# module_RevD_panelized.net
KiCad netlist of a schematic drawn in EAGLE
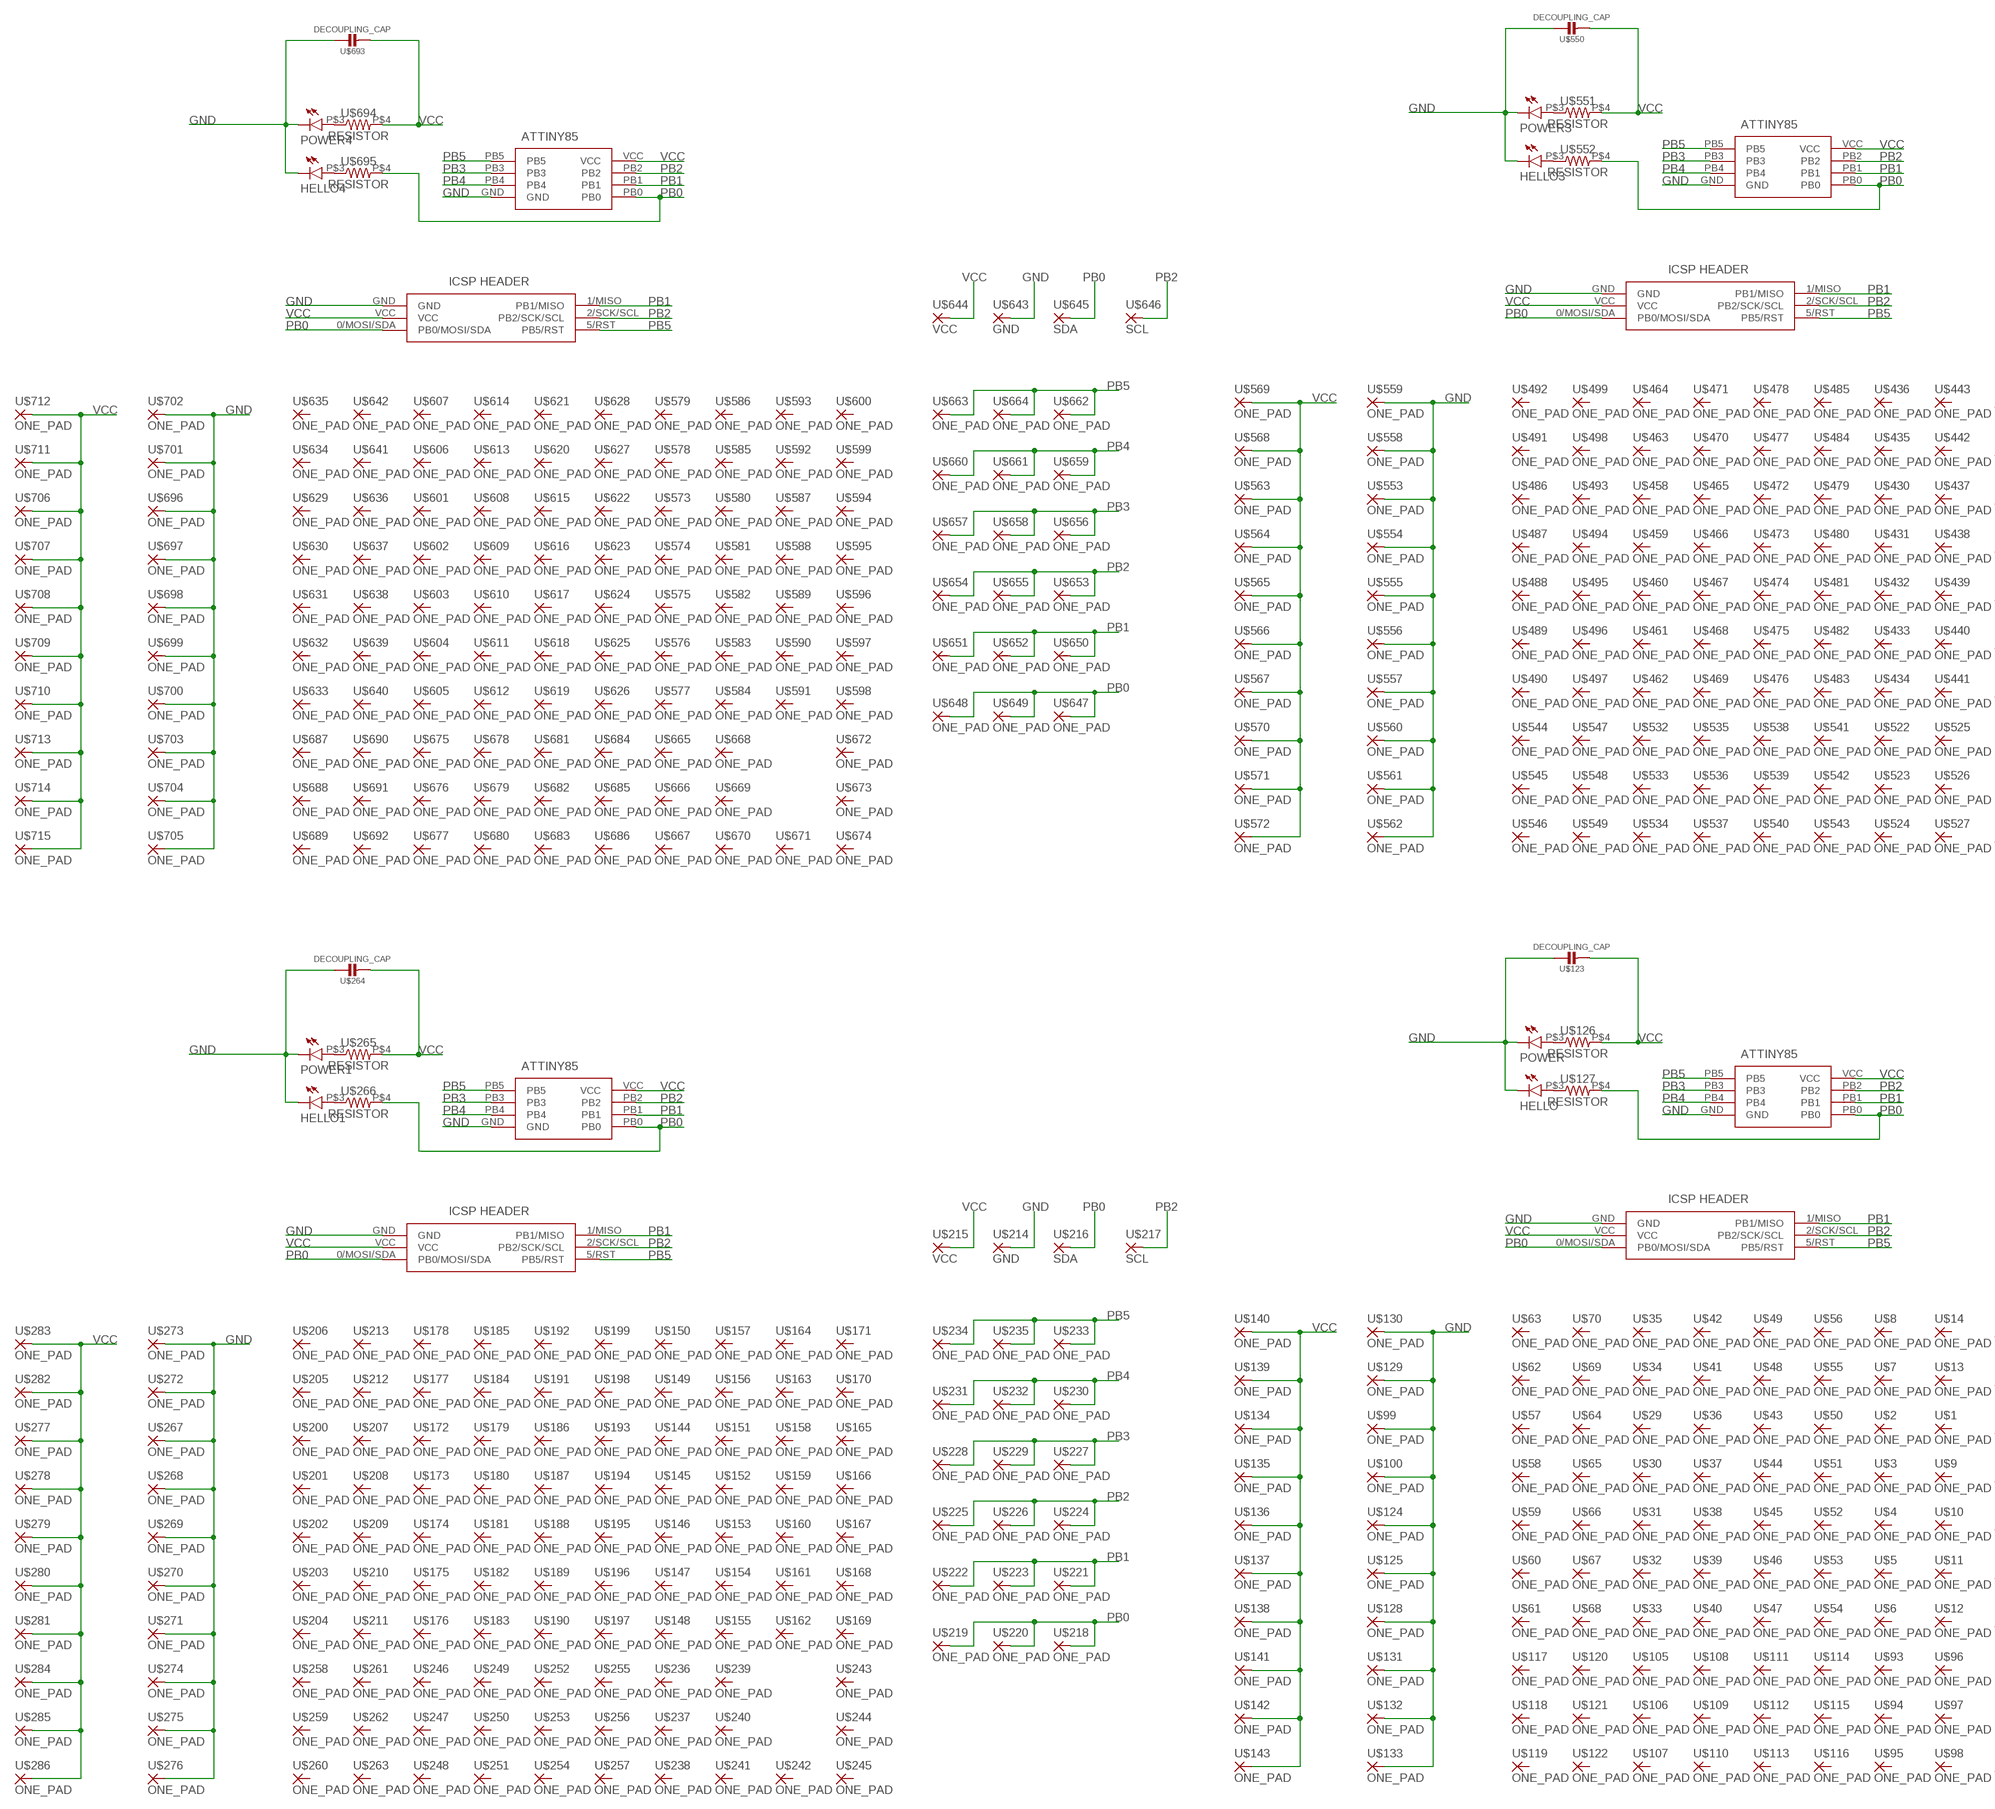
[diagram p0: schematic, sheet 1, part 1 of 2]
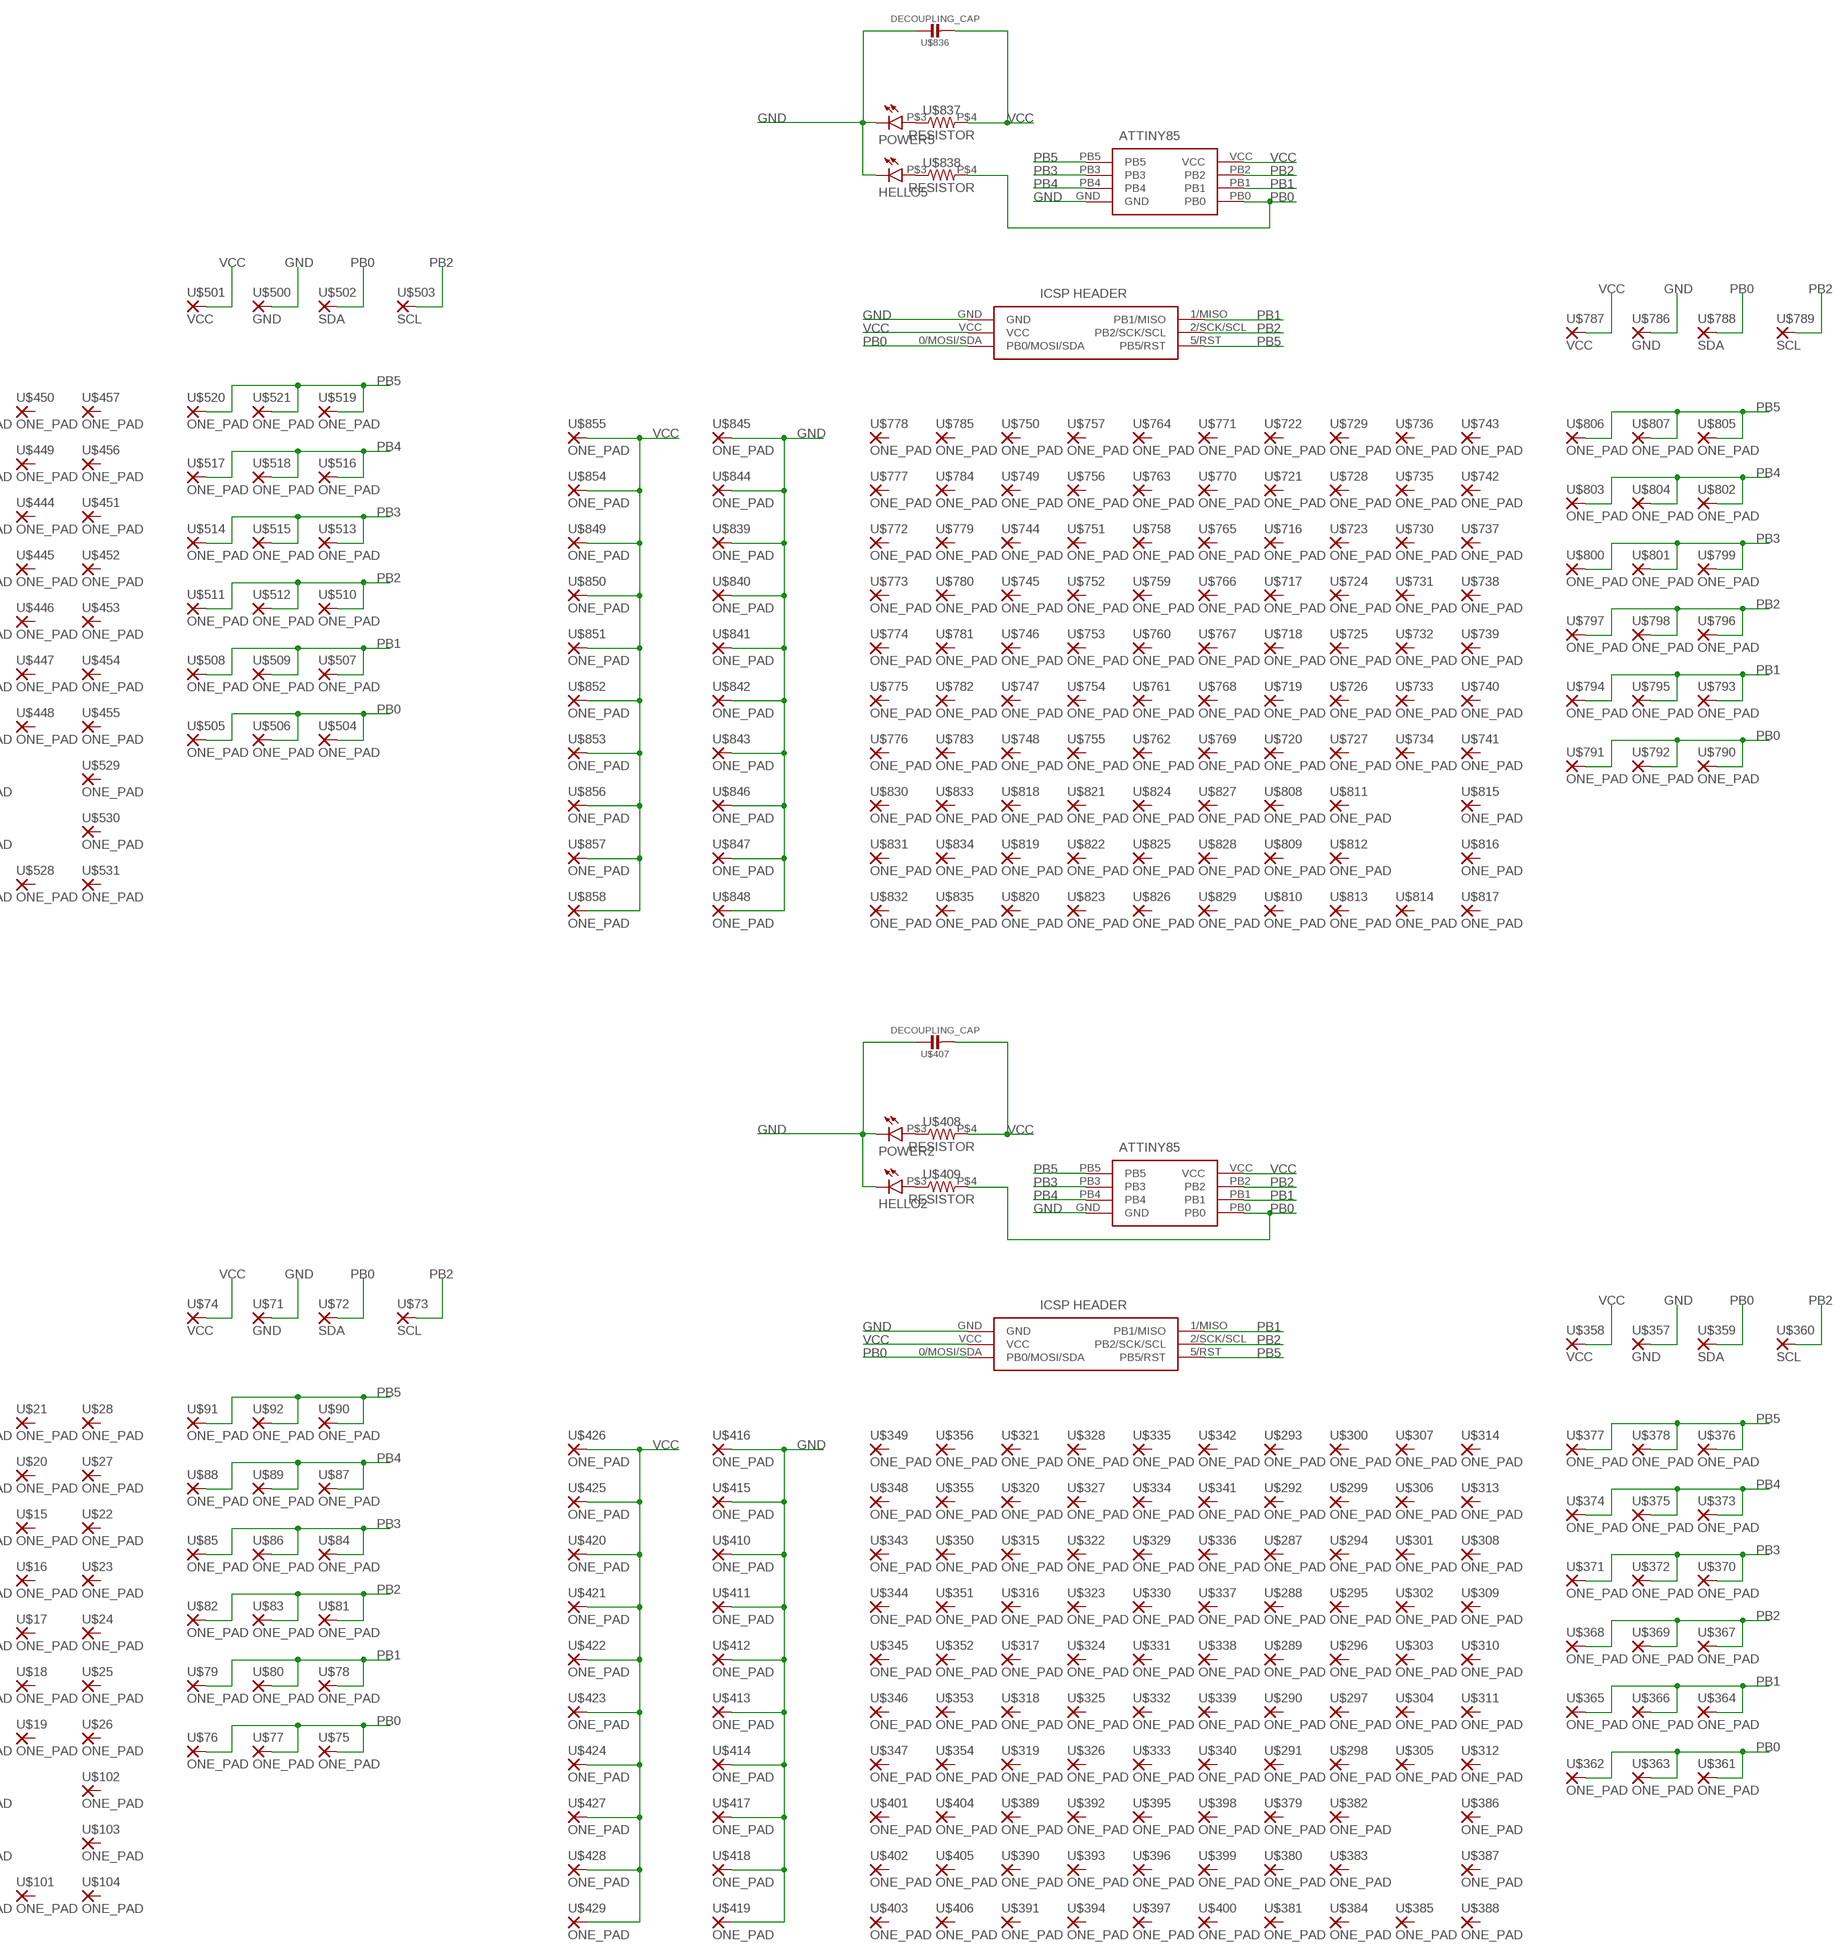
[diagram p1: schematic, sheet 1, part 2 of 2]

(export (version "E")
  (design (tool "Eeschema 10.0.6"))
  (components
    (comp (ref "HELLO")
      (value "LED3MM")
      (footprint "eagle-import:LED3MM")
      (libsource (lib "eagle-import") (part "LED3MM"))
    )
    (comp (ref "HELLO1")
      (value "LED3MM")
      (footprint "eagle-import:LED3MM")
      (libsource (lib "eagle-import") (part "LED3MM"))
    )
    (comp (ref "HELLO2")
      (value "LED3MM")
      (footprint "eagle-import:LED3MM")
      (libsource (lib "eagle-import") (part "LED3MM"))
    )
    (comp (ref "HELLO3")
      (value "LED3MM")
      (footprint "eagle-import:LED3MM")
      (libsource (lib "eagle-import") (part "LED3MM"))
    )
    (comp (ref "HELLO4")
      (value "LED3MM")
      (footprint "eagle-import:LED3MM")
      (libsource (lib "eagle-import") (part "LED3MM"))
    )
    (comp (ref "HELLO5")
      (value "LED3MM")
      (footprint "eagle-import:LED3MM")
      (libsource (lib "eagle-import") (part "LED3MM"))
    )
    (comp (ref "IC1")
      (value "ATTINY85-20SU")
      (footprint "eagle-import:SOT127P798X216-8N")
      (fields (field (name "RS_PART_NUMBER") "1331674"))
      (libsource (lib "eagle-import") (part "ATTINY85-20SU"))
    )
    (comp (ref "IC2")
      (value "ATTINY85-20SU")
      (footprint "eagle-import:SOT127P798X216-8N")
      (fields (field (name "RS_PART_NUMBER") "1331674"))
      (libsource (lib "eagle-import") (part "ATTINY85-20SU"))
    )
    (comp (ref "IC3")
      (value "ATTINY85-20SU")
      (footprint "eagle-import:SOT127P798X216-8N")
      (fields (field (name "RS_PART_NUMBER") "1331674"))
      (libsource (lib "eagle-import") (part "ATTINY85-20SU"))
    )
    (comp (ref "IC4")
      (value "ATTINY85-20SU")
      (footprint "eagle-import:SOT127P798X216-8N")
      (fields (field (name "RS_PART_NUMBER") "1331674"))
      (libsource (lib "eagle-import") (part "ATTINY85-20SU"))
    )
    (comp (ref "IC5")
      (value "ATTINY85-20SU")
      (footprint "eagle-import:SOT127P798X216-8N")
      (fields (field (name "RS_PART_NUMBER") "1331674"))
      (libsource (lib "eagle-import") (part "ATTINY85-20SU"))
    )
    (comp (ref "IC6")
      (value "ATTINY85-20SU")
      (footprint "eagle-import:SOT127P798X216-8N")
      (fields (field (name "RS_PART_NUMBER") "1331674"))
      (libsource (lib "eagle-import") (part "ATTINY85-20SU"))
    )
    (comp (ref "J1")
      (value "M20-9980346")
      (footprint "eagle-import:HDRV6W64P254_2X3_762X508X868P")
      (fields (field (name "RS_PART_NUMBER") "7457046P"))
      (libsource (lib "eagle-import") (part "M20-9980346"))
    )
    (comp (ref "J2")
      (value "M20-9980346")
      (footprint "eagle-import:HDRV6W64P254_2X3_762X508X868P")
      (fields (field (name "RS_PART_NUMBER") "7457046P"))
      (libsource (lib "eagle-import") (part "M20-9980346"))
    )
    (comp (ref "J3")
      (value "M20-9980346")
      (footprint "eagle-import:HDRV6W64P254_2X3_762X508X868P")
      (fields (field (name "RS_PART_NUMBER") "7457046P"))
      (libsource (lib "eagle-import") (part "M20-9980346"))
    )
    (comp (ref "J4")
      (value "M20-9980346")
      (footprint "eagle-import:HDRV6W64P254_2X3_762X508X868P")
      (fields (field (name "RS_PART_NUMBER") "7457046P"))
      (libsource (lib "eagle-import") (part "M20-9980346"))
    )
    (comp (ref "J5")
      (value "M20-9980346")
      (footprint "eagle-import:HDRV6W64P254_2X3_762X508X868P")
      (fields (field (name "RS_PART_NUMBER") "7457046P"))
      (libsource (lib "eagle-import") (part "M20-9980346"))
    )
    (comp (ref "J6")
      (value "M20-9980346")
      (footprint "eagle-import:HDRV6W64P254_2X3_762X508X868P")
      (fields (field (name "RS_PART_NUMBER") "7457046P"))
      (libsource (lib "eagle-import") (part "M20-9980346"))
    )
    (comp (ref "POWER")
      (value "LED3MM")
      (footprint "eagle-import:LED3MM")
      (libsource (lib "eagle-import") (part "LED3MM"))
    )
    (comp (ref "POWER1")
      (value "LED3MM")
      (footprint "eagle-import:LED3MM")
      (libsource (lib "eagle-import") (part "LED3MM"))
    )
    (comp (ref "POWER2")
      (value "LED3MM")
      (footprint "eagle-import:LED3MM")
      (libsource (lib "eagle-import") (part "LED3MM"))
    )
    (comp (ref "POWER3")
      (value "LED3MM")
      (footprint "eagle-import:LED3MM")
      (libsource (lib "eagle-import") (part "LED3MM"))
    )
    (comp (ref "POWER4")
      (value "LED3MM")
      (footprint "eagle-import:LED3MM")
      (libsource (lib "eagle-import") (part "LED3MM"))
    )
    (comp (ref "POWER5")
      (value "LED3MM")
      (footprint "eagle-import:LED3MM")
      (libsource (lib "eagle-import") (part "LED3MM"))
    )
    (comp (ref "U$1")
      (value "ONE_PAD")
      (footprint "eagle-import:1X01")
      (libsource (lib "eagle-import") (part "ONE_PAD"))
    )
    (comp (ref "U$2")
      (value "ONE_PAD")
      (footprint "eagle-import:1X01")
      (libsource (lib "eagle-import") (part "ONE_PAD"))
    )
    (comp (ref "U$3")
      (value "ONE_PAD")
      (footprint "eagle-import:1X01")
      (libsource (lib "eagle-import") (part "ONE_PAD"))
    )
    (comp (ref "U$4")
      (value "ONE_PAD")
      (footprint "eagle-import:1X01")
      (libsource (lib "eagle-import") (part "ONE_PAD"))
    )
    (comp (ref "U$5")
      (value "ONE_PAD")
      (footprint "eagle-import:1X01")
      (libsource (lib "eagle-import") (part "ONE_PAD"))
    )
    (comp (ref "U$6")
      (value "ONE_PAD")
      (footprint "eagle-import:1X01")
      (libsource (lib "eagle-import") (part "ONE_PAD"))
    )
    (comp (ref "U$7")
      (value "ONE_PAD")
      (footprint "eagle-import:1X01")
      (libsource (lib "eagle-import") (part "ONE_PAD"))
    )
    (comp (ref "U$8")
      (value "ONE_PAD")
      (footprint "eagle-import:1X01")
      (libsource (lib "eagle-import") (part "ONE_PAD"))
    )
    (comp (ref "U$9")
      (value "ONE_PAD")
      (footprint "eagle-import:1X01")
      (libsource (lib "eagle-import") (part "ONE_PAD"))
    )
    (comp (ref "U$10")
      (value "ONE_PAD")
      (footprint "eagle-import:1X01")
      (libsource (lib "eagle-import") (part "ONE_PAD"))
    )
    (comp (ref "U$11")
      (value "ONE_PAD")
      (footprint "eagle-import:1X01")
      (libsource (lib "eagle-import") (part "ONE_PAD"))
    )
    (comp (ref "U$12")
      (value "ONE_PAD")
      (footprint "eagle-import:1X01")
      (libsource (lib "eagle-import") (part "ONE_PAD"))
    )
    (comp (ref "U$13")
      (value "ONE_PAD")
      (footprint "eagle-import:1X01")
      (libsource (lib "eagle-import") (part "ONE_PAD"))
    )
    (comp (ref "U$14")
      (value "ONE_PAD")
      (footprint "eagle-import:1X01")
      (libsource (lib "eagle-import") (part "ONE_PAD"))
    )
    (comp (ref "U$15")
      (value "ONE_PAD")
      (footprint "eagle-import:1X01")
      (libsource (lib "eagle-import") (part "ONE_PAD"))
    )
    (comp (ref "U$16")
      (value "ONE_PAD")
      (footprint "eagle-import:1X01")
      (libsource (lib "eagle-import") (part "ONE_PAD"))
    )
    (comp (ref "U$17")
      (value "ONE_PAD")
      (footprint "eagle-import:1X01")
      (libsource (lib "eagle-import") (part "ONE_PAD"))
    )
    (comp (ref "U$18")
      (value "ONE_PAD")
      (footprint "eagle-import:1X01")
      (libsource (lib "eagle-import") (part "ONE_PAD"))
    )
    (comp (ref "U$19")
      (value "ONE_PAD")
      (footprint "eagle-import:1X01")
      (libsource (lib "eagle-import") (part "ONE_PAD"))
    )
    (comp (ref "U$20")
      (value "ONE_PAD")
      (footprint "eagle-import:1X01")
      (libsource (lib "eagle-import") (part "ONE_PAD"))
    )
    (comp (ref "U$21")
      (value "ONE_PAD")
      (footprint "eagle-import:1X01")
      (libsource (lib "eagle-import") (part "ONE_PAD"))
    )
    (comp (ref "U$22")
      (value "ONE_PAD")
      (footprint "eagle-import:1X01")
      (libsource (lib "eagle-import") (part "ONE_PAD"))
    )
    (comp (ref "U$23")
      (value "ONE_PAD")
      (footprint "eagle-import:1X01")
      (libsource (lib "eagle-import") (part "ONE_PAD"))
    )
    (comp (ref "U$24")
      (value "ONE_PAD")
      (footprint "eagle-import:1X01")
      (libsource (lib "eagle-import") (part "ONE_PAD"))
    )
    (comp (ref "U$25")
      (value "ONE_PAD")
      (footprint "eagle-import:1X01")
      (libsource (lib "eagle-import") (part "ONE_PAD"))
    )
    (comp (ref "U$26")
      (value "ONE_PAD")
      (footprint "eagle-import:1X01")
      (libsource (lib "eagle-import") (part "ONE_PAD"))
    )
    (comp (ref "U$27")
      (value "ONE_PAD")
      (footprint "eagle-import:1X01")
      (libsource (lib "eagle-import") (part "ONE_PAD"))
    )
    (comp (ref "U$28")
      (value "ONE_PAD")
      (footprint "eagle-import:1X01")
      (libsource (lib "eagle-import") (part "ONE_PAD"))
    )
    (comp (ref "U$29")
      (value "ONE_PAD")
      (footprint "eagle-import:1X01")
      (libsource (lib "eagle-import") (part "ONE_PAD"))
    )
    (comp (ref "U$30")
      (value "ONE_PAD")
      (footprint "eagle-import:1X01")
      (libsource (lib "eagle-import") (part "ONE_PAD"))
    )
    (comp (ref "U$31")
      (value "ONE_PAD")
      (footprint "eagle-import:1X01")
      (libsource (lib "eagle-import") (part "ONE_PAD"))
    )
    (comp (ref "U$32")
      (value "ONE_PAD")
      (footprint "eagle-import:1X01")
      (libsource (lib "eagle-import") (part "ONE_PAD"))
    )
    (comp (ref "U$33")
      (value "ONE_PAD")
      (footprint "eagle-import:1X01")
      (libsource (lib "eagle-import") (part "ONE_PAD"))
    )
    (comp (ref "U$34")
      (value "ONE_PAD")
      (footprint "eagle-import:1X01")
      (libsource (lib "eagle-import") (part "ONE_PAD"))
    )
    (comp (ref "U$35")
      (value "ONE_PAD")
      (footprint "eagle-import:1X01")
      (libsource (lib "eagle-import") (part "ONE_PAD"))
    )
    (comp (ref "U$36")
      (value "ONE_PAD")
      (footprint "eagle-import:1X01")
      (libsource (lib "eagle-import") (part "ONE_PAD"))
    )
    (comp (ref "U$37")
      (value "ONE_PAD")
      (footprint "eagle-import:1X01")
      (libsource (lib "eagle-import") (part "ONE_PAD"))
    )
    (comp (ref "U$38")
      (value "ONE_PAD")
      (footprint "eagle-import:1X01")
      (libsource (lib "eagle-import") (part "ONE_PAD"))
    )
    (comp (ref "U$39")
      (value "ONE_PAD")
      (footprint "eagle-import:1X01")
      (libsource (lib "eagle-import") (part "ONE_PAD"))
    )
    (comp (ref "U$40")
      (value "ONE_PAD")
      (footprint "eagle-import:1X01")
      (libsource (lib "eagle-import") (part "ONE_PAD"))
    )
    (comp (ref "U$41")
      (value "ONE_PAD")
      (footprint "eagle-import:1X01")
      (libsource (lib "eagle-import") (part "ONE_PAD"))
    )
    (comp (ref "U$42")
      (value "ONE_PAD")
      (footprint "eagle-import:1X01")
      (libsource (lib "eagle-import") (part "ONE_PAD"))
    )
    (comp (ref "U$43")
      (value "ONE_PAD")
      (footprint "eagle-import:1X01")
      (libsource (lib "eagle-import") (part "ONE_PAD"))
    )
    (comp (ref "U$44")
      (value "ONE_PAD")
      (footprint "eagle-import:1X01")
      (libsource (lib "eagle-import") (part "ONE_PAD"))
    )
    (comp (ref "U$45")
      (value "ONE_PAD")
      (footprint "eagle-import:1X01")
      (libsource (lib "eagle-import") (part "ONE_PAD"))
    )
    (comp (ref "U$46")
      (value "ONE_PAD")
      (footprint "eagle-import:1X01")
      (libsource (lib "eagle-import") (part "ONE_PAD"))
    )
    (comp (ref "U$47")
      (value "ONE_PAD")
      (footprint "eagle-import:1X01")
      (libsource (lib "eagle-import") (part "ONE_PAD"))
    )
    (comp (ref "U$48")
      (value "ONE_PAD")
      (footprint "eagle-import:1X01")
      (libsource (lib "eagle-import") (part "ONE_PAD"))
    )
    (comp (ref "U$49")
      (value "ONE_PAD")
      (footprint "eagle-import:1X01")
      (libsource (lib "eagle-import") (part "ONE_PAD"))
    )
    (comp (ref "U$50")
      (value "ONE_PAD")
      (footprint "eagle-import:1X01")
      (libsource (lib "eagle-import") (part "ONE_PAD"))
    )
    (comp (ref "U$51")
      (value "ONE_PAD")
      (footprint "eagle-import:1X01")
      (libsource (lib "eagle-import") (part "ONE_PAD"))
    )
    (comp (ref "U$52")
      (value "ONE_PAD")
      (footprint "eagle-import:1X01")
      (libsource (lib "eagle-import") (part "ONE_PAD"))
    )
    (comp (ref "U$53")
      (value "ONE_PAD")
      (footprint "eagle-import:1X01")
      (libsource (lib "eagle-import") (part "ONE_PAD"))
    )
    (comp (ref "U$54")
      (value "ONE_PAD")
      (footprint "eagle-import:1X01")
      (libsource (lib "eagle-import") (part "ONE_PAD"))
    )
    (comp (ref "U$55")
      (value "ONE_PAD")
      (footprint "eagle-import:1X01")
      (libsource (lib "eagle-import") (part "ONE_PAD"))
    )
    (comp (ref "U$56")
      (value "ONE_PAD")
      (footprint "eagle-import:1X01")
      (libsource (lib "eagle-import") (part "ONE_PAD"))
    )
    (comp (ref "U$57")
      (value "ONE_PAD")
      (footprint "eagle-import:1X01")
      (libsource (lib "eagle-import") (part "ONE_PAD"))
    )
    (comp (ref "U$58")
      (value "ONE_PAD")
      (footprint "eagle-import:1X01")
      (libsource (lib "eagle-import") (part "ONE_PAD"))
    )
    (comp (ref "U$59")
      (value "ONE_PAD")
      (footprint "eagle-import:1X01")
      (libsource (lib "eagle-import") (part "ONE_PAD"))
    )
    (comp (ref "U$60")
      (value "ONE_PAD")
      (footprint "eagle-import:1X01")
      (libsource (lib "eagle-import") (part "ONE_PAD"))
    )
    (comp (ref "U$61")
      (value "ONE_PAD")
      (footprint "eagle-import:1X01")
      (libsource (lib "eagle-import") (part "ONE_PAD"))
    )
    (comp (ref "U$62")
      (value "ONE_PAD")
      (footprint "eagle-import:1X01")
      (libsource (lib "eagle-import") (part "ONE_PAD"))
    )
    (comp (ref "U$63")
      (value "ONE_PAD")
      (footprint "eagle-import:1X01")
      (libsource (lib "eagle-import") (part "ONE_PAD"))
    )
    (comp (ref "U$64")
      (value "ONE_PAD")
      (footprint "eagle-import:1X01")
      (libsource (lib "eagle-import") (part "ONE_PAD"))
    )
    (comp (ref "U$65")
      (value "ONE_PAD")
      (footprint "eagle-import:1X01")
      (libsource (lib "eagle-import") (part "ONE_PAD"))
    )
    (comp (ref "U$66")
      (value "ONE_PAD")
      (footprint "eagle-import:1X01")
      (libsource (lib "eagle-import") (part "ONE_PAD"))
    )
    (comp (ref "U$67")
      (value "ONE_PAD")
      (footprint "eagle-import:1X01")
      (libsource (lib "eagle-import") (part "ONE_PAD"))
    )
    (comp (ref "U$68")
      (value "ONE_PAD")
      (footprint "eagle-import:1X01")
      (libsource (lib "eagle-import") (part "ONE_PAD"))
    )
    (comp (ref "U$69")
      (value "ONE_PAD")
      (footprint "eagle-import:1X01")
      (libsource (lib "eagle-import") (part "ONE_PAD"))
    )
    (comp (ref "U$70")
      (value "ONE_PAD")
      (footprint "eagle-import:1X01")
      (libsource (lib "eagle-import") (part "ONE_PAD"))
    )
    (comp (ref "U$71")
      (value "GND")
      (footprint "eagle-import:1X01")
      (libsource (lib "eagle-import") (part "ONE_PAD"))
    )
    (comp (ref "U$72")
      (value "SDA")
      (footprint "eagle-import:1X01")
      (libsource (lib "eagle-import") (part "ONE_PAD"))
    )
    (comp (ref "U$73")
      (value "SCL")
      (footprint "eagle-import:1X01")
      (libsource (lib "eagle-import") (part "ONE_PAD"))
    )
    (comp (ref "U$74")
      (value "VCC")
      (footprint "eagle-import:1X01")
      (libsource (lib "eagle-import") (part "ONE_PAD"))
    )
    (comp (ref "U$75")
      (value "ONE_PAD")
      (footprint "eagle-import:1X01")
      (libsource (lib "eagle-import") (part "ONE_PAD"))
    )
    (comp (ref "U$76")
      (value "ONE_PAD")
      (footprint "eagle-import:1X01")
      (libsource (lib "eagle-import") (part "ONE_PAD"))
    )
    (comp (ref "U$77")
      (value "ONE_PAD")
      (footprint "eagle-import:1X01")
      (libsource (lib "eagle-import") (part "ONE_PAD"))
    )
    (comp (ref "U$78")
      (value "ONE_PAD")
      (footprint "eagle-import:1X01")
      (libsource (lib "eagle-import") (part "ONE_PAD"))
    )
    (comp (ref "U$79")
      (value "ONE_PAD")
      (footprint "eagle-import:1X01")
      (libsource (lib "eagle-import") (part "ONE_PAD"))
    )
    (comp (ref "U$80")
      (value "ONE_PAD")
      (footprint "eagle-import:1X01")
      (libsource (lib "eagle-import") (part "ONE_PAD"))
    )
    (comp (ref "U$81")
      (value "ONE_PAD")
      (footprint "eagle-import:1X01")
      (libsource (lib "eagle-import") (part "ONE_PAD"))
    )
    (comp (ref "U$82")
      (value "ONE_PAD")
      (footprint "eagle-import:1X01")
      (libsource (lib "eagle-import") (part "ONE_PAD"))
    )
    (comp (ref "U$83")
      (value "ONE_PAD")
      (footprint "eagle-import:1X01")
      (libsource (lib "eagle-import") (part "ONE_PAD"))
    )
    (comp (ref "U$84")
      (value "ONE_PAD")
      (footprint "eagle-import:1X01")
      (libsource (lib "eagle-import") (part "ONE_PAD"))
    )
    (comp (ref "U$85")
      (value "ONE_PAD")
      (footprint "eagle-import:1X01")
      (libsource (lib "eagle-import") (part "ONE_PAD"))
    )
    (comp (ref "U$86")
      (value "ONE_PAD")
      (footprint "eagle-import:1X01")
      (libsource (lib "eagle-import") (part "ONE_PAD"))
    )
    (comp (ref "U$87")
      (value "ONE_PAD")
      (footprint "eagle-import:1X01")
      (libsource (lib "eagle-import") (part "ONE_PAD"))
    )
    (comp (ref "U$88")
      (value "ONE_PAD")
      (footprint "eagle-import:1X01")
      (libsource (lib "eagle-import") (part "ONE_PAD"))
    )
    (comp (ref "U$89")
      (value "ONE_PAD")
      (footprint "eagle-import:1X01")
      (libsource (lib "eagle-import") (part "ONE_PAD"))
    )
    (comp (ref "U$90")
      (value "ONE_PAD")
      (footprint "eagle-import:1X01")
      (libsource (lib "eagle-import") (part "ONE_PAD"))
    )
    (comp (ref "U$91")
      (value "ONE_PAD")
      (footprint "eagle-import:1X01")
      (libsource (lib "eagle-import") (part "ONE_PAD"))
    )
    (comp (ref "U$92")
      (value "ONE_PAD")
      (footprint "eagle-import:1X01")
      (libsource (lib "eagle-import") (part "ONE_PAD"))
    )
    (comp (ref "U$93")
      (value "ONE_PAD")
      (footprint "eagle-import:1X01")
      (libsource (lib "eagle-import") (part "ONE_PAD"))
    )
    (comp (ref "U$94")
      (value "ONE_PAD")
      (footprint "eagle-import:1X01")
      (libsource (lib "eagle-import") (part "ONE_PAD"))
    )
    (comp (ref "U$95")
      (value "ONE_PAD")
      (footprint "eagle-import:1X01")
      (libsource (lib "eagle-import") (part "ONE_PAD"))
    )
    (comp (ref "U$96")
      (value "ONE_PAD")
      (footprint "eagle-import:1X01")
      (libsource (lib "eagle-import") (part "ONE_PAD"))
    )
    (comp (ref "U$97")
      (value "ONE_PAD")
      (footprint "eagle-import:1X01")
      (libsource (lib "eagle-import") (part "ONE_PAD"))
    )
    (comp (ref "U$98")
      (value "ONE_PAD")
      (footprint "eagle-import:1X01")
      (libsource (lib "eagle-import") (part "ONE_PAD"))
    )
    (comp (ref "U$99")
      (value "ONE_PAD")
      (footprint "eagle-import:1X01")
      (libsource (lib "eagle-import") (part "ONE_PAD"))
    )
    (comp (ref "U$100")
      (value "ONE_PAD")
      (footprint "eagle-import:1X01")
      (libsource (lib "eagle-import") (part "ONE_PAD"))
    )
    (comp (ref "U$101")
      (value "ONE_PAD")
      (footprint "eagle-import:1X01")
      (libsource (lib "eagle-import") (part "ONE_PAD"))
    )
    (comp (ref "U$102")
      (value "ONE_PAD")
      (footprint "eagle-import:1X01")
      (libsource (lib "eagle-import") (part "ONE_PAD"))
    )
    (comp (ref "U$103")
      (value "ONE_PAD")
      (footprint "eagle-import:1X01")
      (libsource (lib "eagle-import") (part "ONE_PAD"))
    )
    (comp (ref "U$104")
      (value "ONE_PAD")
      (footprint "eagle-import:1X01")
      (libsource (lib "eagle-import") (part "ONE_PAD"))
    )
    (comp (ref "U$105")
      (value "ONE_PAD")
      (footprint "eagle-import:1X01")
      (libsource (lib "eagle-import") (part "ONE_PAD"))
    )
    (comp (ref "U$106")
      (value "ONE_PAD")
      (footprint "eagle-import:1X01")
      (libsource (lib "eagle-import") (part "ONE_PAD"))
    )
    (comp (ref "U$107")
      (value "ONE_PAD")
      (footprint "eagle-import:1X01")
      (libsource (lib "eagle-import") (part "ONE_PAD"))
    )
    (comp (ref "U$108")
      (value "ONE_PAD")
      (footprint "eagle-import:1X01")
      (libsource (lib "eagle-import") (part "ONE_PAD"))
    )
    (comp (ref "U$109")
      (value "ONE_PAD")
      (footprint "eagle-import:1X01")
      (libsource (lib "eagle-import") (part "ONE_PAD"))
    )
    (comp (ref "U$110")
      (value "ONE_PAD")
      (footprint "eagle-import:1X01")
      (libsource (lib "eagle-import") (part "ONE_PAD"))
    )
    (comp (ref "U$111")
      (value "ONE_PAD")
      (footprint "eagle-import:1X01")
      (libsource (lib "eagle-import") (part "ONE_PAD"))
    )
    (comp (ref "U$112")
      (value "ONE_PAD")
      (footprint "eagle-import:1X01")
      (libsource (lib "eagle-import") (part "ONE_PAD"))
    )
    (comp (ref "U$113")
      (value "ONE_PAD")
      (footprint "eagle-import:1X01")
      (libsource (lib "eagle-import") (part "ONE_PAD"))
    )
    (comp (ref "U$114")
      (value "ONE_PAD")
      (footprint "eagle-import:1X01")
      (libsource (lib "eagle-import") (part "ONE_PAD"))
    )
    (comp (ref "U$115")
      (value "ONE_PAD")
      (footprint "eagle-import:1X01")
      (libsource (lib "eagle-import") (part "ONE_PAD"))
    )
    (comp (ref "U$116")
      (value "ONE_PAD")
      (footprint "eagle-import:1X01")
      (libsource (lib "eagle-import") (part "ONE_PAD"))
    )
    (comp (ref "U$117")
      (value "ONE_PAD")
      (footprint "eagle-import:1X01")
      (libsource (lib "eagle-import") (part "ONE_PAD"))
    )
    (comp (ref "U$118")
      (value "ONE_PAD")
      (footprint "eagle-import:1X01")
      (libsource (lib "eagle-import") (part "ONE_PAD"))
    )
    (comp (ref "U$119")
      (value "ONE_PAD")
      (footprint "eagle-import:1X01")
      (libsource (lib "eagle-import") (part "ONE_PAD"))
    )
    (comp (ref "U$120")
      (value "ONE_PAD")
      (footprint "eagle-import:1X01")
      (libsource (lib "eagle-import") (part "ONE_PAD"))
    )
    (comp (ref "U$121")
      (value "ONE_PAD")
      (footprint "eagle-import:1X01")
      (libsource (lib "eagle-import") (part "ONE_PAD"))
    )
    (comp (ref "U$122")
      (value "ONE_PAD")
      (footprint "eagle-import:1X01")
      (libsource (lib "eagle-import") (part "ONE_PAD"))
    )
    (comp (ref "U$123")
      (value "DECOUPLING_CAP")
      (footprint "eagle-import:DECOUPLING_CAP")
      (libsource (lib "eagle-import") (part "DECOUPLING_CAP"))
    )
    (comp (ref "U$124")
      (value "ONE_PAD")
      (footprint "eagle-import:1X01")
      (libsource (lib "eagle-import") (part "ONE_PAD"))
    )
    (comp (ref "U$125")
      (value "ONE_PAD")
      (footprint "eagle-import:1X01")
      (libsource (lib "eagle-import") (part "ONE_PAD"))
    )
    (comp (ref "U$126")
      (value "RESISTOR")
      (footprint "eagle-import:AXIAL-0.3")
      (libsource (lib "eagle-import") (part "RESISTOR"))
    )
    (comp (ref "U$127")
      (value "RESISTOR")
      (footprint "eagle-import:AXIAL-0.3")
      (libsource (lib "eagle-import") (part "RESISTOR"))
    )
    (comp (ref "U$128")
      (value "ONE_PAD")
      (footprint "eagle-import:1X01")
      (libsource (lib "eagle-import") (part "ONE_PAD"))
    )
    (comp (ref "U$129")
      (value "ONE_PAD")
      (footprint "eagle-import:1X01")
      (libsource (lib "eagle-import") (part "ONE_PAD"))
    )
    (comp (ref "U$130")
      (value "ONE_PAD")
      (footprint "eagle-import:1X01")
      (libsource (lib "eagle-import") (part "ONE_PAD"))
    )
    (comp (ref "U$131")
      (value "ONE_PAD")
      (footprint "eagle-import:1X01")
      (libsource (lib "eagle-import") (part "ONE_PAD"))
    )
    (comp (ref "U$132")
      (value "ONE_PAD")
      (footprint "eagle-import:1X01")
      (libsource (lib "eagle-import") (part "ONE_PAD"))
    )
    (comp (ref "U$133")
      (value "ONE_PAD")
      (footprint "eagle-import:1X01")
      (libsource (lib "eagle-import") (part "ONE_PAD"))
    )
    (comp (ref "U$134")
      (value "ONE_PAD")
      (footprint "eagle-import:1X01")
      (libsource (lib "eagle-import") (part "ONE_PAD"))
    )
    (comp (ref "U$135")
      (value "ONE_PAD")
      (footprint "eagle-import:1X01")
      (libsource (lib "eagle-import") (part "ONE_PAD"))
    )
    (comp (ref "U$136")
      (value "ONE_PAD")
      (footprint "eagle-import:1X01")
      (libsource (lib "eagle-import") (part "ONE_PAD"))
    )
    (comp (ref "U$137")
      (value "ONE_PAD")
      (footprint "eagle-import:1X01")
      (libsource (lib "eagle-import") (part "ONE_PAD"))
    )
    (comp (ref "U$138")
      (value "ONE_PAD")
      (footprint "eagle-import:1X01")
      (libsource (lib "eagle-import") (part "ONE_PAD"))
    )
    (comp (ref "U$139")
      (value "ONE_PAD")
      (footprint "eagle-import:1X01")
      (libsource (lib "eagle-import") (part "ONE_PAD"))
    )
    (comp (ref "U$140")
      (value "ONE_PAD")
      (footprint "eagle-import:1X01")
      (libsource (lib "eagle-import") (part "ONE_PAD"))
    )
    (comp (ref "U$141")
      (value "ONE_PAD")
      (footprint "eagle-import:1X01")
      (libsource (lib "eagle-import") (part "ONE_PAD"))
    )
    (comp (ref "U$142")
      (value "ONE_PAD")
      (footprint "eagle-import:1X01")
      (libsource (lib "eagle-import") (part "ONE_PAD"))
    )
    (comp (ref "U$143")
      (value "ONE_PAD")
      (footprint "eagle-import:1X01")
      (libsource (lib "eagle-import") (part "ONE_PAD"))
    )
    (comp (ref "U$144")
      (value "ONE_PAD")
      (footprint "eagle-import:1X01")
      (libsource (lib "eagle-import") (part "ONE_PAD"))
    )
    (comp (ref "U$145")
      (value "ONE_PAD")
      (footprint "eagle-import:1X01")
      (libsource (lib "eagle-import") (part "ONE_PAD"))
    )
    (comp (ref "U$146")
      (value "ONE_PAD")
      (footprint "eagle-import:1X01")
      (libsource (lib "eagle-import") (part "ONE_PAD"))
    )
    (comp (ref "U$147")
      (value "ONE_PAD")
      (footprint "eagle-import:1X01")
      (libsource (lib "eagle-import") (part "ONE_PAD"))
    )
    (comp (ref "U$148")
      (value "ONE_PAD")
      (footprint "eagle-import:1X01")
      (libsource (lib "eagle-import") (part "ONE_PAD"))
    )
    (comp (ref "U$149")
      (value "ONE_PAD")
      (footprint "eagle-import:1X01")
      (libsource (lib "eagle-import") (part "ONE_PAD"))
    )
    (comp (ref "U$150")
      (value "ONE_PAD")
      (footprint "eagle-import:1X01")
      (libsource (lib "eagle-import") (part "ONE_PAD"))
    )
    (comp (ref "U$151")
      (value "ONE_PAD")
      (footprint "eagle-import:1X01")
      (libsource (lib "eagle-import") (part "ONE_PAD"))
    )
    (comp (ref "U$152")
      (value "ONE_PAD")
      (footprint "eagle-import:1X01")
      (libsource (lib "eagle-import") (part "ONE_PAD"))
    )
    (comp (ref "U$153")
      (value "ONE_PAD")
      (footprint "eagle-import:1X01")
      (libsource (lib "eagle-import") (part "ONE_PAD"))
    )
    (comp (ref "U$154")
      (value "ONE_PAD")
      (footprint "eagle-import:1X01")
      (libsource (lib "eagle-import") (part "ONE_PAD"))
    )
    (comp (ref "U$155")
      (value "ONE_PAD")
      (footprint "eagle-import:1X01")
      (libsource (lib "eagle-import") (part "ONE_PAD"))
    )
    (comp (ref "U$156")
      (value "ONE_PAD")
      (footprint "eagle-import:1X01")
      (libsource (lib "eagle-import") (part "ONE_PAD"))
    )
    (comp (ref "U$157")
      (value "ONE_PAD")
      (footprint "eagle-import:1X01")
      (libsource (lib "eagle-import") (part "ONE_PAD"))
    )
    (comp (ref "U$158")
      (value "ONE_PAD")
      (footprint "eagle-import:1X01")
      (libsource (lib "eagle-import") (part "ONE_PAD"))
    )
    (comp (ref "U$159")
      (value "ONE_PAD")
      (footprint "eagle-import:1X01")
      (libsource (lib "eagle-import") (part "ONE_PAD"))
    )
    (comp (ref "U$160")
      (value "ONE_PAD")
      (footprint "eagle-import:1X01")
      (libsource (lib "eagle-import") (part "ONE_PAD"))
    )
    (comp (ref "U$161")
      (value "ONE_PAD")
      (footprint "eagle-import:1X01")
      (libsource (lib "eagle-import") (part "ONE_PAD"))
    )
    (comp (ref "U$162")
      (value "ONE_PAD")
      (footprint "eagle-import:1X01")
      (libsource (lib "eagle-import") (part "ONE_PAD"))
    )
    (comp (ref "U$163")
      (value "ONE_PAD")
      (footprint "eagle-import:1X01")
      (libsource (lib "eagle-import") (part "ONE_PAD"))
    )
    (comp (ref "U$164")
      (value "ONE_PAD")
      (footprint "eagle-import:1X01")
      (libsource (lib "eagle-import") (part "ONE_PAD"))
    )
    (comp (ref "U$165")
      (value "ONE_PAD")
      (footprint "eagle-import:1X01")
      (libsource (lib "eagle-import") (part "ONE_PAD"))
    )
    (comp (ref "U$166")
      (value "ONE_PAD")
      (footprint "eagle-import:1X01")
      (libsource (lib "eagle-import") (part "ONE_PAD"))
    )
    (comp (ref "U$167")
      (value "ONE_PAD")
      (footprint "eagle-import:1X01")
      (libsource (lib "eagle-import") (part "ONE_PAD"))
    )
    (comp (ref "U$168")
      (value "ONE_PAD")
      (footprint "eagle-import:1X01")
      (libsource (lib "eagle-import") (part "ONE_PAD"))
    )
    (comp (ref "U$169")
      (value "ONE_PAD")
      (footprint "eagle-import:1X01")
      (libsource (lib "eagle-import") (part "ONE_PAD"))
    )
    (comp (ref "U$170")
      (value "ONE_PAD")
      (footprint "eagle-import:1X01")
      (libsource (lib "eagle-import") (part "ONE_PAD"))
    )
    (comp (ref "U$171")
      (value "ONE_PAD")
      (footprint "eagle-import:1X01")
      (libsource (lib "eagle-import") (part "ONE_PAD"))
    )
    (comp (ref "U$172")
      (value "ONE_PAD")
      (footprint "eagle-import:1X01")
      (libsource (lib "eagle-import") (part "ONE_PAD"))
    )
    (comp (ref "U$173")
      (value "ONE_PAD")
      (footprint "eagle-import:1X01")
      (libsource (lib "eagle-import") (part "ONE_PAD"))
    )
    (comp (ref "U$174")
      (value "ONE_PAD")
      (footprint "eagle-import:1X01")
      (libsource (lib "eagle-import") (part "ONE_PAD"))
    )
    (comp (ref "U$175")
      (value "ONE_PAD")
      (footprint "eagle-import:1X01")
      (libsource (lib "eagle-import") (part "ONE_PAD"))
    )
    (comp (ref "U$176")
      (value "ONE_PAD")
      (footprint "eagle-import:1X01")
      (libsource (lib "eagle-import") (part "ONE_PAD"))
    )
    (comp (ref "U$177")
      (value "ONE_PAD")
      (footprint "eagle-import:1X01")
      (libsource (lib "eagle-import") (part "ONE_PAD"))
    )
    (comp (ref "U$178")
      (value "ONE_PAD")
      (footprint "eagle-import:1X01")
      (libsource (lib "eagle-import") (part "ONE_PAD"))
    )
    (comp (ref "U$179")
      (value "ONE_PAD")
      (footprint "eagle-import:1X01")
      (libsource (lib "eagle-import") (part "ONE_PAD"))
    )
    (comp (ref "U$180")
      (value "ONE_PAD")
      (footprint "eagle-import:1X01")
      (libsource (lib "eagle-import") (part "ONE_PAD"))
    )
    (comp (ref "U$181")
      (value "ONE_PAD")
      (footprint "eagle-import:1X01")
      (libsource (lib "eagle-import") (part "ONE_PAD"))
    )
    (comp (ref "U$182")
      (value "ONE_PAD")
      (footprint "eagle-import:1X01")
      (libsource (lib "eagle-import") (part "ONE_PAD"))
    )
    (comp (ref "U$183")
      (value "ONE_PAD")
      (footprint "eagle-import:1X01")
      (libsource (lib "eagle-import") (part "ONE_PAD"))
    )
    (comp (ref "U$184")
      (value "ONE_PAD")
      (footprint "eagle-import:1X01")
      (libsource (lib "eagle-import") (part "ONE_PAD"))
    )
    (comp (ref "U$185")
      (value "ONE_PAD")
      (footprint "eagle-import:1X01")
      (libsource (lib "eagle-import") (part "ONE_PAD"))
    )
    (comp (ref "U$186")
      (value "ONE_PAD")
      (footprint "eagle-import:1X01")
      (libsource (lib "eagle-import") (part "ONE_PAD"))
    )
    (comp (ref "U$187")
      (value "ONE_PAD")
      (footprint "eagle-import:1X01")
      (libsource (lib "eagle-import") (part "ONE_PAD"))
    )
    (comp (ref "U$188")
      (value "ONE_PAD")
      (footprint "eagle-import:1X01")
      (libsource (lib "eagle-import") (part "ONE_PAD"))
    )
    (comp (ref "U$189")
      (value "ONE_PAD")
      (footprint "eagle-import:1X01")
      (libsource (lib "eagle-import") (part "ONE_PAD"))
    )
    (comp (ref "U$190")
      (value "ONE_PAD")
      (footprint "eagle-import:1X01")
      (libsource (lib "eagle-import") (part "ONE_PAD"))
    )
    (comp (ref "U$191")
      (value "ONE_PAD")
      (footprint "eagle-import:1X01")
      (libsource (lib "eagle-import") (part "ONE_PAD"))
    )
    (comp (ref "U$192")
      (value "ONE_PAD")
      (footprint "eagle-import:1X01")
      (libsource (lib "eagle-import") (part "ONE_PAD"))
    )
    (comp (ref "U$193")
      (value "ONE_PAD")
      (footprint "eagle-import:1X01")
      (libsource (lib "eagle-import") (part "ONE_PAD"))
    )
    (comp (ref "U$194")
      (value "ONE_PAD")
      (footprint "eagle-import:1X01")
      (libsource (lib "eagle-import") (part "ONE_PAD"))
    )
    (comp (ref "U$195")
      (value "ONE_PAD")
      (footprint "eagle-import:1X01")
      (libsource (lib "eagle-import") (part "ONE_PAD"))
    )
    (comp (ref "U$196")
      (value "ONE_PAD")
      (footprint "eagle-import:1X01")
      (libsource (lib "eagle-import") (part "ONE_PAD"))
    )
    (comp (ref "U$197")
      (value "ONE_PAD")
      (footprint "eagle-import:1X01")
      (libsource (lib "eagle-import") (part "ONE_PAD"))
    )
    (comp (ref "U$198")
      (value "ONE_PAD")
      (footprint "eagle-import:1X01")
      (libsource (lib "eagle-import") (part "ONE_PAD"))
    )
    (comp (ref "U$199")
      (value "ONE_PAD")
      (footprint "eagle-import:1X01")
      (libsource (lib "eagle-import") (part "ONE_PAD"))
    )
    (comp (ref "U$200")
      (value "ONE_PAD")
      (footprint "eagle-import:1X01")
      (libsource (lib "eagle-import") (part "ONE_PAD"))
    )
    (comp (ref "U$201")
      (value "ONE_PAD")
      (footprint "eagle-import:1X01")
      (libsource (lib "eagle-import") (part "ONE_PAD"))
    )
    (comp (ref "U$202")
      (value "ONE_PAD")
      (footprint "eagle-import:1X01")
      (libsource (lib "eagle-import") (part "ONE_PAD"))
    )
    (comp (ref "U$203")
      (value "ONE_PAD")
      (footprint "eagle-import:1X01")
      (libsource (lib "eagle-import") (part "ONE_PAD"))
    )
    (comp (ref "U$204")
      (value "ONE_PAD")
      (footprint "eagle-import:1X01")
      (libsource (lib "eagle-import") (part "ONE_PAD"))
    )
    (comp (ref "U$205")
      (value "ONE_PAD")
      (footprint "eagle-import:1X01")
      (libsource (lib "eagle-import") (part "ONE_PAD"))
    )
    (comp (ref "U$206")
      (value "ONE_PAD")
      (footprint "eagle-import:1X01")
      (libsource (lib "eagle-import") (part "ONE_PAD"))
    )
    (comp (ref "U$207")
      (value "ONE_PAD")
      (footprint "eagle-import:1X01")
      (libsource (lib "eagle-import") (part "ONE_PAD"))
    )
    (comp (ref "U$208")
      (value "ONE_PAD")
      (footprint "eagle-import:1X01")
      (libsource (lib "eagle-import") (part "ONE_PAD"))
    )
    (comp (ref "U$209")
      (value "ONE_PAD")
      (footprint "eagle-import:1X01")
      (libsource (lib "eagle-import") (part "ONE_PAD"))
    )
    (comp (ref "U$210")
      (value "ONE_PAD")
      (footprint "eagle-import:1X01")
      (libsource (lib "eagle-import") (part "ONE_PAD"))
    )
    (comp (ref "U$211")
      (value "ONE_PAD")
      (footprint "eagle-import:1X01")
      (libsource (lib "eagle-import") (part "ONE_PAD"))
    )
    (comp (ref "U$212")
      (value "ONE_PAD")
      (footprint "eagle-import:1X01")
      (libsource (lib "eagle-import") (part "ONE_PAD"))
    )
    (comp (ref "U$213")
      (value "ONE_PAD")
      (footprint "eagle-import:1X01")
      (libsource (lib "eagle-import") (part "ONE_PAD"))
    )
    (comp (ref "U$214")
      (value "GND")
      (footprint "eagle-import:1X01")
      (libsource (lib "eagle-import") (part "ONE_PAD"))
    )
    (comp (ref "U$215")
      (value "VCC")
      (footprint "eagle-import:1X01")
      (libsource (lib "eagle-import") (part "ONE_PAD"))
    )
    (comp (ref "U$216")
      (value "SDA")
      (footprint "eagle-import:1X01")
      (libsource (lib "eagle-import") (part "ONE_PAD"))
    )
    (comp (ref "U$217")
      (value "SCL")
      (footprint "eagle-import:1X01")
      (libsource (lib "eagle-import") (part "ONE_PAD"))
    )
    (comp (ref "U$218")
      (value "ONE_PAD")
      (footprint "eagle-import:1X01")
      (libsource (lib "eagle-import") (part "ONE_PAD"))
    )
    (comp (ref "U$219")
      (value "ONE_PAD")
      (footprint "eagle-import:1X01")
      (libsource (lib "eagle-import") (part "ONE_PAD"))
    )
    (comp (ref "U$220")
      (value "ONE_PAD")
      (footprint "eagle-import:1X01")
      (libsource (lib "eagle-import") (part "ONE_PAD"))
    )
    (comp (ref "U$221")
      (value "ONE_PAD")
      (footprint "eagle-import:1X01")
      (libsource (lib "eagle-import") (part "ONE_PAD"))
    )
    (comp (ref "U$222")
      (value "ONE_PAD")
      (footprint "eagle-import:1X01")
      (libsource (lib "eagle-import") (part "ONE_PAD"))
    )
    (comp (ref "U$223")
      (value "ONE_PAD")
      (footprint "eagle-import:1X01")
      (libsource (lib "eagle-import") (part "ONE_PAD"))
    )
    (comp (ref "U$224")
      (value "ONE_PAD")
      (footprint "eagle-import:1X01")
      (libsource (lib "eagle-import") (part "ONE_PAD"))
    )
    (comp (ref "U$225")
      (value "ONE_PAD")
      (footprint "eagle-import:1X01")
      (libsource (lib "eagle-import") (part "ONE_PAD"))
    )
    (comp (ref "U$226")
      (value "ONE_PAD")
      (footprint "eagle-import:1X01")
      (libsource (lib "eagle-import") (part "ONE_PAD"))
    )
    (comp (ref "U$227")
      (value "ONE_PAD")
      (footprint "eagle-import:1X01")
      (libsource (lib "eagle-import") (part "ONE_PAD"))
    )
    (comp (ref "U$228")
      (value "ONE_PAD")
      (footprint "eagle-import:1X01")
      (libsource (lib "eagle-import") (part "ONE_PAD"))
    )
    (comp (ref "U$229")
      (value "ONE_PAD")
      (footprint "eagle-import:1X01")
      (libsource (lib "eagle-import") (part "ONE_PAD"))
    )
    (comp (ref "U$230")
      (value "ONE_PAD")
      (footprint "eagle-import:1X01")
      (libsource (lib "eagle-import") (part "ONE_PAD"))
    )
    (comp (ref "U$231")
      (value "ONE_PAD")
      (footprint "eagle-import:1X01")
      (libsource (lib "eagle-import") (part "ONE_PAD"))
    )
    (comp (ref "U$232")
      (value "ONE_PAD")
      (footprint "eagle-import:1X01")
      (libsource (lib "eagle-import") (part "ONE_PAD"))
    )
    (comp (ref "U$233")
      (value "ONE_PAD")
      (footprint "eagle-import:1X01")
      (libsource (lib "eagle-import") (part "ONE_PAD"))
    )
    (comp (ref "U$234")
      (value "ONE_PAD")
      (footprint "eagle-import:1X01")
      (libsource (lib "eagle-import") (part "ONE_PAD"))
    )
    (comp (ref "U$235")
      (value "ONE_PAD")
      (footprint "eagle-import:1X01")
      (libsource (lib "eagle-import") (part "ONE_PAD"))
    )
    (comp (ref "U$236")
      (value "ONE_PAD")
      (footprint "eagle-import:1X01")
      (libsource (lib "eagle-import") (part "ONE_PAD"))
    )
    (comp (ref "U$237")
      (value "ONE_PAD")
      (footprint "eagle-import:1X01")
      (libsource (lib "eagle-import") (part "ONE_PAD"))
    )
    (comp (ref "U$238")
      (value "ONE_PAD")
      (footprint "eagle-import:1X01")
      (libsource (lib "eagle-import") (part "ONE_PAD"))
    )
    (comp (ref "U$239")
      (value "ONE_PAD")
      (footprint "eagle-import:1X01")
      (libsource (lib "eagle-import") (part "ONE_PAD"))
    )
    (comp (ref "U$240")
      (value "ONE_PAD")
      (footprint "eagle-import:1X01")
      (libsource (lib "eagle-import") (part "ONE_PAD"))
    )
    (comp (ref "U$241")
      (value "ONE_PAD")
      (footprint "eagle-import:1X01")
      (libsource (lib "eagle-import") (part "ONE_PAD"))
    )
    (comp (ref "U$242")
      (value "ONE_PAD")
      (footprint "eagle-import:1X01")
      (libsource (lib "eagle-import") (part "ONE_PAD"))
    )
    (comp (ref "U$243")
      (value "ONE_PAD")
      (footprint "eagle-import:1X01")
      (libsource (lib "eagle-import") (part "ONE_PAD"))
    )
    (comp (ref "U$244")
      (value "ONE_PAD")
      (footprint "eagle-import:1X01")
      (libsource (lib "eagle-import") (part "ONE_PAD"))
    )
    (comp (ref "U$245")
      (value "ONE_PAD")
      (footprint "eagle-import:1X01")
      (libsource (lib "eagle-import") (part "ONE_PAD"))
    )
    (comp (ref "U$246")
      (value "ONE_PAD")
      (footprint "eagle-import:1X01")
      (libsource (lib "eagle-import") (part "ONE_PAD"))
    )
    (comp (ref "U$247")
      (value "ONE_PAD")
      (footprint "eagle-import:1X01")
      (libsource (lib "eagle-import") (part "ONE_PAD"))
    )
    (comp (ref "U$248")
      (value "ONE_PAD")
      (footprint "eagle-import:1X01")
      (libsource (lib "eagle-import") (part "ONE_PAD"))
    )
    (comp (ref "U$249")
      (value "ONE_PAD")
      (footprint "eagle-import:1X01")
      (libsource (lib "eagle-import") (part "ONE_PAD"))
    )
    (comp (ref "U$250")
      (value "ONE_PAD")
      (footprint "eagle-import:1X01")
      (libsource (lib "eagle-import") (part "ONE_PAD"))
    )
    (comp (ref "U$251")
      (value "ONE_PAD")
      (footprint "eagle-import:1X01")
      (libsource (lib "eagle-import") (part "ONE_PAD"))
    )
    (comp (ref "U$252")
      (value "ONE_PAD")
      (footprint "eagle-import:1X01")
      (libsource (lib "eagle-import") (part "ONE_PAD"))
    )
    (comp (ref "U$253")
      (value "ONE_PAD")
      (footprint "eagle-import:1X01")
      (libsource (lib "eagle-import") (part "ONE_PAD"))
    )
    (comp (ref "U$254")
      (value "ONE_PAD")
      (footprint "eagle-import:1X01")
      (libsource (lib "eagle-import") (part "ONE_PAD"))
    )
    (comp (ref "U$255")
      (value "ONE_PAD")
      (footprint "eagle-import:1X01")
      (libsource (lib "eagle-import") (part "ONE_PAD"))
    )
    (comp (ref "U$256")
      (value "ONE_PAD")
      (footprint "eagle-import:1X01")
      (libsource (lib "eagle-import") (part "ONE_PAD"))
    )
    (comp (ref "U$257")
      (value "ONE_PAD")
      (footprint "eagle-import:1X01")
      (libsource (lib "eagle-import") (part "ONE_PAD"))
    )
    (comp (ref "U$258")
      (value "ONE_PAD")
      (footprint "eagle-import:1X01")
      (libsource (lib "eagle-import") (part "ONE_PAD"))
    )
    (comp (ref "U$259")
      (value "ONE_PAD")
      (footprint "eagle-import:1X01")
      (libsource (lib "eagle-import") (part "ONE_PAD"))
    )
    (comp (ref "U$260")
      (value "ONE_PAD")
      (footprint "eagle-import:1X01")
      (libsource (lib "eagle-import") (part "ONE_PAD"))
    )
    (comp (ref "U$261")
      (value "ONE_PAD")
      (footprint "eagle-import:1X01")
      (libsource (lib "eagle-import") (part "ONE_PAD"))
    )
    (comp (ref "U$262")
      (value "ONE_PAD")
      (footprint "eagle-import:1X01")
      (libsource (lib "eagle-import") (part "ONE_PAD"))
    )
    (comp (ref "U$263")
      (value "ONE_PAD")
      (footprint "eagle-import:1X01")
      (libsource (lib "eagle-import") (part "ONE_PAD"))
    )
    (comp (ref "U$264")
      (value "DECOUPLING_CAP")
      (footprint "eagle-import:DECOUPLING_CAP")
      (libsource (lib "eagle-import") (part "DECOUPLING_CAP"))
    )
    (comp (ref "U$265")
      (value "RESISTOR")
      (footprint "eagle-import:AXIAL-0.3")
      (libsource (lib "eagle-import") (part "RESISTOR"))
    )
    (comp (ref "U$266")
      (value "RESISTOR")
      (footprint "eagle-import:AXIAL-0.3")
      (libsource (lib "eagle-import") (part "RESISTOR"))
    )
    (comp (ref "U$267")
      (value "ONE_PAD")
      (footprint "eagle-import:1X01")
      (libsource (lib "eagle-import") (part "ONE_PAD"))
    )
    (comp (ref "U$268")
      (value "ONE_PAD")
      (footprint "eagle-import:1X01")
      (libsource (lib "eagle-import") (part "ONE_PAD"))
    )
    (comp (ref "U$269")
      (value "ONE_PAD")
      (footprint "eagle-import:1X01")
      (libsource (lib "eagle-import") (part "ONE_PAD"))
    )
    (comp (ref "U$270")
      (value "ONE_PAD")
      (footprint "eagle-import:1X01")
      (libsource (lib "eagle-import") (part "ONE_PAD"))
    )
    (comp (ref "U$271")
      (value "ONE_PAD")
      (footprint "eagle-import:1X01")
      (libsource (lib "eagle-import") (part "ONE_PAD"))
    )
    (comp (ref "U$272")
      (value "ONE_PAD")
      (footprint "eagle-import:1X01")
      (libsource (lib "eagle-import") (part "ONE_PAD"))
    )
    (comp (ref "U$273")
      (value "ONE_PAD")
      (footprint "eagle-import:1X01")
      (libsource (lib "eagle-import") (part "ONE_PAD"))
    )
    (comp (ref "U$274")
      (value "ONE_PAD")
      (footprint "eagle-import:1X01")
      (libsource (lib "eagle-import") (part "ONE_PAD"))
    )
    (comp (ref "U$275")
      (value "ONE_PAD")
      (footprint "eagle-import:1X01")
      (libsource (lib "eagle-import") (part "ONE_PAD"))
    )
    (comp (ref "U$276")
      (value "ONE_PAD")
      (footprint "eagle-import:1X01")
      (libsource (lib "eagle-import") (part "ONE_PAD"))
    )
    (comp (ref "U$277")
      (value "ONE_PAD")
      (footprint "eagle-import:1X01")
      (libsource (lib "eagle-import") (part "ONE_PAD"))
    )
    (comp (ref "U$278")
      (value "ONE_PAD")
      (footprint "eagle-import:1X01")
      (libsource (lib "eagle-import") (part "ONE_PAD"))
    )
    (comp (ref "U$279")
      (value "ONE_PAD")
      (footprint "eagle-import:1X01")
      (libsource (lib "eagle-import") (part "ONE_PAD"))
    )
    (comp (ref "U$280")
      (value "ONE_PAD")
      (footprint "eagle-import:1X01")
      (libsource (lib "eagle-import") (part "ONE_PAD"))
    )
    (comp (ref "U$281")
      (value "ONE_PAD")
      (footprint "eagle-import:1X01")
      (libsource (lib "eagle-import") (part "ONE_PAD"))
    )
    (comp (ref "U$282")
      (value "ONE_PAD")
      (footprint "eagle-import:1X01")
      (libsource (lib "eagle-import") (part "ONE_PAD"))
    )
    (comp (ref "U$283")
      (value "ONE_PAD")
      (footprint "eagle-import:1X01")
      (libsource (lib "eagle-import") (part "ONE_PAD"))
    )
    (comp (ref "U$284")
      (value "ONE_PAD")
      (footprint "eagle-import:1X01")
      (libsource (lib "eagle-import") (part "ONE_PAD"))
    )
    (comp (ref "U$285")
      (value "ONE_PAD")
      (footprint "eagle-import:1X01")
      (libsource (lib "eagle-import") (part "ONE_PAD"))
    )
    (comp (ref "U$286")
      (value "ONE_PAD")
      (footprint "eagle-import:1X01")
      (libsource (lib "eagle-import") (part "ONE_PAD"))
    )
    (comp (ref "U$287")
      (value "ONE_PAD")
      (footprint "eagle-import:1X01")
      (libsource (lib "eagle-import") (part "ONE_PAD"))
    )
    (comp (ref "U$288")
      (value "ONE_PAD")
      (footprint "eagle-import:1X01")
      (libsource (lib "eagle-import") (part "ONE_PAD"))
    )
    (comp (ref "U$289")
      (value "ONE_PAD")
      (footprint "eagle-import:1X01")
      (libsource (lib "eagle-import") (part "ONE_PAD"))
    )
    (comp (ref "U$290")
      (value "ONE_PAD")
      (footprint "eagle-import:1X01")
      (libsource (lib "eagle-import") (part "ONE_PAD"))
    )
    (comp (ref "U$291")
      (value "ONE_PAD")
      (footprint "eagle-import:1X01")
      (libsource (lib "eagle-import") (part "ONE_PAD"))
    )
    (comp (ref "U$292")
      (value "ONE_PAD")
      (footprint "eagle-import:1X01")
      (libsource (lib "eagle-import") (part "ONE_PAD"))
    )
    (comp (ref "U$293")
      (value "ONE_PAD")
      (footprint "eagle-import:1X01")
      (libsource (lib "eagle-import") (part "ONE_PAD"))
    )
    (comp (ref "U$294")
      (value "ONE_PAD")
      (footprint "eagle-import:1X01")
      (libsource (lib "eagle-import") (part "ONE_PAD"))
    )
    (comp (ref "U$295")
      (value "ONE_PAD")
      (footprint "eagle-import:1X01")
      (libsource (lib "eagle-import") (part "ONE_PAD"))
    )
    (comp (ref "U$296")
      (value "ONE_PAD")
      (footprint "eagle-import:1X01")
      (libsource (lib "eagle-import") (part "ONE_PAD"))
    )
    (comp (ref "U$297")
      (value "ONE_PAD")
      (footprint "eagle-import:1X01")
      (libsource (lib "eagle-import") (part "ONE_PAD"))
    )
    (comp (ref "U$298")
      (value "ONE_PAD")
      (footprint "eagle-import:1X01")
      (libsource (lib "eagle-import") (part "ONE_PAD"))
    )
    (comp (ref "U$299")
      (value "ONE_PAD")
      (footprint "eagle-import:1X01")
      (libsource (lib "eagle-import") (part "ONE_PAD"))
    )
    (comp (ref "U$300")
      (value "ONE_PAD")
      (footprint "eagle-import:1X01")
      (libsource (lib "eagle-import") (part "ONE_PAD"))
    )
    (comp (ref "U$301")
      (value "ONE_PAD")
      (footprint "eagle-import:1X01")
      (libsource (lib "eagle-import") (part "ONE_PAD"))
    )
    (comp (ref "U$302")
      (value "ONE_PAD")
      (footprint "eagle-import:1X01")
      (libsource (lib "eagle-import") (part "ONE_PAD"))
    )
    (comp (ref "U$303")
      (value "ONE_PAD")
      (footprint "eagle-import:1X01")
      (libsource (lib "eagle-import") (part "ONE_PAD"))
    )
    (comp (ref "U$304")
      (value "ONE_PAD")
      (footprint "eagle-import:1X01")
      (libsource (lib "eagle-import") (part "ONE_PAD"))
    )
    (comp (ref "U$305")
      (value "ONE_PAD")
      (footprint "eagle-import:1X01")
      (libsource (lib "eagle-import") (part "ONE_PAD"))
    )
    (comp (ref "U$306")
      (value "ONE_PAD")
      (footprint "eagle-import:1X01")
      (libsource (lib "eagle-import") (part "ONE_PAD"))
    )
    (comp (ref "U$307")
      (value "ONE_PAD")
      (footprint "eagle-import:1X01")
      (libsource (lib "eagle-import") (part "ONE_PAD"))
    )
    (comp (ref "U$308")
      (value "ONE_PAD")
      (footprint "eagle-import:1X01")
      (libsource (lib "eagle-import") (part "ONE_PAD"))
    )
    (comp (ref "U$309")
      (value "ONE_PAD")
      (footprint "eagle-import:1X01")
      (libsource (lib "eagle-import") (part "ONE_PAD"))
    )
    (comp (ref "U$310")
      (value "ONE_PAD")
      (footprint "eagle-import:1X01")
      (libsource (lib "eagle-import") (part "ONE_PAD"))
    )
    (comp (ref "U$311")
      (value "ONE_PAD")
      (footprint "eagle-import:1X01")
      (libsource (lib "eagle-import") (part "ONE_PAD"))
    )
    (comp (ref "U$312")
      (value "ONE_PAD")
      (footprint "eagle-import:1X01")
      (libsource (lib "eagle-import") (part "ONE_PAD"))
    )
    (comp (ref "U$313")
      (value "ONE_PAD")
      (footprint "eagle-import:1X01")
      (libsource (lib "eagle-import") (part "ONE_PAD"))
    )
    (comp (ref "U$314")
      (value "ONE_PAD")
      (footprint "eagle-import:1X01")
      (libsource (lib "eagle-import") (part "ONE_PAD"))
    )
    (comp (ref "U$315")
      (value "ONE_PAD")
      (footprint "eagle-import:1X01")
      (libsource (lib "eagle-import") (part "ONE_PAD"))
    )
    (comp (ref "U$316")
      (value "ONE_PAD")
      (footprint "eagle-import:1X01")
      (libsource (lib "eagle-import") (part "ONE_PAD"))
    )
    (comp (ref "U$317")
      (value "ONE_PAD")
      (footprint "eagle-import:1X01")
      (libsource (lib "eagle-import") (part "ONE_PAD"))
    )
    (comp (ref "U$318")
      (value "ONE_PAD")
      (footprint "eagle-import:1X01")
      (libsource (lib "eagle-import") (part "ONE_PAD"))
    )
    (comp (ref "U$319")
      (value "ONE_PAD")
      (footprint "eagle-import:1X01")
      (libsource (lib "eagle-import") (part "ONE_PAD"))
    )
    (comp (ref "U$320")
      (value "ONE_PAD")
      (footprint "eagle-import:1X01")
      (libsource (lib "eagle-import") (part "ONE_PAD"))
    )
    (comp (ref "U$321")
      (value "ONE_PAD")
      (footprint "eagle-import:1X01")
      (libsource (lib "eagle-import") (part "ONE_PAD"))
    )
    (comp (ref "U$322")
      (value "ONE_PAD")
      (footprint "eagle-import:1X01")
      (libsource (lib "eagle-import") (part "ONE_PAD"))
    )
    (comp (ref "U$323")
      (value "ONE_PAD")
      (footprint "eagle-import:1X01")
      (libsource (lib "eagle-import") (part "ONE_PAD"))
    )
    (comp (ref "U$324")
      (value "ONE_PAD")
      (footprint "eagle-import:1X01")
      (libsource (lib "eagle-import") (part "ONE_PAD"))
    )
    (comp (ref "U$325")
      (value "ONE_PAD")
      (footprint "eagle-import:1X01")
      (libsource (lib "eagle-import") (part "ONE_PAD"))
    )
    (comp (ref "U$326")
      (value "ONE_PAD")
      (footprint "eagle-import:1X01")
      (libsource (lib "eagle-import") (part "ONE_PAD"))
    )
    (comp (ref "U$327")
      (value "ONE_PAD")
      (footprint "eagle-import:1X01")
      (libsource (lib "eagle-import") (part "ONE_PAD"))
    )
    (comp (ref "U$328")
      (value "ONE_PAD")
      (footprint "eagle-import:1X01")
      (libsource (lib "eagle-import") (part "ONE_PAD"))
    )
    (comp (ref "U$329")
      (value "ONE_PAD")
      (footprint "eagle-import:1X01")
      (libsource (lib "eagle-import") (part "ONE_PAD"))
    )
    (comp (ref "U$330")
      (value "ONE_PAD")
      (footprint "eagle-import:1X01")
      (libsource (lib "eagle-import") (part "ONE_PAD"))
    )
    (comp (ref "U$331")
      (value "ONE_PAD")
      (footprint "eagle-import:1X01")
      (libsource (lib "eagle-import") (part "ONE_PAD"))
    )
    (comp (ref "U$332")
      (value "ONE_PAD")
      (footprint "eagle-import:1X01")
      (libsource (lib "eagle-import") (part "ONE_PAD"))
    )
    (comp (ref "U$333")
      (value "ONE_PAD")
      (footprint "eagle-import:1X01")
      (libsource (lib "eagle-import") (part "ONE_PAD"))
    )
    (comp (ref "U$334")
      (value "ONE_PAD")
      (footprint "eagle-import:1X01")
      (libsource (lib "eagle-import") (part "ONE_PAD"))
    )
    (comp (ref "U$335")
      (value "ONE_PAD")
      (footprint "eagle-import:1X01")
      (libsource (lib "eagle-import") (part "ONE_PAD"))
    )
    (comp (ref "U$336")
      (value "ONE_PAD")
      (footprint "eagle-import:1X01")
      (libsource (lib "eagle-import") (part "ONE_PAD"))
    )
    (comp (ref "U$337")
      (value "ONE_PAD")
      (footprint "eagle-import:1X01")
      (libsource (lib "eagle-import") (part "ONE_PAD"))
    )
    (comp (ref "U$338")
      (value "ONE_PAD")
      (footprint "eagle-import:1X01")
      (libsource (lib "eagle-import") (part "ONE_PAD"))
    )
    (comp (ref "U$339")
      (value "ONE_PAD")
      (footprint "eagle-import:1X01")
      (libsource (lib "eagle-import") (part "ONE_PAD"))
    )
    (comp (ref "U$340")
      (value "ONE_PAD")
      (footprint "eagle-import:1X01")
      (libsource (lib "eagle-import") (part "ONE_PAD"))
    )
    (comp (ref "U$341")
      (value "ONE_PAD")
      (footprint "eagle-import:1X01")
      (libsource (lib "eagle-import") (part "ONE_PAD"))
    )
    (comp (ref "U$342")
      (value "ONE_PAD")
      (footprint "eagle-import:1X01")
      (libsource (lib "eagle-import") (part "ONE_PAD"))
    )
    (comp (ref "U$343")
      (value "ONE_PAD")
      (footprint "eagle-import:1X01")
      (libsource (lib "eagle-import") (part "ONE_PAD"))
    )
    (comp (ref "U$344")
      (value "ONE_PAD")
      (footprint "eagle-import:1X01")
      (libsource (lib "eagle-import") (part "ONE_PAD"))
    )
    (comp (ref "U$345")
      (value "ONE_PAD")
      (footprint "eagle-import:1X01")
      (libsource (lib "eagle-import") (part "ONE_PAD"))
    )
    (comp (ref "U$346")
      (value "ONE_PAD")
      (footprint "eagle-import:1X01")
      (libsource (lib "eagle-import") (part "ONE_PAD"))
    )
    (comp (ref "U$347")
      (value "ONE_PAD")
      (footprint "eagle-import:1X01")
      (libsource (lib "eagle-import") (part "ONE_PAD"))
    )
    (comp (ref "U$348")
      (value "ONE_PAD")
      (footprint "eagle-import:1X01")
      (libsource (lib "eagle-import") (part "ONE_PAD"))
    )
    (comp (ref "U$349")
      (value "ONE_PAD")
      (footprint "eagle-import:1X01")
      (libsource (lib "eagle-import") (part "ONE_PAD"))
    )
    (comp (ref "U$350")
      (value "ONE_PAD")
      (footprint "eagle-import:1X01")
      (libsource (lib "eagle-import") (part "ONE_PAD"))
    )
    (comp (ref "U$351")
      (value "ONE_PAD")
      (footprint "eagle-import:1X01")
      (libsource (lib "eagle-import") (part "ONE_PAD"))
    )
    (comp (ref "U$352")
      (value "ONE_PAD")
      (footprint "eagle-import:1X01")
      (libsource (lib "eagle-import") (part "ONE_PAD"))
    )
    (comp (ref "U$353")
      (value "ONE_PAD")
      (footprint "eagle-import:1X01")
      (libsource (lib "eagle-import") (part "ONE_PAD"))
    )
    (comp (ref "U$354")
      (value "ONE_PAD")
      (footprint "eagle-import:1X01")
      (libsource (lib "eagle-import") (part "ONE_PAD"))
    )
    (comp (ref "U$355")
      (value "ONE_PAD")
      (footprint "eagle-import:1X01")
      (libsource (lib "eagle-import") (part "ONE_PAD"))
    )
    (comp (ref "U$356")
      (value "ONE_PAD")
      (footprint "eagle-import:1X01")
      (libsource (lib "eagle-import") (part "ONE_PAD"))
    )
    (comp (ref "U$357")
      (value "GND")
      (footprint "eagle-import:1X01")
      (libsource (lib "eagle-import") (part "ONE_PAD"))
    )
    (comp (ref "U$358")
      (value "VCC")
      (footprint "eagle-import:1X01")
      (libsource (lib "eagle-import") (part "ONE_PAD"))
    )
    (comp (ref "U$359")
      (value "SDA")
      (footprint "eagle-import:1X01")
      (libsource (lib "eagle-import") (part "ONE_PAD"))
    )
    (comp (ref "U$360")
      (value "SCL")
      (footprint "eagle-import:1X01")
      (libsource (lib "eagle-import") (part "ONE_PAD"))
    )
    (comp (ref "U$361")
      (value "ONE_PAD")
      (footprint "eagle-import:1X01")
      (libsource (lib "eagle-import") (part "ONE_PAD"))
    )
    (comp (ref "U$362")
      (value "ONE_PAD")
      (footprint "eagle-import:1X01")
      (libsource (lib "eagle-import") (part "ONE_PAD"))
    )
    (comp (ref "U$363")
      (value "ONE_PAD")
      (footprint "eagle-import:1X01")
      (libsource (lib "eagle-import") (part "ONE_PAD"))
    )
    (comp (ref "U$364")
      (value "ONE_PAD")
      (footprint "eagle-import:1X01")
      (libsource (lib "eagle-import") (part "ONE_PAD"))
    )
    (comp (ref "U$365")
      (value "ONE_PAD")
      (footprint "eagle-import:1X01")
      (libsource (lib "eagle-import") (part "ONE_PAD"))
    )
    (comp (ref "U$366")
      (value "ONE_PAD")
      (footprint "eagle-import:1X01")
      (libsource (lib "eagle-import") (part "ONE_PAD"))
    )
    (comp (ref "U$367")
      (value "ONE_PAD")
      (footprint "eagle-import:1X01")
      (libsource (lib "eagle-import") (part "ONE_PAD"))
    )
    (comp (ref "U$368")
      (value "ONE_PAD")
      (footprint "eagle-import:1X01")
      (libsource (lib "eagle-import") (part "ONE_PAD"))
    )
    (comp (ref "U$369")
      (value "ONE_PAD")
      (footprint "eagle-import:1X01")
      (libsource (lib "eagle-import") (part "ONE_PAD"))
    )
    (comp (ref "U$370")
      (value "ONE_PAD")
      (footprint "eagle-import:1X01")
      (libsource (lib "eagle-import") (part "ONE_PAD"))
    )
    (comp (ref "U$371")
      (value "ONE_PAD")
      (footprint "eagle-import:1X01")
      (libsource (lib "eagle-import") (part "ONE_PAD"))
    )
    (comp (ref "U$372")
      (value "ONE_PAD")
      (footprint "eagle-import:1X01")
      (libsource (lib "eagle-import") (part "ONE_PAD"))
    )
    (comp (ref "U$373")
      (value "ONE_PAD")
      (footprint "eagle-import:1X01")
      (libsource (lib "eagle-import") (part "ONE_PAD"))
    )
    (comp (ref "U$374")
      (value "ONE_PAD")
      (footprint "eagle-import:1X01")
      (libsource (lib "eagle-import") (part "ONE_PAD"))
    )
    (comp (ref "U$375")
      (value "ONE_PAD")
      (footprint "eagle-import:1X01")
      (libsource (lib "eagle-import") (part "ONE_PAD"))
    )
    (comp (ref "U$376")
      (value "ONE_PAD")
      (footprint "eagle-import:1X01")
      (libsource (lib "eagle-import") (part "ONE_PAD"))
    )
    (comp (ref "U$377")
      (value "ONE_PAD")
      (footprint "eagle-import:1X01")
      (libsource (lib "eagle-import") (part "ONE_PAD"))
    )
    (comp (ref "U$378")
      (value "ONE_PAD")
      (footprint "eagle-import:1X01")
      (libsource (lib "eagle-import") (part "ONE_PAD"))
    )
    (comp (ref "U$379")
      (value "ONE_PAD")
      (footprint "eagle-import:1X01")
      (libsource (lib "eagle-import") (part "ONE_PAD"))
    )
    (comp (ref "U$380")
      (value "ONE_PAD")
      (footprint "eagle-import:1X01")
      (libsource (lib "eagle-import") (part "ONE_PAD"))
    )
    (comp (ref "U$381")
      (value "ONE_PAD")
      (footprint "eagle-import:1X01")
      (libsource (lib "eagle-import") (part "ONE_PAD"))
    )
    (comp (ref "U$382")
      (value "ONE_PAD")
      (footprint "eagle-import:1X01")
      (libsource (lib "eagle-import") (part "ONE_PAD"))
    )
    (comp (ref "U$383")
      (value "ONE_PAD")
      (footprint "eagle-import:1X01")
      (libsource (lib "eagle-import") (part "ONE_PAD"))
    )
    (comp (ref "U$384")
      (value "ONE_PAD")
      (footprint "eagle-import:1X01")
      (libsource (lib "eagle-import") (part "ONE_PAD"))
    )
    (comp (ref "U$385")
      (value "ONE_PAD")
      (footprint "eagle-import:1X01")
      (libsource (lib "eagle-import") (part "ONE_PAD"))
    )
    (comp (ref "U$386")
      (value "ONE_PAD")
      (footprint "eagle-import:1X01")
      (libsource (lib "eagle-import") (part "ONE_PAD"))
    )
    (comp (ref "U$387")
      (value "ONE_PAD")
      (footprint "eagle-import:1X01")
      (libsource (lib "eagle-import") (part "ONE_PAD"))
    )
    (comp (ref "U$388")
      (value "ONE_PAD")
      (footprint "eagle-import:1X01")
      (libsource (lib "eagle-import") (part "ONE_PAD"))
    )
    (comp (ref "U$389")
      (value "ONE_PAD")
      (footprint "eagle-import:1X01")
      (libsource (lib "eagle-import") (part "ONE_PAD"))
    )
    (comp (ref "U$390")
      (value "ONE_PAD")
      (footprint "eagle-import:1X01")
      (libsource (lib "eagle-import") (part "ONE_PAD"))
    )
    (comp (ref "U$391")
      (value "ONE_PAD")
      (footprint "eagle-import:1X01")
      (libsource (lib "eagle-import") (part "ONE_PAD"))
    )
    (comp (ref "U$392")
      (value "ONE_PAD")
      (footprint "eagle-import:1X01")
      (libsource (lib "eagle-import") (part "ONE_PAD"))
    )
    (comp (ref "U$393")
      (value "ONE_PAD")
      (footprint "eagle-import:1X01")
      (libsource (lib "eagle-import") (part "ONE_PAD"))
    )
    (comp (ref "U$394")
      (value "ONE_PAD")
      (footprint "eagle-import:1X01")
      (libsource (lib "eagle-import") (part "ONE_PAD"))
    )
    (comp (ref "U$395")
      (value "ONE_PAD")
      (footprint "eagle-import:1X01")
      (libsource (lib "eagle-import") (part "ONE_PAD"))
    )
    (comp (ref "U$396")
      (value "ONE_PAD")
      (footprint "eagle-import:1X01")
      (libsource (lib "eagle-import") (part "ONE_PAD"))
    )
    (comp (ref "U$397")
      (value "ONE_PAD")
      (footprint "eagle-import:1X01")
      (libsource (lib "eagle-import") (part "ONE_PAD"))
    )
    (comp (ref "U$398")
      (value "ONE_PAD")
      (footprint "eagle-import:1X01")
      (libsource (lib "eagle-import") (part "ONE_PAD"))
    )
    (comp (ref "U$399")
      (value "ONE_PAD")
      (footprint "eagle-import:1X01")
      (libsource (lib "eagle-import") (part "ONE_PAD"))
    )
    (comp (ref "U$400")
      (value "ONE_PAD")
      (footprint "eagle-import:1X01")
      (libsource (lib "eagle-import") (part "ONE_PAD"))
    )
    (comp (ref "U$401")
      (value "ONE_PAD")
      (footprint "eagle-import:1X01")
      (libsource (lib "eagle-import") (part "ONE_PAD"))
    )
    (comp (ref "U$402")
      (value "ONE_PAD")
      (footprint "eagle-import:1X01")
      (libsource (lib "eagle-import") (part "ONE_PAD"))
    )
    (comp (ref "U$403")
      (value "ONE_PAD")
      (footprint "eagle-import:1X01")
      (libsource (lib "eagle-import") (part "ONE_PAD"))
    )
    (comp (ref "U$404")
      (value "ONE_PAD")
      (footprint "eagle-import:1X01")
      (libsource (lib "eagle-import") (part "ONE_PAD"))
    )
    (comp (ref "U$405")
      (value "ONE_PAD")
      (footprint "eagle-import:1X01")
      (libsource (lib "eagle-import") (part "ONE_PAD"))
    )
    (comp (ref "U$406")
      (value "ONE_PAD")
      (footprint "eagle-import:1X01")
      (libsource (lib "eagle-import") (part "ONE_PAD"))
    )
    (comp (ref "U$407")
      (value "DECOUPLING_CAP")
      (footprint "eagle-import:DECOUPLING_CAP")
      (libsource (lib "eagle-import") (part "DECOUPLING_CAP"))
    )
    (comp (ref "U$408")
      (value "RESISTOR")
      (footprint "eagle-import:AXIAL-0.3")
      (libsource (lib "eagle-import") (part "RESISTOR"))
    )
    (comp (ref "U$409")
      (value "RESISTOR")
      (footprint "eagle-import:AXIAL-0.3")
      (libsource (lib "eagle-import") (part "RESISTOR"))
    )
    (comp (ref "U$410")
      (value "ONE_PAD")
      (footprint "eagle-import:1X01")
      (libsource (lib "eagle-import") (part "ONE_PAD"))
    )
    (comp (ref "U$411")
      (value "ONE_PAD")
      (footprint "eagle-import:1X01")
      (libsource (lib "eagle-import") (part "ONE_PAD"))
    )
    (comp (ref "U$412")
      (value "ONE_PAD")
      (footprint "eagle-import:1X01")
      (libsource (lib "eagle-import") (part "ONE_PAD"))
    )
    (comp (ref "U$413")
      (value "ONE_PAD")
      (footprint "eagle-import:1X01")
      (libsource (lib "eagle-import") (part "ONE_PAD"))
    )
    (comp (ref "U$414")
      (value "ONE_PAD")
      (footprint "eagle-import:1X01")
      (libsource (lib "eagle-import") (part "ONE_PAD"))
    )
    (comp (ref "U$415")
      (value "ONE_PAD")
      (footprint "eagle-import:1X01")
      (libsource (lib "eagle-import") (part "ONE_PAD"))
    )
    (comp (ref "U$416")
      (value "ONE_PAD")
      (footprint "eagle-import:1X01")
      (libsource (lib "eagle-import") (part "ONE_PAD"))
    )
    (comp (ref "U$417")
      (value "ONE_PAD")
      (footprint "eagle-import:1X01")
      (libsource (lib "eagle-import") (part "ONE_PAD"))
    )
    (comp (ref "U$418")
      (value "ONE_PAD")
      (footprint "eagle-import:1X01")
      (libsource (lib "eagle-import") (part "ONE_PAD"))
    )
    (comp (ref "U$419")
      (value "ONE_PAD")
      (footprint "eagle-import:1X01")
      (libsource (lib "eagle-import") (part "ONE_PAD"))
    )
    (comp (ref "U$420")
      (value "ONE_PAD")
      (footprint "eagle-import:1X01")
      (libsource (lib "eagle-import") (part "ONE_PAD"))
    )
    (comp (ref "U$421")
      (value "ONE_PAD")
      (footprint "eagle-import:1X01")
      (libsource (lib "eagle-import") (part "ONE_PAD"))
    )
    (comp (ref "U$422")
      (value "ONE_PAD")
      (footprint "eagle-import:1X01")
      (libsource (lib "eagle-import") (part "ONE_PAD"))
    )
    (comp (ref "U$423")
      (value "ONE_PAD")
      (footprint "eagle-import:1X01")
      (libsource (lib "eagle-import") (part "ONE_PAD"))
    )
    (comp (ref "U$424")
      (value "ONE_PAD")
      (footprint "eagle-import:1X01")
      (libsource (lib "eagle-import") (part "ONE_PAD"))
    )
    (comp (ref "U$425")
      (value "ONE_PAD")
      (footprint "eagle-import:1X01")
      (libsource (lib "eagle-import") (part "ONE_PAD"))
    )
    (comp (ref "U$426")
      (value "ONE_PAD")
      (footprint "eagle-import:1X01")
      (libsource (lib "eagle-import") (part "ONE_PAD"))
    )
    (comp (ref "U$427")
      (value "ONE_PAD")
      (footprint "eagle-import:1X01")
      (libsource (lib "eagle-import") (part "ONE_PAD"))
    )
    (comp (ref "U$428")
      (value "ONE_PAD")
      (footprint "eagle-import:1X01")
      (libsource (lib "eagle-import") (part "ONE_PAD"))
    )
    (comp (ref "U$429")
      (value "ONE_PAD")
      (footprint "eagle-import:1X01")
      (libsource (lib "eagle-import") (part "ONE_PAD"))
    )
    (comp (ref "U$430")
      (value "ONE_PAD")
      (footprint "eagle-import:1X01")
      (libsource (lib "eagle-import") (part "ONE_PAD"))
    )
    (comp (ref "U$431")
      (value "ONE_PAD")
      (footprint "eagle-import:1X01")
      (libsource (lib "eagle-import") (part "ONE_PAD"))
    )
    (comp (ref "U$432")
      (value "ONE_PAD")
      (footprint "eagle-import:1X01")
      (libsource (lib "eagle-import") (part "ONE_PAD"))
    )
    (comp (ref "U$433")
      (value "ONE_PAD")
      (footprint "eagle-import:1X01")
      (libsource (lib "eagle-import") (part "ONE_PAD"))
    )
    (comp (ref "U$434")
      (value "ONE_PAD")
      (footprint "eagle-import:1X01")
      (libsource (lib "eagle-import") (part "ONE_PAD"))
    )
    (comp (ref "U$435")
      (value "ONE_PAD")
      (footprint "eagle-import:1X01")
      (libsource (lib "eagle-import") (part "ONE_PAD"))
    )
    (comp (ref "U$436")
      (value "ONE_PAD")
      (footprint "eagle-import:1X01")
      (libsource (lib "eagle-import") (part "ONE_PAD"))
    )
    (comp (ref "U$437")
      (value "ONE_PAD")
      (footprint "eagle-import:1X01")
      (libsource (lib "eagle-import") (part "ONE_PAD"))
    )
    (comp (ref "U$438")
      (value "ONE_PAD")
      (footprint "eagle-import:1X01")
      (libsource (lib "eagle-import") (part "ONE_PAD"))
    )
    (comp (ref "U$439")
      (value "ONE_PAD")
      (footprint "eagle-import:1X01")
      (libsource (lib "eagle-import") (part "ONE_PAD"))
    )
    (comp (ref "U$440")
      (value "ONE_PAD")
      (footprint "eagle-import:1X01")
      (libsource (lib "eagle-import") (part "ONE_PAD"))
    )
    (comp (ref "U$441")
      (value "ONE_PAD")
      (footprint "eagle-import:1X01")
      (libsource (lib "eagle-import") (part "ONE_PAD"))
    )
    (comp (ref "U$442")
      (value "ONE_PAD")
      (footprint "eagle-import:1X01")
      (libsource (lib "eagle-import") (part "ONE_PAD"))
    )
    (comp (ref "U$443")
      (value "ONE_PAD")
      (footprint "eagle-import:1X01")
      (libsource (lib "eagle-import") (part "ONE_PAD"))
    )
    (comp (ref "U$444")
      (value "ONE_PAD")
      (footprint "eagle-import:1X01")
      (libsource (lib "eagle-import") (part "ONE_PAD"))
    )
    (comp (ref "U$445")
      (value "ONE_PAD")
      (footprint "eagle-import:1X01")
      (libsource (lib "eagle-import") (part "ONE_PAD"))
    )
    (comp (ref "U$446")
      (value "ONE_PAD")
      (footprint "eagle-import:1X01")
      (libsource (lib "eagle-import") (part "ONE_PAD"))
    )
    (comp (ref "U$447")
      (value "ONE_PAD")
      (footprint "eagle-import:1X01")
      (libsource (lib "eagle-import") (part "ONE_PAD"))
    )
    (comp (ref "U$448")
      (value "ONE_PAD")
      (footprint "eagle-import:1X01")
      (libsource (lib "eagle-import") (part "ONE_PAD"))
    )
    (comp (ref "U$449")
      (value "ONE_PAD")
      (footprint "eagle-import:1X01")
      (libsource (lib "eagle-import") (part "ONE_PAD"))
    )
    (comp (ref "U$450")
      (value "ONE_PAD")
      (footprint "eagle-import:1X01")
      (libsource (lib "eagle-import") (part "ONE_PAD"))
    )
    (comp (ref "U$451")
      (value "ONE_PAD")
      (footprint "eagle-import:1X01")
      (libsource (lib "eagle-import") (part "ONE_PAD"))
    )
    (comp (ref "U$452")
      (value "ONE_PAD")
      (footprint "eagle-import:1X01")
      (libsource (lib "eagle-import") (part "ONE_PAD"))
    )
    (comp (ref "U$453")
      (value "ONE_PAD")
      (footprint "eagle-import:1X01")
      (libsource (lib "eagle-import") (part "ONE_PAD"))
    )
    (comp (ref "U$454")
      (value "ONE_PAD")
      (footprint "eagle-import:1X01")
      (libsource (lib "eagle-import") (part "ONE_PAD"))
    )
    (comp (ref "U$455")
      (value "ONE_PAD")
      (footprint "eagle-import:1X01")
      (libsource (lib "eagle-import") (part "ONE_PAD"))
    )
    (comp (ref "U$456")
      (value "ONE_PAD")
      (footprint "eagle-import:1X01")
      (libsource (lib "eagle-import") (part "ONE_PAD"))
    )
    (comp (ref "U$457")
      (value "ONE_PAD")
      (footprint "eagle-import:1X01")
      (libsource (lib "eagle-import") (part "ONE_PAD"))
    )
    (comp (ref "U$458")
      (value "ONE_PAD")
      (footprint "eagle-import:1X01")
      (libsource (lib "eagle-import") (part "ONE_PAD"))
    )
    (comp (ref "U$459")
      (value "ONE_PAD")
      (footprint "eagle-import:1X01")
      (libsource (lib "eagle-import") (part "ONE_PAD"))
    )
    (comp (ref "U$460")
      (value "ONE_PAD")
      (footprint "eagle-import:1X01")
      (libsource (lib "eagle-import") (part "ONE_PAD"))
    )
    (comp (ref "U$461")
      (value "ONE_PAD")
      (footprint "eagle-import:1X01")
      (libsource (lib "eagle-import") (part "ONE_PAD"))
    )
    (comp (ref "U$462")
      (value "ONE_PAD")
      (footprint "eagle-import:1X01")
      (libsource (lib "eagle-import") (part "ONE_PAD"))
    )
    (comp (ref "U$463")
      (value "ONE_PAD")
      (footprint "eagle-import:1X01")
      (libsource (lib "eagle-import") (part "ONE_PAD"))
    )
    (comp (ref "U$464")
      (value "ONE_PAD")
      (footprint "eagle-import:1X01")
      (libsource (lib "eagle-import") (part "ONE_PAD"))
    )
    (comp (ref "U$465")
      (value "ONE_PAD")
      (footprint "eagle-import:1X01")
      (libsource (lib "eagle-import") (part "ONE_PAD"))
    )
    (comp (ref "U$466")
      (value "ONE_PAD")
      (footprint "eagle-import:1X01")
      (libsource (lib "eagle-import") (part "ONE_PAD"))
    )
    (comp (ref "U$467")
      (value "ONE_PAD")
      (footprint "eagle-import:1X01")
      (libsource (lib "eagle-import") (part "ONE_PAD"))
    )
    (comp (ref "U$468")
      (value "ONE_PAD")
      (footprint "eagle-import:1X01")
      (libsource (lib "eagle-import") (part "ONE_PAD"))
    )
    (comp (ref "U$469")
      (value "ONE_PAD")
      (footprint "eagle-import:1X01")
      (libsource (lib "eagle-import") (part "ONE_PAD"))
    )
    (comp (ref "U$470")
      (value "ONE_PAD")
      (footprint "eagle-import:1X01")
      (libsource (lib "eagle-import") (part "ONE_PAD"))
    )
    (comp (ref "U$471")
      (value "ONE_PAD")
      (footprint "eagle-import:1X01")
      (libsource (lib "eagle-import") (part "ONE_PAD"))
    )
    (comp (ref "U$472")
      (value "ONE_PAD")
      (footprint "eagle-import:1X01")
      (libsource (lib "eagle-import") (part "ONE_PAD"))
    )
    (comp (ref "U$473")
      (value "ONE_PAD")
      (footprint "eagle-import:1X01")
      (libsource (lib "eagle-import") (part "ONE_PAD"))
    )
    (comp (ref "U$474")
      (value "ONE_PAD")
      (footprint "eagle-import:1X01")
      (libsource (lib "eagle-import") (part "ONE_PAD"))
    )
    (comp (ref "U$475")
      (value "ONE_PAD")
      (footprint "eagle-import:1X01")
      (libsource (lib "eagle-import") (part "ONE_PAD"))
    )
    (comp (ref "U$476")
      (value "ONE_PAD")
      (footprint "eagle-import:1X01")
      (libsource (lib "eagle-import") (part "ONE_PAD"))
    )
    (comp (ref "U$477")
      (value "ONE_PAD")
      (footprint "eagle-import:1X01")
      (libsource (lib "eagle-import") (part "ONE_PAD"))
    )
    (comp (ref "U$478")
      (value "ONE_PAD")
      (footprint "eagle-import:1X01")
      (libsource (lib "eagle-import") (part "ONE_PAD"))
    )
    (comp (ref "U$479")
      (value "ONE_PAD")
      (footprint "eagle-import:1X01")
      (libsource (lib "eagle-import") (part "ONE_PAD"))
    )
    (comp (ref "U$480")
      (value "ONE_PAD")
      (footprint "eagle-import:1X01")
      (libsource (lib "eagle-import") (part "ONE_PAD"))
    )
    (comp (ref "U$481")
      (value "ONE_PAD")
      (footprint "eagle-import:1X01")
      (libsource (lib "eagle-import") (part "ONE_PAD"))
    )
    (comp (ref "U$482")
      (value "ONE_PAD")
      (footprint "eagle-import:1X01")
      (libsource (lib "eagle-import") (part "ONE_PAD"))
    )
    (comp (ref "U$483")
      (value "ONE_PAD")
      (footprint "eagle-import:1X01")
      (libsource (lib "eagle-import") (part "ONE_PAD"))
    )
    (comp (ref "U$484")
      (value "ONE_PAD")
      (footprint "eagle-import:1X01")
      (libsource (lib "eagle-import") (part "ONE_PAD"))
    )
    (comp (ref "U$485")
      (value "ONE_PAD")
      (footprint "eagle-import:1X01")
      (libsource (lib "eagle-import") (part "ONE_PAD"))
    )
    (comp (ref "U$486")
      (value "ONE_PAD")
      (footprint "eagle-import:1X01")
      (libsource (lib "eagle-import") (part "ONE_PAD"))
    )
    (comp (ref "U$487")
      (value "ONE_PAD")
      (footprint "eagle-import:1X01")
      (libsource (lib "eagle-import") (part "ONE_PAD"))
    )
    (comp (ref "U$488")
      (value "ONE_PAD")
      (footprint "eagle-import:1X01")
      (libsource (lib "eagle-import") (part "ONE_PAD"))
    )
    (comp (ref "U$489")
      (value "ONE_PAD")
      (footprint "eagle-import:1X01")
      (libsource (lib "eagle-import") (part "ONE_PAD"))
    )
    (comp (ref "U$490")
      (value "ONE_PAD")
      (footprint "eagle-import:1X01")
      (libsource (lib "eagle-import") (part "ONE_PAD"))
    )
    (comp (ref "U$491")
      (value "ONE_PAD")
      (footprint "eagle-import:1X01")
      (libsource (lib "eagle-import") (part "ONE_PAD"))
    )
    (comp (ref "U$492")
      (value "ONE_PAD")
      (footprint "eagle-import:1X01")
      (libsource (lib "eagle-import") (part "ONE_PAD"))
    )
    (comp (ref "U$493")
      (value "ONE_PAD")
      (footprint "eagle-import:1X01")
      (libsource (lib "eagle-import") (part "ONE_PAD"))
    )
    (comp (ref "U$494")
      (value "ONE_PAD")
      (footprint "eagle-import:1X01")
      (libsource (lib "eagle-import") (part "ONE_PAD"))
    )
    (comp (ref "U$495")
      (value "ONE_PAD")
      (footprint "eagle-import:1X01")
      (libsource (lib "eagle-import") (part "ONE_PAD"))
    )
    (comp (ref "U$496")
      (value "ONE_PAD")
      (footprint "eagle-import:1X01")
      (libsource (lib "eagle-import") (part "ONE_PAD"))
    )
    (comp (ref "U$497")
      (value "ONE_PAD")
      (footprint "eagle-import:1X01")
      (libsource (lib "eagle-import") (part "ONE_PAD"))
    )
    (comp (ref "U$498")
      (value "ONE_PAD")
      (footprint "eagle-import:1X01")
      (libsource (lib "eagle-import") (part "ONE_PAD"))
    )
    (comp (ref "U$499")
      (value "ONE_PAD")
      (footprint "eagle-import:1X01")
      (libsource (lib "eagle-import") (part "ONE_PAD"))
    )
    (comp (ref "U$500")
      (value "GND")
      (footprint "eagle-import:1X01")
      (libsource (lib "eagle-import") (part "ONE_PAD"))
    )
    (comp (ref "U$501")
      (value "VCC")
      (footprint "eagle-import:1X01")
      (libsource (lib "eagle-import") (part "ONE_PAD"))
    )
    (comp (ref "U$502")
      (value "SDA")
      (footprint "eagle-import:1X01")
      (libsource (lib "eagle-import") (part "ONE_PAD"))
    )
    (comp (ref "U$503")
      (value "SCL")
      (footprint "eagle-import:1X01")
      (libsource (lib "eagle-import") (part "ONE_PAD"))
    )
    (comp (ref "U$504")
      (value "ONE_PAD")
      (footprint "eagle-import:1X01")
      (libsource (lib "eagle-import") (part "ONE_PAD"))
    )
    (comp (ref "U$505")
      (value "ONE_PAD")
      (footprint "eagle-import:1X01")
      (libsource (lib "eagle-import") (part "ONE_PAD"))
    )
    (comp (ref "U$506")
      (value "ONE_PAD")
      (footprint "eagle-import:1X01")
      (libsource (lib "eagle-import") (part "ONE_PAD"))
    )
    (comp (ref "U$507")
      (value "ONE_PAD")
      (footprint "eagle-import:1X01")
      (libsource (lib "eagle-import") (part "ONE_PAD"))
    )
    (comp (ref "U$508")
      (value "ONE_PAD")
      (footprint "eagle-import:1X01")
      (libsource (lib "eagle-import") (part "ONE_PAD"))
    )
    (comp (ref "U$509")
      (value "ONE_PAD")
      (footprint "eagle-import:1X01")
      (libsource (lib "eagle-import") (part "ONE_PAD"))
    )
    (comp (ref "U$510")
      (value "ONE_PAD")
      (footprint "eagle-import:1X01")
      (libsource (lib "eagle-import") (part "ONE_PAD"))
    )
    (comp (ref "U$511")
      (value "ONE_PAD")
      (footprint "eagle-import:1X01")
      (libsource (lib "eagle-import") (part "ONE_PAD"))
    )
    (comp (ref "U$512")
      (value "ONE_PAD")
      (footprint "eagle-import:1X01")
      (libsource (lib "eagle-import") (part "ONE_PAD"))
    )
    (comp (ref "U$513")
      (value "ONE_PAD")
      (footprint "eagle-import:1X01")
      (libsource (lib "eagle-import") (part "ONE_PAD"))
    )
    (comp (ref "U$514")
      (value "ONE_PAD")
      (footprint "eagle-import:1X01")
      (libsource (lib "eagle-import") (part "ONE_PAD"))
    )
    (comp (ref "U$515")
      (value "ONE_PAD")
      (footprint "eagle-import:1X01")
      (libsource (lib "eagle-import") (part "ONE_PAD"))
    )
    (comp (ref "U$516")
      (value "ONE_PAD")
      (footprint "eagle-import:1X01")
      (libsource (lib "eagle-import") (part "ONE_PAD"))
    )
    (comp (ref "U$517")
      (value "ONE_PAD")
      (footprint "eagle-import:1X01")
      (libsource (lib "eagle-import") (part "ONE_PAD"))
    )
    (comp (ref "U$518")
      (value "ONE_PAD")
      (footprint "eagle-import:1X01")
      (libsource (lib "eagle-import") (part "ONE_PAD"))
    )
    (comp (ref "U$519")
      (value "ONE_PAD")
      (footprint "eagle-import:1X01")
      (libsource (lib "eagle-import") (part "ONE_PAD"))
    )
    (comp (ref "U$520")
      (value "ONE_PAD")
      (footprint "eagle-import:1X01")
      (libsource (lib "eagle-import") (part "ONE_PAD"))
    )
    (comp (ref "U$521")
      (value "ONE_PAD")
      (footprint "eagle-import:1X01")
      (libsource (lib "eagle-import") (part "ONE_PAD"))
    )
    (comp (ref "U$522")
      (value "ONE_PAD")
      (footprint "eagle-import:1X01")
      (libsource (lib "eagle-import") (part "ONE_PAD"))
    )
    (comp (ref "U$523")
      (value "ONE_PAD")
      (footprint "eagle-import:1X01")
      (libsource (lib "eagle-import") (part "ONE_PAD"))
    )
    (comp (ref "U$524")
      (value "ONE_PAD")
      (footprint "eagle-import:1X01")
      (libsource (lib "eagle-import") (part "ONE_PAD"))
    )
    (comp (ref "U$525")
      (value "ONE_PAD")
      (footprint "eagle-import:1X01")
      (libsource (lib "eagle-import") (part "ONE_PAD"))
    )
    (comp (ref "U$526")
      (value "ONE_PAD")
      (footprint "eagle-import:1X01")
      (libsource (lib "eagle-import") (part "ONE_PAD"))
    )
    (comp (ref "U$527")
      (value "ONE_PAD")
      (footprint "eagle-import:1X01")
      (libsource (lib "eagle-import") (part "ONE_PAD"))
    )
    (comp (ref "U$528")
      (value "ONE_PAD")
      (footprint "eagle-import:1X01")
      (libsource (lib "eagle-import") (part "ONE_PAD"))
    )
    (comp (ref "U$529")
      (value "ONE_PAD")
      (footprint "eagle-import:1X01")
      (libsource (lib "eagle-import") (part "ONE_PAD"))
    )
    (comp (ref "U$530")
      (value "ONE_PAD")
      (footprint "eagle-import:1X01")
      (libsource (lib "eagle-import") (part "ONE_PAD"))
    )
    (comp (ref "U$531")
      (value "ONE_PAD")
      (footprint "eagle-import:1X01")
      (libsource (lib "eagle-import") (part "ONE_PAD"))
    )
    (comp (ref "U$532")
      (value "ONE_PAD")
      (footprint "eagle-import:1X01")
      (libsource (lib "eagle-import") (part "ONE_PAD"))
    )
    (comp (ref "U$533")
      (value "ONE_PAD")
      (footprint "eagle-import:1X01")
      (libsource (lib "eagle-import") (part "ONE_PAD"))
    )
    (comp (ref "U$534")
      (value "ONE_PAD")
      (footprint "eagle-import:1X01")
      (libsource (lib "eagle-import") (part "ONE_PAD"))
    )
    (comp (ref "U$535")
      (value "ONE_PAD")
      (footprint "eagle-import:1X01")
      (libsource (lib "eagle-import") (part "ONE_PAD"))
    )
    (comp (ref "U$536")
      (value "ONE_PAD")
      (footprint "eagle-import:1X01")
      (libsource (lib "eagle-import") (part "ONE_PAD"))
    )
    (comp (ref "U$537")
      (value "ONE_PAD")
      (footprint "eagle-import:1X01")
      (libsource (lib "eagle-import") (part "ONE_PAD"))
    )
    (comp (ref "U$538")
      (value "ONE_PAD")
      (footprint "eagle-import:1X01")
      (libsource (lib "eagle-import") (part "ONE_PAD"))
    )
    (comp (ref "U$539")
      (value "ONE_PAD")
      (footprint "eagle-import:1X01")
      (libsource (lib "eagle-import") (part "ONE_PAD"))
    )
    (comp (ref "U$540")
      (value "ONE_PAD")
      (footprint "eagle-import:1X01")
      (libsource (lib "eagle-import") (part "ONE_PAD"))
    )
    (comp (ref "U$541")
      (value "ONE_PAD")
      (footprint "eagle-import:1X01")
      (libsource (lib "eagle-import") (part "ONE_PAD"))
    )
    (comp (ref "U$542")
      (value "ONE_PAD")
      (footprint "eagle-import:1X01")
      (libsource (lib "eagle-import") (part "ONE_PAD"))
    )
    (comp (ref "U$543")
      (value "ONE_PAD")
      (footprint "eagle-import:1X01")
      (libsource (lib "eagle-import") (part "ONE_PAD"))
    )
    (comp (ref "U$544")
      (value "ONE_PAD")
      (footprint "eagle-import:1X01")
      (libsource (lib "eagle-import") (part "ONE_PAD"))
    )
    (comp (ref "U$545")
      (value "ONE_PAD")
      (footprint "eagle-import:1X01")
      (libsource (lib "eagle-import") (part "ONE_PAD"))
    )
    (comp (ref "U$546")
      (value "ONE_PAD")
      (footprint "eagle-import:1X01")
      (libsource (lib "eagle-import") (part "ONE_PAD"))
    )
    (comp (ref "U$547")
      (value "ONE_PAD")
      (footprint "eagle-import:1X01")
      (libsource (lib "eagle-import") (part "ONE_PAD"))
    )
    (comp (ref "U$548")
      (value "ONE_PAD")
      (footprint "eagle-import:1X01")
      (libsource (lib "eagle-import") (part "ONE_PAD"))
    )
    (comp (ref "U$549")
      (value "ONE_PAD")
      (footprint "eagle-import:1X01")
      (libsource (lib "eagle-import") (part "ONE_PAD"))
    )
    (comp (ref "U$550")
      (value "DECOUPLING_CAP")
      (footprint "eagle-import:DECOUPLING_CAP")
      (libsource (lib "eagle-import") (part "DECOUPLING_CAP"))
    )
    (comp (ref "U$551")
      (value "RESISTOR")
      (footprint "eagle-import:AXIAL-0.3")
      (libsource (lib "eagle-import") (part "RESISTOR"))
    )
    (comp (ref "U$552")
      (value "RESISTOR")
      (footprint "eagle-import:AXIAL-0.3")
      (libsource (lib "eagle-import") (part "RESISTOR"))
    )
    (comp (ref "U$553")
      (value "ONE_PAD")
      (footprint "eagle-import:1X01")
      (libsource (lib "eagle-import") (part "ONE_PAD"))
    )
    (comp (ref "U$554")
      (value "ONE_PAD")
      (footprint "eagle-import:1X01")
      (libsource (lib "eagle-import") (part "ONE_PAD"))
    )
    (comp (ref "U$555")
      (value "ONE_PAD")
      (footprint "eagle-import:1X01")
      (libsource (lib "eagle-import") (part "ONE_PAD"))
    )
    (comp (ref "U$556")
      (value "ONE_PAD")
      (footprint "eagle-import:1X01")
      (libsource (lib "eagle-import") (part "ONE_PAD"))
    )
    (comp (ref "U$557")
      (value "ONE_PAD")
      (footprint "eagle-import:1X01")
      (libsource (lib "eagle-import") (part "ONE_PAD"))
    )
    (comp (ref "U$558")
      (value "ONE_PAD")
      (footprint "eagle-import:1X01")
      (libsource (lib "eagle-import") (part "ONE_PAD"))
    )
    (comp (ref "U$559")
      (value "ONE_PAD")
      (footprint "eagle-import:1X01")
      (libsource (lib "eagle-import") (part "ONE_PAD"))
    )
    (comp (ref "U$560")
      (value "ONE_PAD")
      (footprint "eagle-import:1X01")
      (libsource (lib "eagle-import") (part "ONE_PAD"))
    )
    (comp (ref "U$561")
      (value "ONE_PAD")
      (footprint "eagle-import:1X01")
      (libsource (lib "eagle-import") (part "ONE_PAD"))
    )
    (comp (ref "U$562")
      (value "ONE_PAD")
      (footprint "eagle-import:1X01")
      (libsource (lib "eagle-import") (part "ONE_PAD"))
    )
    (comp (ref "U$563")
      (value "ONE_PAD")
      (footprint "eagle-import:1X01")
      (libsource (lib "eagle-import") (part "ONE_PAD"))
    )
    (comp (ref "U$564")
      (value "ONE_PAD")
      (footprint "eagle-import:1X01")
      (libsource (lib "eagle-import") (part "ONE_PAD"))
    )
    (comp (ref "U$565")
      (value "ONE_PAD")
      (footprint "eagle-import:1X01")
      (libsource (lib "eagle-import") (part "ONE_PAD"))
    )
    (comp (ref "U$566")
      (value "ONE_PAD")
      (footprint "eagle-import:1X01")
      (libsource (lib "eagle-import") (part "ONE_PAD"))
    )
    (comp (ref "U$567")
      (value "ONE_PAD")
      (footprint "eagle-import:1X01")
      (libsource (lib "eagle-import") (part "ONE_PAD"))
    )
    (comp (ref "U$568")
      (value "ONE_PAD")
      (footprint "eagle-import:1X01")
      (libsource (lib "eagle-import") (part "ONE_PAD"))
    )
    (comp (ref "U$569")
      (value "ONE_PAD")
      (footprint "eagle-import:1X01")
      (libsource (lib "eagle-import") (part "ONE_PAD"))
    )
    (comp (ref "U$570")
      (value "ONE_PAD")
      (footprint "eagle-import:1X01")
      (libsource (lib "eagle-import") (part "ONE_PAD"))
    )
    (comp (ref "U$571")
      (value "ONE_PAD")
      (footprint "eagle-import:1X01")
      (libsource (lib "eagle-import") (part "ONE_PAD"))
    )
    (comp (ref "U$572")
      (value "ONE_PAD")
      (footprint "eagle-import:1X01")
      (libsource (lib "eagle-import") (part "ONE_PAD"))
    )
    (comp (ref "U$573")
      (value "ONE_PAD")
      (footprint "eagle-import:1X01")
      (libsource (lib "eagle-import") (part "ONE_PAD"))
    )
    (comp (ref "U$574")
      (value "ONE_PAD")
      (footprint "eagle-import:1X01")
      (libsource (lib "eagle-import") (part "ONE_PAD"))
    )
    (comp (ref "U$575")
      (value "ONE_PAD")
      (footprint "eagle-import:1X01")
      (libsource (lib "eagle-import") (part "ONE_PAD"))
    )
    (comp (ref "U$576")
      (value "ONE_PAD")
      (footprint "eagle-import:1X01")
      (libsource (lib "eagle-import") (part "ONE_PAD"))
    )
    (comp (ref "U$577")
      (value "ONE_PAD")
      (footprint "eagle-import:1X01")
      (libsource (lib "eagle-import") (part "ONE_PAD"))
    )
    (comp (ref "U$578")
      (value "ONE_PAD")
      (footprint "eagle-import:1X01")
      (libsource (lib "eagle-import") (part "ONE_PAD"))
    )
    (comp (ref "U$579")
      (value "ONE_PAD")
      (footprint "eagle-import:1X01")
      (libsource (lib "eagle-import") (part "ONE_PAD"))
    )
    (comp (ref "U$580")
      (value "ONE_PAD")
      (footprint "eagle-import:1X01")
      (libsource (lib "eagle-import") (part "ONE_PAD"))
    )
    (comp (ref "U$581")
      (value "ONE_PAD")
      (footprint "eagle-import:1X01")
      (libsource (lib "eagle-import") (part "ONE_PAD"))
    )
    (comp (ref "U$582")
      (value "ONE_PAD")
      (footprint "eagle-import:1X01")
      (libsource (lib "eagle-import") (part "ONE_PAD"))
    )
    (comp (ref "U$583")
      (value "ONE_PAD")
      (footprint "eagle-import:1X01")
      (libsource (lib "eagle-import") (part "ONE_PAD"))
    )
    (comp (ref "U$584")
      (value "ONE_PAD")
      (footprint "eagle-import:1X01")
      (libsource (lib "eagle-import") (part "ONE_PAD"))
    )
    (comp (ref "U$585")
      (value "ONE_PAD")
      (footprint "eagle-import:1X01")
      (libsource (lib "eagle-import") (part "ONE_PAD"))
    )
    (comp (ref "U$586")
      (value "ONE_PAD")
      (footprint "eagle-import:1X01")
      (libsource (lib "eagle-import") (part "ONE_PAD"))
    )
    (comp (ref "U$587")
      (value "ONE_PAD")
      (footprint "eagle-import:1X01")
      (libsource (lib "eagle-import") (part "ONE_PAD"))
    )
    (comp (ref "U$588")
      (value "ONE_PAD")
      (footprint "eagle-import:1X01")
      (libsource (lib "eagle-import") (part "ONE_PAD"))
    )
    (comp (ref "U$589")
      (value "ONE_PAD")
      (footprint "eagle-import:1X01")
      (libsource (lib "eagle-import") (part "ONE_PAD"))
    )
    (comp (ref "U$590")
      (value "ONE_PAD")
      (footprint "eagle-import:1X01")
      (libsource (lib "eagle-import") (part "ONE_PAD"))
    )
    (comp (ref "U$591")
      (value "ONE_PAD")
      (footprint "eagle-import:1X01")
      (libsource (lib "eagle-import") (part "ONE_PAD"))
    )
    (comp (ref "U$592")
      (value "ONE_PAD")
      (footprint "eagle-import:1X01")
      (libsource (lib "eagle-import") (part "ONE_PAD"))
    )
    (comp (ref "U$593")
      (value "ONE_PAD")
      (footprint "eagle-import:1X01")
      (libsource (lib "eagle-import") (part "ONE_PAD"))
    )
    (comp (ref "U$594")
      (value "ONE_PAD")
      (footprint "eagle-import:1X01")
      (libsource (lib "eagle-import") (part "ONE_PAD"))
    )
    (comp (ref "U$595")
      (value "ONE_PAD")
      (footprint "eagle-import:1X01")
      (libsource (lib "eagle-import") (part "ONE_PAD"))
    )
    (comp (ref "U$596")
      (value "ONE_PAD")
      (footprint "eagle-import:1X01")
      (libsource (lib "eagle-import") (part "ONE_PAD"))
    )
    (comp (ref "U$597")
      (value "ONE_PAD")
      (footprint "eagle-import:1X01")
      (libsource (lib "eagle-import") (part "ONE_PAD"))
    )
    (comp (ref "U$598")
      (value "ONE_PAD")
      (footprint "eagle-import:1X01")
      (libsource (lib "eagle-import") (part "ONE_PAD"))
    )
    (comp (ref "U$599")
      (value "ONE_PAD")
      (footprint "eagle-import:1X01")
      (libsource (lib "eagle-import") (part "ONE_PAD"))
    )
    (comp (ref "U$600")
      (value "ONE_PAD")
      (footprint "eagle-import:1X01")
      (libsource (lib "eagle-import") (part "ONE_PAD"))
    )
    (comp (ref "U$601")
      (value "ONE_PAD")
      (footprint "eagle-import:1X01")
      (libsource (lib "eagle-import") (part "ONE_PAD"))
    )
    (comp (ref "U$602")
      (value "ONE_PAD")
      (footprint "eagle-import:1X01")
      (libsource (lib "eagle-import") (part "ONE_PAD"))
    )
    (comp (ref "U$603")
      (value "ONE_PAD")
      (footprint "eagle-import:1X01")
      (libsource (lib "eagle-import") (part "ONE_PAD"))
    )
    (comp (ref "U$604")
      (value "ONE_PAD")
      (footprint "eagle-import:1X01")
      (libsource (lib "eagle-import") (part "ONE_PAD"))
    )
    (comp (ref "U$605")
      (value "ONE_PAD")
      (footprint "eagle-import:1X01")
      (libsource (lib "eagle-import") (part "ONE_PAD"))
    )
    (comp (ref "U$606")
      (value "ONE_PAD")
      (footprint "eagle-import:1X01")
      (libsource (lib "eagle-import") (part "ONE_PAD"))
    )
    (comp (ref "U$607")
      (value "ONE_PAD")
      (footprint "eagle-import:1X01")
      (libsource (lib "eagle-import") (part "ONE_PAD"))
    )
    (comp (ref "U$608")
      (value "ONE_PAD")
      (footprint "eagle-import:1X01")
      (libsource (lib "eagle-import") (part "ONE_PAD"))
    )
    (comp (ref "U$609")
      (value "ONE_PAD")
      (footprint "eagle-import:1X01")
      (libsource (lib "eagle-import") (part "ONE_PAD"))
    )
    (comp (ref "U$610")
      (value "ONE_PAD")
      (footprint "eagle-import:1X01")
      (libsource (lib "eagle-import") (part "ONE_PAD"))
    )
    (comp (ref "U$611")
      (value "ONE_PAD")
      (footprint "eagle-import:1X01")
      (libsource (lib "eagle-import") (part "ONE_PAD"))
    )
    (comp (ref "U$612")
      (value "ONE_PAD")
      (footprint "eagle-import:1X01")
      (libsource (lib "eagle-import") (part "ONE_PAD"))
    )
    (comp (ref "U$613")
      (value "ONE_PAD")
      (footprint "eagle-import:1X01")
      (libsource (lib "eagle-import") (part "ONE_PAD"))
    )
    (comp (ref "U$614")
      (value "ONE_PAD")
      (footprint "eagle-import:1X01")
      (libsource (lib "eagle-import") (part "ONE_PAD"))
    )
    (comp (ref "U$615")
      (value "ONE_PAD")
      (footprint "eagle-import:1X01")
      (libsource (lib "eagle-import") (part "ONE_PAD"))
    )
    (comp (ref "U$616")
      (value "ONE_PAD")
      (footprint "eagle-import:1X01")
      (libsource (lib "eagle-import") (part "ONE_PAD"))
    )
    (comp (ref "U$617")
      (value "ONE_PAD")
      (footprint "eagle-import:1X01")
      (libsource (lib "eagle-import") (part "ONE_PAD"))
    )
    (comp (ref "U$618")
      (value "ONE_PAD")
      (footprint "eagle-import:1X01")
      (libsource (lib "eagle-import") (part "ONE_PAD"))
    )
    (comp (ref "U$619")
      (value "ONE_PAD")
      (footprint "eagle-import:1X01")
      (libsource (lib "eagle-import") (part "ONE_PAD"))
    )
    (comp (ref "U$620")
      (value "ONE_PAD")
      (footprint "eagle-import:1X01")
      (libsource (lib "eagle-import") (part "ONE_PAD"))
    )
    (comp (ref "U$621")
      (value "ONE_PAD")
      (footprint "eagle-import:1X01")
      (libsource (lib "eagle-import") (part "ONE_PAD"))
    )
    (comp (ref "U$622")
      (value "ONE_PAD")
      (footprint "eagle-import:1X01")
      (libsource (lib "eagle-import") (part "ONE_PAD"))
    )
    (comp (ref "U$623")
      (value "ONE_PAD")
      (footprint "eagle-import:1X01")
      (libsource (lib "eagle-import") (part "ONE_PAD"))
    )
    (comp (ref "U$624")
      (value "ONE_PAD")
      (footprint "eagle-import:1X01")
      (libsource (lib "eagle-import") (part "ONE_PAD"))
    )
    (comp (ref "U$625")
      (value "ONE_PAD")
      (footprint "eagle-import:1X01")
      (libsource (lib "eagle-import") (part "ONE_PAD"))
    )
    (comp (ref "U$626")
      (value "ONE_PAD")
      (footprint "eagle-import:1X01")
      (libsource (lib "eagle-import") (part "ONE_PAD"))
    )
    (comp (ref "U$627")
      (value "ONE_PAD")
      (footprint "eagle-import:1X01")
      (libsource (lib "eagle-import") (part "ONE_PAD"))
    )
    (comp (ref "U$628")
      (value "ONE_PAD")
      (footprint "eagle-import:1X01")
      (libsource (lib "eagle-import") (part "ONE_PAD"))
    )
    (comp (ref "U$629")
      (value "ONE_PAD")
      (footprint "eagle-import:1X01")
      (libsource (lib "eagle-import") (part "ONE_PAD"))
    )
    (comp (ref "U$630")
      (value "ONE_PAD")
      (footprint "eagle-import:1X01")
      (libsource (lib "eagle-import") (part "ONE_PAD"))
    )
    (comp (ref "U$631")
      (value "ONE_PAD")
      (footprint "eagle-import:1X01")
      (libsource (lib "eagle-import") (part "ONE_PAD"))
    )
    (comp (ref "U$632")
      (value "ONE_PAD")
      (footprint "eagle-import:1X01")
      (libsource (lib "eagle-import") (part "ONE_PAD"))
    )
    (comp (ref "U$633")
      (value "ONE_PAD")
      (footprint "eagle-import:1X01")
      (libsource (lib "eagle-import") (part "ONE_PAD"))
    )
    (comp (ref "U$634")
      (value "ONE_PAD")
      (footprint "eagle-import:1X01")
      (libsource (lib "eagle-import") (part "ONE_PAD"))
    )
    (comp (ref "U$635")
      (value "ONE_PAD")
      (footprint "eagle-import:1X01")
      (libsource (lib "eagle-import") (part "ONE_PAD"))
    )
    (comp (ref "U$636")
      (value "ONE_PAD")
      (footprint "eagle-import:1X01")
      (libsource (lib "eagle-import") (part "ONE_PAD"))
    )
    (comp (ref "U$637")
      (value "ONE_PAD")
      (footprint "eagle-import:1X01")
      (libsource (lib "eagle-import") (part "ONE_PAD"))
    )
    (comp (ref "U$638")
      (value "ONE_PAD")
      (footprint "eagle-import:1X01")
      (libsource (lib "eagle-import") (part "ONE_PAD"))
    )
    (comp (ref "U$639")
      (value "ONE_PAD")
      (footprint "eagle-import:1X01")
      (libsource (lib "eagle-import") (part "ONE_PAD"))
    )
    (comp (ref "U$640")
      (value "ONE_PAD")
      (footprint "eagle-import:1X01")
      (libsource (lib "eagle-import") (part "ONE_PAD"))
    )
    (comp (ref "U$641")
      (value "ONE_PAD")
      (footprint "eagle-import:1X01")
      (libsource (lib "eagle-import") (part "ONE_PAD"))
    )
    (comp (ref "U$642")
      (value "ONE_PAD")
      (footprint "eagle-import:1X01")
      (libsource (lib "eagle-import") (part "ONE_PAD"))
    )
    (comp (ref "U$643")
      (value "GND")
      (footprint "eagle-import:1X01")
      (libsource (lib "eagle-import") (part "ONE_PAD"))
    )
    (comp (ref "U$644")
      (value "VCC")
      (footprint "eagle-import:1X01")
      (libsource (lib "eagle-import") (part "ONE_PAD"))
    )
    (comp (ref "U$645")
      (value "SDA")
      (footprint "eagle-import:1X01")
      (libsource (lib "eagle-import") (part "ONE_PAD"))
    )
    (comp (ref "U$646")
      (value "SCL")
      (footprint "eagle-import:1X01")
      (libsource (lib "eagle-import") (part "ONE_PAD"))
    )
    (comp (ref "U$647")
      (value "ONE_PAD")
      (footprint "eagle-import:1X01")
      (libsource (lib "eagle-import") (part "ONE_PAD"))
    )
    (comp (ref "U$648")
      (value "ONE_PAD")
      (footprint "eagle-import:1X01")
      (libsource (lib "eagle-import") (part "ONE_PAD"))
    )
    (comp (ref "U$649")
      (value "ONE_PAD")
      (footprint "eagle-import:1X01")
      (libsource (lib "eagle-import") (part "ONE_PAD"))
    )
    (comp (ref "U$650")
      (value "ONE_PAD")
      (footprint "eagle-import:1X01")
      (libsource (lib "eagle-import") (part "ONE_PAD"))
    )
    (comp (ref "U$651")
      (value "ONE_PAD")
      (footprint "eagle-import:1X01")
      (libsource (lib "eagle-import") (part "ONE_PAD"))
    )
    (comp (ref "U$652")
      (value "ONE_PAD")
      (footprint "eagle-import:1X01")
      (libsource (lib "eagle-import") (part "ONE_PAD"))
    )
    (comp (ref "U$653")
      (value "ONE_PAD")
      (footprint "eagle-import:1X01")
      (libsource (lib "eagle-import") (part "ONE_PAD"))
    )
    (comp (ref "U$654")
      (value "ONE_PAD")
      (footprint "eagle-import:1X01")
      (libsource (lib "eagle-import") (part "ONE_PAD"))
    )
    (comp (ref "U$655")
      (value "ONE_PAD")
      (footprint "eagle-import:1X01")
      (libsource (lib "eagle-import") (part "ONE_PAD"))
    )
    (comp (ref "U$656")
      (value "ONE_PAD")
      (footprint "eagle-import:1X01")
      (libsource (lib "eagle-import") (part "ONE_PAD"))
    )
    (comp (ref "U$657")
      (value "ONE_PAD")
      (footprint "eagle-import:1X01")
      (libsource (lib "eagle-import") (part "ONE_PAD"))
    )
    (comp (ref "U$658")
      (value "ONE_PAD")
      (footprint "eagle-import:1X01")
      (libsource (lib "eagle-import") (part "ONE_PAD"))
    )
    (comp (ref "U$659")
      (value "ONE_PAD")
      (footprint "eagle-import:1X01")
      (libsource (lib "eagle-import") (part "ONE_PAD"))
    )
    (comp (ref "U$660")
      (value "ONE_PAD")
      (footprint "eagle-import:1X01")
      (libsource (lib "eagle-import") (part "ONE_PAD"))
    )
    (comp (ref "U$661")
      (value "ONE_PAD")
      (footprint "eagle-import:1X01")
      (libsource (lib "eagle-import") (part "ONE_PAD"))
    )
    (comp (ref "U$662")
      (value "ONE_PAD")
      (footprint "eagle-import:1X01")
      (libsource (lib "eagle-import") (part "ONE_PAD"))
    )
    (comp (ref "U$663")
      (value "ONE_PAD")
      (footprint "eagle-import:1X01")
      (libsource (lib "eagle-import") (part "ONE_PAD"))
    )
    (comp (ref "U$664")
      (value "ONE_PAD")
      (footprint "eagle-import:1X01")
      (libsource (lib "eagle-import") (part "ONE_PAD"))
    )
    (comp (ref "U$665")
      (value "ONE_PAD")
      (footprint "eagle-import:1X01")
      (libsource (lib "eagle-import") (part "ONE_PAD"))
    )
    (comp (ref "U$666")
      (value "ONE_PAD")
      (footprint "eagle-import:1X01")
      (libsource (lib "eagle-import") (part "ONE_PAD"))
    )
    (comp (ref "U$667")
      (value "ONE_PAD")
      (footprint "eagle-import:1X01")
      (libsource (lib "eagle-import") (part "ONE_PAD"))
    )
    (comp (ref "U$668")
      (value "ONE_PAD")
      (footprint "eagle-import:1X01")
      (libsource (lib "eagle-import") (part "ONE_PAD"))
    )
    (comp (ref "U$669")
      (value "ONE_PAD")
      (footprint "eagle-import:1X01")
      (libsource (lib "eagle-import") (part "ONE_PAD"))
    )
    (comp (ref "U$670")
      (value "ONE_PAD")
      (footprint "eagle-import:1X01")
      (libsource (lib "eagle-import") (part "ONE_PAD"))
    )
    (comp (ref "U$671")
      (value "ONE_PAD")
      (footprint "eagle-import:1X01")
      (libsource (lib "eagle-import") (part "ONE_PAD"))
    )
    (comp (ref "U$672")
      (value "ONE_PAD")
      (footprint "eagle-import:1X01")
      (libsource (lib "eagle-import") (part "ONE_PAD"))
    )
    (comp (ref "U$673")
      (value "ONE_PAD")
      (footprint "eagle-import:1X01")
      (libsource (lib "eagle-import") (part "ONE_PAD"))
    )
    (comp (ref "U$674")
      (value "ONE_PAD")
      (footprint "eagle-import:1X01")
      (libsource (lib "eagle-import") (part "ONE_PAD"))
    )
    (comp (ref "U$675")
      (value "ONE_PAD")
      (footprint "eagle-import:1X01")
      (libsource (lib "eagle-import") (part "ONE_PAD"))
    )
    (comp (ref "U$676")
      (value "ONE_PAD")
      (footprint "eagle-import:1X01")
      (libsource (lib "eagle-import") (part "ONE_PAD"))
    )
    (comp (ref "U$677")
      (value "ONE_PAD")
      (footprint "eagle-import:1X01")
      (libsource (lib "eagle-import") (part "ONE_PAD"))
    )
    (comp (ref "U$678")
      (value "ONE_PAD")
      (footprint "eagle-import:1X01")
      (libsource (lib "eagle-import") (part "ONE_PAD"))
    )
    (comp (ref "U$679")
      (value "ONE_PAD")
      (footprint "eagle-import:1X01")
      (libsource (lib "eagle-import") (part "ONE_PAD"))
    )
    (comp (ref "U$680")
      (value "ONE_PAD")
      (footprint "eagle-import:1X01")
      (libsource (lib "eagle-import") (part "ONE_PAD"))
    )
    (comp (ref "U$681")
      (value "ONE_PAD")
      (footprint "eagle-import:1X01")
      (libsource (lib "eagle-import") (part "ONE_PAD"))
    )
    (comp (ref "U$682")
      (value "ONE_PAD")
      (footprint "eagle-import:1X01")
      (libsource (lib "eagle-import") (part "ONE_PAD"))
    )
    (comp (ref "U$683")
      (value "ONE_PAD")
      (footprint "eagle-import:1X01")
      (libsource (lib "eagle-import") (part "ONE_PAD"))
    )
    (comp (ref "U$684")
      (value "ONE_PAD")
      (footprint "eagle-import:1X01")
      (libsource (lib "eagle-import") (part "ONE_PAD"))
    )
    (comp (ref "U$685")
      (value "ONE_PAD")
      (footprint "eagle-import:1X01")
      (libsource (lib "eagle-import") (part "ONE_PAD"))
    )
    (comp (ref "U$686")
      (value "ONE_PAD")
      (footprint "eagle-import:1X01")
      (libsource (lib "eagle-import") (part "ONE_PAD"))
    )
    (comp (ref "U$687")
      (value "ONE_PAD")
      (footprint "eagle-import:1X01")
      (libsource (lib "eagle-import") (part "ONE_PAD"))
    )
    (comp (ref "U$688")
      (value "ONE_PAD")
      (footprint "eagle-import:1X01")
      (libsource (lib "eagle-import") (part "ONE_PAD"))
    )
    (comp (ref "U$689")
      (value "ONE_PAD")
      (footprint "eagle-import:1X01")
      (libsource (lib "eagle-import") (part "ONE_PAD"))
    )
    (comp (ref "U$690")
      (value "ONE_PAD")
      (footprint "eagle-import:1X01")
      (libsource (lib "eagle-import") (part "ONE_PAD"))
    )
    (comp (ref "U$691")
      (value "ONE_PAD")
      (footprint "eagle-import:1X01")
      (libsource (lib "eagle-import") (part "ONE_PAD"))
    )
    (comp (ref "U$692")
      (value "ONE_PAD")
      (footprint "eagle-import:1X01")
      (libsource (lib "eagle-import") (part "ONE_PAD"))
    )
    (comp (ref "U$693")
      (value "DECOUPLING_CAP")
      (footprint "eagle-import:DECOUPLING_CAP")
      (libsource (lib "eagle-import") (part "DECOUPLING_CAP"))
    )
    (comp (ref "U$694")
      (value "RESISTOR")
      (footprint "eagle-import:AXIAL-0.3")
      (libsource (lib "eagle-import") (part "RESISTOR"))
    )
    (comp (ref "U$695")
      (value "RESISTOR")
      (footprint "eagle-import:AXIAL-0.3")
      (libsource (lib "eagle-import") (part "RESISTOR"))
    )
    (comp (ref "U$696")
      (value "ONE_PAD")
      (footprint "eagle-import:1X01")
      (libsource (lib "eagle-import") (part "ONE_PAD"))
    )
    (comp (ref "U$697")
      (value "ONE_PAD")
      (footprint "eagle-import:1X01")
      (libsource (lib "eagle-import") (part "ONE_PAD"))
    )
    (comp (ref "U$698")
      (value "ONE_PAD")
      (footprint "eagle-import:1X01")
      (libsource (lib "eagle-import") (part "ONE_PAD"))
    )
    (comp (ref "U$699")
      (value "ONE_PAD")
      (footprint "eagle-import:1X01")
      (libsource (lib "eagle-import") (part "ONE_PAD"))
    )
    (comp (ref "U$700")
      (value "ONE_PAD")
      (footprint "eagle-import:1X01")
      (libsource (lib "eagle-import") (part "ONE_PAD"))
    )
    (comp (ref "U$701")
      (value "ONE_PAD")
      (footprint "eagle-import:1X01")
      (libsource (lib "eagle-import") (part "ONE_PAD"))
    )
    (comp (ref "U$702")
      (value "ONE_PAD")
      (footprint "eagle-import:1X01")
      (libsource (lib "eagle-import") (part "ONE_PAD"))
    )
    (comp (ref "U$703")
      (value "ONE_PAD")
      (footprint "eagle-import:1X01")
      (libsource (lib "eagle-import") (part "ONE_PAD"))
    )
    (comp (ref "U$704")
      (value "ONE_PAD")
      (footprint "eagle-import:1X01")
      (libsource (lib "eagle-import") (part "ONE_PAD"))
    )
    (comp (ref "U$705")
      (value "ONE_PAD")
      (footprint "eagle-import:1X01")
      (libsource (lib "eagle-import") (part "ONE_PAD"))
    )
    (comp (ref "U$706")
      (value "ONE_PAD")
      (footprint "eagle-import:1X01")
      (libsource (lib "eagle-import") (part "ONE_PAD"))
    )
    (comp (ref "U$707")
      (value "ONE_PAD")
      (footprint "eagle-import:1X01")
      (libsource (lib "eagle-import") (part "ONE_PAD"))
    )
    (comp (ref "U$708")
      (value "ONE_PAD")
      (footprint "eagle-import:1X01")
      (libsource (lib "eagle-import") (part "ONE_PAD"))
    )
    (comp (ref "U$709")
      (value "ONE_PAD")
      (footprint "eagle-import:1X01")
      (libsource (lib "eagle-import") (part "ONE_PAD"))
    )
    (comp (ref "U$710")
      (value "ONE_PAD")
      (footprint "eagle-import:1X01")
      (libsource (lib "eagle-import") (part "ONE_PAD"))
    )
    (comp (ref "U$711")
      (value "ONE_PAD")
      (footprint "eagle-import:1X01")
      (libsource (lib "eagle-import") (part "ONE_PAD"))
    )
    (comp (ref "U$712")
      (value "ONE_PAD")
      (footprint "eagle-import:1X01")
      (libsource (lib "eagle-import") (part "ONE_PAD"))
    )
    (comp (ref "U$713")
      (value "ONE_PAD")
      (footprint "eagle-import:1X01")
      (libsource (lib "eagle-import") (part "ONE_PAD"))
    )
    (comp (ref "U$714")
      (value "ONE_PAD")
      (footprint "eagle-import:1X01")
      (libsource (lib "eagle-import") (part "ONE_PAD"))
    )
    (comp (ref "U$715")
      (value "ONE_PAD")
      (footprint "eagle-import:1X01")
      (libsource (lib "eagle-import") (part "ONE_PAD"))
    )
    (comp (ref "U$716")
      (value "ONE_PAD")
      (footprint "eagle-import:1X01")
      (libsource (lib "eagle-import") (part "ONE_PAD"))
    )
    (comp (ref "U$717")
      (value "ONE_PAD")
      (footprint "eagle-import:1X01")
      (libsource (lib "eagle-import") (part "ONE_PAD"))
    )
    (comp (ref "U$718")
      (value "ONE_PAD")
      (footprint "eagle-import:1X01")
      (libsource (lib "eagle-import") (part "ONE_PAD"))
    )
    (comp (ref "U$719")
      (value "ONE_PAD")
      (footprint "eagle-import:1X01")
      (libsource (lib "eagle-import") (part "ONE_PAD"))
    )
    (comp (ref "U$720")
      (value "ONE_PAD")
      (footprint "eagle-import:1X01")
      (libsource (lib "eagle-import") (part "ONE_PAD"))
    )
    (comp (ref "U$721")
      (value "ONE_PAD")
      (footprint "eagle-import:1X01")
      (libsource (lib "eagle-import") (part "ONE_PAD"))
    )
    (comp (ref "U$722")
      (value "ONE_PAD")
      (footprint "eagle-import:1X01")
      (libsource (lib "eagle-import") (part "ONE_PAD"))
    )
    (comp (ref "U$723")
      (value "ONE_PAD")
      (footprint "eagle-import:1X01")
      (libsource (lib "eagle-import") (part "ONE_PAD"))
    )
    (comp (ref "U$724")
      (value "ONE_PAD")
      (footprint "eagle-import:1X01")
      (libsource (lib "eagle-import") (part "ONE_PAD"))
    )
    (comp (ref "U$725")
      (value "ONE_PAD")
      (footprint "eagle-import:1X01")
      (libsource (lib "eagle-import") (part "ONE_PAD"))
    )
    (comp (ref "U$726")
      (value "ONE_PAD")
      (footprint "eagle-import:1X01")
      (libsource (lib "eagle-import") (part "ONE_PAD"))
    )
    (comp (ref "U$727")
      (value "ONE_PAD")
      (footprint "eagle-import:1X01")
      (libsource (lib "eagle-import") (part "ONE_PAD"))
    )
    (comp (ref "U$728")
      (value "ONE_PAD")
      (footprint "eagle-import:1X01")
      (libsource (lib "eagle-import") (part "ONE_PAD"))
    )
    (comp (ref "U$729")
      (value "ONE_PAD")
      (footprint "eagle-import:1X01")
      (libsource (lib "eagle-import") (part "ONE_PAD"))
    )
    (comp (ref "U$730")
      (value "ONE_PAD")
      (footprint "eagle-import:1X01")
      (libsource (lib "eagle-import") (part "ONE_PAD"))
    )
    (comp (ref "U$731")
      (value "ONE_PAD")
      (footprint "eagle-import:1X01")
      (libsource (lib "eagle-import") (part "ONE_PAD"))
    )
    (comp (ref "U$732")
      (value "ONE_PAD")
      (footprint "eagle-import:1X01")
      (libsource (lib "eagle-import") (part "ONE_PAD"))
    )
    (comp (ref "U$733")
      (value "ONE_PAD")
      (footprint "eagle-import:1X01")
      (libsource (lib "eagle-import") (part "ONE_PAD"))
    )
    (comp (ref "U$734")
      (value "ONE_PAD")
      (footprint "eagle-import:1X01")
      (libsource (lib "eagle-import") (part "ONE_PAD"))
    )
    (comp (ref "U$735")
      (value "ONE_PAD")
      (footprint "eagle-import:1X01")
      (libsource (lib "eagle-import") (part "ONE_PAD"))
    )
    (comp (ref "U$736")
      (value "ONE_PAD")
      (footprint "eagle-import:1X01")
      (libsource (lib "eagle-import") (part "ONE_PAD"))
    )
    (comp (ref "U$737")
      (value "ONE_PAD")
      (footprint "eagle-import:1X01")
      (libsource (lib "eagle-import") (part "ONE_PAD"))
    )
    (comp (ref "U$738")
      (value "ONE_PAD")
      (footprint "eagle-import:1X01")
      (libsource (lib "eagle-import") (part "ONE_PAD"))
    )
    (comp (ref "U$739")
      (value "ONE_PAD")
      (footprint "eagle-import:1X01")
      (libsource (lib "eagle-import") (part "ONE_PAD"))
    )
    (comp (ref "U$740")
      (value "ONE_PAD")
      (footprint "eagle-import:1X01")
      (libsource (lib "eagle-import") (part "ONE_PAD"))
    )
    (comp (ref "U$741")
      (value "ONE_PAD")
      (footprint "eagle-import:1X01")
      (libsource (lib "eagle-import") (part "ONE_PAD"))
    )
    (comp (ref "U$742")
      (value "ONE_PAD")
      (footprint "eagle-import:1X01")
      (libsource (lib "eagle-import") (part "ONE_PAD"))
    )
    (comp (ref "U$743")
      (value "ONE_PAD")
      (footprint "eagle-import:1X01")
      (libsource (lib "eagle-import") (part "ONE_PAD"))
    )
    (comp (ref "U$744")
      (value "ONE_PAD")
      (footprint "eagle-import:1X01")
      (libsource (lib "eagle-import") (part "ONE_PAD"))
    )
    (comp (ref "U$745")
      (value "ONE_PAD")
      (footprint "eagle-import:1X01")
      (libsource (lib "eagle-import") (part "ONE_PAD"))
    )
    (comp (ref "U$746")
      (value "ONE_PAD")
      (footprint "eagle-import:1X01")
      (libsource (lib "eagle-import") (part "ONE_PAD"))
    )
    (comp (ref "U$747")
      (value "ONE_PAD")
      (footprint "eagle-import:1X01")
      (libsource (lib "eagle-import") (part "ONE_PAD"))
    )
    (comp (ref "U$748")
      (value "ONE_PAD")
      (footprint "eagle-import:1X01")
      (libsource (lib "eagle-import") (part "ONE_PAD"))
    )
    (comp (ref "U$749")
      (value "ONE_PAD")
      (footprint "eagle-import:1X01")
      (libsource (lib "eagle-import") (part "ONE_PAD"))
    )
    (comp (ref "U$750")
      (value "ONE_PAD")
      (footprint "eagle-import:1X01")
      (libsource (lib "eagle-import") (part "ONE_PAD"))
    )
    (comp (ref "U$751")
      (value "ONE_PAD")
      (footprint "eagle-import:1X01")
      (libsource (lib "eagle-import") (part "ONE_PAD"))
    )
    (comp (ref "U$752")
      (value "ONE_PAD")
      (footprint "eagle-import:1X01")
      (libsource (lib "eagle-import") (part "ONE_PAD"))
    )
    (comp (ref "U$753")
      (value "ONE_PAD")
      (footprint "eagle-import:1X01")
      (libsource (lib "eagle-import") (part "ONE_PAD"))
    )
    (comp (ref "U$754")
      (value "ONE_PAD")
      (footprint "eagle-import:1X01")
      (libsource (lib "eagle-import") (part "ONE_PAD"))
    )
    (comp (ref "U$755")
      (value "ONE_PAD")
      (footprint "eagle-import:1X01")
      (libsource (lib "eagle-import") (part "ONE_PAD"))
    )
    (comp (ref "U$756")
      (value "ONE_PAD")
      (footprint "eagle-import:1X01")
      (libsource (lib "eagle-import") (part "ONE_PAD"))
    )
    (comp (ref "U$757")
      (value "ONE_PAD")
      (footprint "eagle-import:1X01")
      (libsource (lib "eagle-import") (part "ONE_PAD"))
    )
    (comp (ref "U$758")
      (value "ONE_PAD")
      (footprint "eagle-import:1X01")
      (libsource (lib "eagle-import") (part "ONE_PAD"))
    )
    (comp (ref "U$759")
      (value "ONE_PAD")
      (footprint "eagle-import:1X01")
      (libsource (lib "eagle-import") (part "ONE_PAD"))
    )
    (comp (ref "U$760")
      (value "ONE_PAD")
      (footprint "eagle-import:1X01")
      (libsource (lib "eagle-import") (part "ONE_PAD"))
    )
    (comp (ref "U$761")
      (value "ONE_PAD")
      (footprint "eagle-import:1X01")
      (libsource (lib "eagle-import") (part "ONE_PAD"))
    )
    (comp (ref "U$762")
      (value "ONE_PAD")
      (footprint "eagle-import:1X01")
      (libsource (lib "eagle-import") (part "ONE_PAD"))
    )
    (comp (ref "U$763")
      (value "ONE_PAD")
      (footprint "eagle-import:1X01")
      (libsource (lib "eagle-import") (part "ONE_PAD"))
    )
    (comp (ref "U$764")
      (value "ONE_PAD")
      (footprint "eagle-import:1X01")
      (libsource (lib "eagle-import") (part "ONE_PAD"))
    )
    (comp (ref "U$765")
      (value "ONE_PAD")
      (footprint "eagle-import:1X01")
      (libsource (lib "eagle-import") (part "ONE_PAD"))
    )
    (comp (ref "U$766")
      (value "ONE_PAD")
      (footprint "eagle-import:1X01")
      (libsource (lib "eagle-import") (part "ONE_PAD"))
    )
    (comp (ref "U$767")
      (value "ONE_PAD")
      (footprint "eagle-import:1X01")
      (libsource (lib "eagle-import") (part "ONE_PAD"))
    )
    (comp (ref "U$768")
      (value "ONE_PAD")
      (footprint "eagle-import:1X01")
      (libsource (lib "eagle-import") (part "ONE_PAD"))
    )
    (comp (ref "U$769")
      (value "ONE_PAD")
      (footprint "eagle-import:1X01")
      (libsource (lib "eagle-import") (part "ONE_PAD"))
    )
    (comp (ref "U$770")
      (value "ONE_PAD")
      (footprint "eagle-import:1X01")
      (libsource (lib "eagle-import") (part "ONE_PAD"))
    )
    (comp (ref "U$771")
      (value "ONE_PAD")
      (footprint "eagle-import:1X01")
      (libsource (lib "eagle-import") (part "ONE_PAD"))
    )
    (comp (ref "U$772")
      (value "ONE_PAD")
      (footprint "eagle-import:1X01")
      (libsource (lib "eagle-import") (part "ONE_PAD"))
    )
    (comp (ref "U$773")
      (value "ONE_PAD")
      (footprint "eagle-import:1X01")
      (libsource (lib "eagle-import") (part "ONE_PAD"))
    )
    (comp (ref "U$774")
      (value "ONE_PAD")
      (footprint "eagle-import:1X01")
      (libsource (lib "eagle-import") (part "ONE_PAD"))
    )
    (comp (ref "U$775")
      (value "ONE_PAD")
      (footprint "eagle-import:1X01")
      (libsource (lib "eagle-import") (part "ONE_PAD"))
    )
    (comp (ref "U$776")
      (value "ONE_PAD")
      (footprint "eagle-import:1X01")
      (libsource (lib "eagle-import") (part "ONE_PAD"))
    )
    (comp (ref "U$777")
      (value "ONE_PAD")
      (footprint "eagle-import:1X01")
      (libsource (lib "eagle-import") (part "ONE_PAD"))
    )
    (comp (ref "U$778")
      (value "ONE_PAD")
      (footprint "eagle-import:1X01")
      (libsource (lib "eagle-import") (part "ONE_PAD"))
    )
    (comp (ref "U$779")
      (value "ONE_PAD")
      (footprint "eagle-import:1X01")
      (libsource (lib "eagle-import") (part "ONE_PAD"))
    )
    (comp (ref "U$780")
      (value "ONE_PAD")
      (footprint "eagle-import:1X01")
      (libsource (lib "eagle-import") (part "ONE_PAD"))
    )
    (comp (ref "U$781")
      (value "ONE_PAD")
      (footprint "eagle-import:1X01")
      (libsource (lib "eagle-import") (part "ONE_PAD"))
    )
    (comp (ref "U$782")
      (value "ONE_PAD")
      (footprint "eagle-import:1X01")
      (libsource (lib "eagle-import") (part "ONE_PAD"))
    )
    (comp (ref "U$783")
      (value "ONE_PAD")
      (footprint "eagle-import:1X01")
      (libsource (lib "eagle-import") (part "ONE_PAD"))
    )
    (comp (ref "U$784")
      (value "ONE_PAD")
      (footprint "eagle-import:1X01")
      (libsource (lib "eagle-import") (part "ONE_PAD"))
    )
    (comp (ref "U$785")
      (value "ONE_PAD")
      (footprint "eagle-import:1X01")
      (libsource (lib "eagle-import") (part "ONE_PAD"))
    )
    (comp (ref "U$786")
      (value "GND")
      (footprint "eagle-import:1X01")
      (libsource (lib "eagle-import") (part "ONE_PAD"))
    )
    (comp (ref "U$787")
      (value "VCC")
      (footprint "eagle-import:1X01")
      (libsource (lib "eagle-import") (part "ONE_PAD"))
    )
    (comp (ref "U$788")
      (value "SDA")
      (footprint "eagle-import:1X01")
      (libsource (lib "eagle-import") (part "ONE_PAD"))
    )
    (comp (ref "U$789")
      (value "SCL")
      (footprint "eagle-import:1X01")
      (libsource (lib "eagle-import") (part "ONE_PAD"))
    )
    (comp (ref "U$790")
      (value "ONE_PAD")
      (footprint "eagle-import:1X01")
      (libsource (lib "eagle-import") (part "ONE_PAD"))
    )
    (comp (ref "U$791")
      (value "ONE_PAD")
      (footprint "eagle-import:1X01")
      (libsource (lib "eagle-import") (part "ONE_PAD"))
    )
    (comp (ref "U$792")
      (value "ONE_PAD")
      (footprint "eagle-import:1X01")
      (libsource (lib "eagle-import") (part "ONE_PAD"))
    )
    (comp (ref "U$793")
      (value "ONE_PAD")
      (footprint "eagle-import:1X01")
      (libsource (lib "eagle-import") (part "ONE_PAD"))
    )
    (comp (ref "U$794")
      (value "ONE_PAD")
      (footprint "eagle-import:1X01")
      (libsource (lib "eagle-import") (part "ONE_PAD"))
    )
    (comp (ref "U$795")
      (value "ONE_PAD")
      (footprint "eagle-import:1X01")
      (libsource (lib "eagle-import") (part "ONE_PAD"))
    )
    (comp (ref "U$796")
      (value "ONE_PAD")
      (footprint "eagle-import:1X01")
      (libsource (lib "eagle-import") (part "ONE_PAD"))
    )
    (comp (ref "U$797")
      (value "ONE_PAD")
      (footprint "eagle-import:1X01")
      (libsource (lib "eagle-import") (part "ONE_PAD"))
    )
    (comp (ref "U$798")
      (value "ONE_PAD")
      (footprint "eagle-import:1X01")
      (libsource (lib "eagle-import") (part "ONE_PAD"))
    )
    (comp (ref "U$799")
      (value "ONE_PAD")
      (footprint "eagle-import:1X01")
      (libsource (lib "eagle-import") (part "ONE_PAD"))
    )
    (comp (ref "U$800")
      (value "ONE_PAD")
      (footprint "eagle-import:1X01")
      (libsource (lib "eagle-import") (part "ONE_PAD"))
    )
    (comp (ref "U$801")
      (value "ONE_PAD")
      (footprint "eagle-import:1X01")
      (libsource (lib "eagle-import") (part "ONE_PAD"))
    )
    (comp (ref "U$802")
      (value "ONE_PAD")
      (footprint "eagle-import:1X01")
      (libsource (lib "eagle-import") (part "ONE_PAD"))
    )
    (comp (ref "U$803")
      (value "ONE_PAD")
      (footprint "eagle-import:1X01")
      (libsource (lib "eagle-import") (part "ONE_PAD"))
    )
    (comp (ref "U$804")
      (value "ONE_PAD")
      (footprint "eagle-import:1X01")
      (libsource (lib "eagle-import") (part "ONE_PAD"))
    )
    (comp (ref "U$805")
      (value "ONE_PAD")
      (footprint "eagle-import:1X01")
      (libsource (lib "eagle-import") (part "ONE_PAD"))
    )
    (comp (ref "U$806")
      (value "ONE_PAD")
      (footprint "eagle-import:1X01")
      (libsource (lib "eagle-import") (part "ONE_PAD"))
    )
    (comp (ref "U$807")
      (value "ONE_PAD")
      (footprint "eagle-import:1X01")
      (libsource (lib "eagle-import") (part "ONE_PAD"))
    )
    (comp (ref "U$808")
      (value "ONE_PAD")
      (footprint "eagle-import:1X01")
      (libsource (lib "eagle-import") (part "ONE_PAD"))
    )
    (comp (ref "U$809")
      (value "ONE_PAD")
      (footprint "eagle-import:1X01")
      (libsource (lib "eagle-import") (part "ONE_PAD"))
    )
    (comp (ref "U$810")
      (value "ONE_PAD")
      (footprint "eagle-import:1X01")
      (libsource (lib "eagle-import") (part "ONE_PAD"))
    )
    (comp (ref "U$811")
      (value "ONE_PAD")
      (footprint "eagle-import:1X01")
      (libsource (lib "eagle-import") (part "ONE_PAD"))
    )
    (comp (ref "U$812")
      (value "ONE_PAD")
      (footprint "eagle-import:1X01")
      (libsource (lib "eagle-import") (part "ONE_PAD"))
    )
    (comp (ref "U$813")
      (value "ONE_PAD")
      (footprint "eagle-import:1X01")
      (libsource (lib "eagle-import") (part "ONE_PAD"))
    )
    (comp (ref "U$814")
      (value "ONE_PAD")
      (footprint "eagle-import:1X01")
      (libsource (lib "eagle-import") (part "ONE_PAD"))
    )
    (comp (ref "U$815")
      (value "ONE_PAD")
      (footprint "eagle-import:1X01")
      (libsource (lib "eagle-import") (part "ONE_PAD"))
    )
    (comp (ref "U$816")
      (value "ONE_PAD")
      (footprint "eagle-import:1X01")
      (libsource (lib "eagle-import") (part "ONE_PAD"))
    )
    (comp (ref "U$817")
      (value "ONE_PAD")
      (footprint "eagle-import:1X01")
      (libsource (lib "eagle-import") (part "ONE_PAD"))
    )
    (comp (ref "U$818")
      (value "ONE_PAD")
      (footprint "eagle-import:1X01")
      (libsource (lib "eagle-import") (part "ONE_PAD"))
    )
    (comp (ref "U$819")
      (value "ONE_PAD")
      (footprint "eagle-import:1X01")
      (libsource (lib "eagle-import") (part "ONE_PAD"))
    )
    (comp (ref "U$820")
      (value "ONE_PAD")
      (footprint "eagle-import:1X01")
      (libsource (lib "eagle-import") (part "ONE_PAD"))
    )
    (comp (ref "U$821")
      (value "ONE_PAD")
      (footprint "eagle-import:1X01")
      (libsource (lib "eagle-import") (part "ONE_PAD"))
    )
    (comp (ref "U$822")
      (value "ONE_PAD")
      (footprint "eagle-import:1X01")
      (libsource (lib "eagle-import") (part "ONE_PAD"))
    )
    (comp (ref "U$823")
      (value "ONE_PAD")
      (footprint "eagle-import:1X01")
      (libsource (lib "eagle-import") (part "ONE_PAD"))
    )
    (comp (ref "U$824")
      (value "ONE_PAD")
      (footprint "eagle-import:1X01")
      (libsource (lib "eagle-import") (part "ONE_PAD"))
    )
    (comp (ref "U$825")
      (value "ONE_PAD")
      (footprint "eagle-import:1X01")
      (libsource (lib "eagle-import") (part "ONE_PAD"))
    )
    (comp (ref "U$826")
      (value "ONE_PAD")
      (footprint "eagle-import:1X01")
      (libsource (lib "eagle-import") (part "ONE_PAD"))
    )
    (comp (ref "U$827")
      (value "ONE_PAD")
      (footprint "eagle-import:1X01")
      (libsource (lib "eagle-import") (part "ONE_PAD"))
    )
    (comp (ref "U$828")
      (value "ONE_PAD")
      (footprint "eagle-import:1X01")
      (libsource (lib "eagle-import") (part "ONE_PAD"))
    )
    (comp (ref "U$829")
      (value "ONE_PAD")
      (footprint "eagle-import:1X01")
      (libsource (lib "eagle-import") (part "ONE_PAD"))
    )
    (comp (ref "U$830")
      (value "ONE_PAD")
      (footprint "eagle-import:1X01")
      (libsource (lib "eagle-import") (part "ONE_PAD"))
    )
    (comp (ref "U$831")
      (value "ONE_PAD")
      (footprint "eagle-import:1X01")
      (libsource (lib "eagle-import") (part "ONE_PAD"))
    )
    (comp (ref "U$832")
      (value "ONE_PAD")
      (footprint "eagle-import:1X01")
      (libsource (lib "eagle-import") (part "ONE_PAD"))
    )
    (comp (ref "U$833")
      (value "ONE_PAD")
      (footprint "eagle-import:1X01")
      (libsource (lib "eagle-import") (part "ONE_PAD"))
    )
    (comp (ref "U$834")
      (value "ONE_PAD")
      (footprint "eagle-import:1X01")
      (libsource (lib "eagle-import") (part "ONE_PAD"))
    )
    (comp (ref "U$835")
      (value "ONE_PAD")
      (footprint "eagle-import:1X01")
      (libsource (lib "eagle-import") (part "ONE_PAD"))
    )
    (comp (ref "U$836")
      (value "DECOUPLING_CAP")
      (footprint "eagle-import:DECOUPLING_CAP")
      (libsource (lib "eagle-import") (part "DECOUPLING_CAP"))
    )
    (comp (ref "U$837")
      (value "RESISTOR")
      (footprint "eagle-import:AXIAL-0.3")
      (libsource (lib "eagle-import") (part "RESISTOR"))
    )
    (comp (ref "U$838")
      (value "RESISTOR")
      (footprint "eagle-import:AXIAL-0.3")
      (libsource (lib "eagle-import") (part "RESISTOR"))
    )
    (comp (ref "U$839")
      (value "ONE_PAD")
      (footprint "eagle-import:1X01")
      (libsource (lib "eagle-import") (part "ONE_PAD"))
    )
    (comp (ref "U$840")
      (value "ONE_PAD")
      (footprint "eagle-import:1X01")
      (libsource (lib "eagle-import") (part "ONE_PAD"))
    )
    (comp (ref "U$841")
      (value "ONE_PAD")
      (footprint "eagle-import:1X01")
      (libsource (lib "eagle-import") (part "ONE_PAD"))
    )
    (comp (ref "U$842")
      (value "ONE_PAD")
      (footprint "eagle-import:1X01")
      (libsource (lib "eagle-import") (part "ONE_PAD"))
    )
    (comp (ref "U$843")
      (value "ONE_PAD")
      (footprint "eagle-import:1X01")
      (libsource (lib "eagle-import") (part "ONE_PAD"))
    )
    (comp (ref "U$844")
      (value "ONE_PAD")
      (footprint "eagle-import:1X01")
      (libsource (lib "eagle-import") (part "ONE_PAD"))
    )
    (comp (ref "U$845")
      (value "ONE_PAD")
      (footprint "eagle-import:1X01")
      (libsource (lib "eagle-import") (part "ONE_PAD"))
    )
    (comp (ref "U$846")
      (value "ONE_PAD")
      (footprint "eagle-import:1X01")
      (libsource (lib "eagle-import") (part "ONE_PAD"))
    )
    (comp (ref "U$847")
      (value "ONE_PAD")
      (footprint "eagle-import:1X01")
      (libsource (lib "eagle-import") (part "ONE_PAD"))
    )
    (comp (ref "U$848")
      (value "ONE_PAD")
      (footprint "eagle-import:1X01")
      (libsource (lib "eagle-import") (part "ONE_PAD"))
    )
    (comp (ref "U$849")
      (value "ONE_PAD")
      (footprint "eagle-import:1X01")
      (libsource (lib "eagle-import") (part "ONE_PAD"))
    )
    (comp (ref "U$850")
      (value "ONE_PAD")
      (footprint "eagle-import:1X01")
      (libsource (lib "eagle-import") (part "ONE_PAD"))
    )
    (comp (ref "U$851")
      (value "ONE_PAD")
      (footprint "eagle-import:1X01")
      (libsource (lib "eagle-import") (part "ONE_PAD"))
    )
    (comp (ref "U$852")
      (value "ONE_PAD")
      (footprint "eagle-import:1X01")
      (libsource (lib "eagle-import") (part "ONE_PAD"))
    )
    (comp (ref "U$853")
      (value "ONE_PAD")
      (footprint "eagle-import:1X01")
      (libsource (lib "eagle-import") (part "ONE_PAD"))
    )
    (comp (ref "U$854")
      (value "ONE_PAD")
      (footprint "eagle-import:1X01")
      (libsource (lib "eagle-import") (part "ONE_PAD"))
    )
    (comp (ref "U$855")
      (value "ONE_PAD")
      (footprint "eagle-import:1X01")
      (libsource (lib "eagle-import") (part "ONE_PAD"))
    )
    (comp (ref "U$856")
      (value "ONE_PAD")
      (footprint "eagle-import:1X01")
      (libsource (lib "eagle-import") (part "ONE_PAD"))
    )
    (comp (ref "U$857")
      (value "ONE_PAD")
      (footprint "eagle-import:1X01")
      (libsource (lib "eagle-import") (part "ONE_PAD"))
    )
    (comp (ref "U$858")
      (value "ONE_PAD")
      (footprint "eagle-import:1X01")
      (libsource (lib "eagle-import") (part "ONE_PAD"))
    )
  )
  (nets
    (net (code "1") (name "/GND") (class "Default")
      (node (ref "HELLO") (pin "NEG") (pinfunction "NEG_NEG") (pintype "passive"))
      (node (ref "HELLO1") (pin "NEG") (pinfunction "NEG_NEG") (pintype "passive"))
      (node (ref "HELLO2") (pin "NEG") (pinfunction "NEG_NEG") (pintype "passive"))
      (node (ref "HELLO3") (pin "NEG") (pinfunction "NEG_NEG") (pintype "passive"))
      (node (ref "HELLO4") (pin "NEG") (pinfunction "NEG_NEG") (pintype "passive"))
      (node (ref "HELLO5") (pin "NEG") (pinfunction "NEG_NEG") (pintype "passive"))
      (node (ref "IC1") (pin "GND") (pinfunction "GND_GND") (pintype "bidirectional"))
      (node (ref "IC2") (pin "GND") (pinfunction "GND_GND") (pintype "bidirectional"))
      (node (ref "IC3") (pin "GND") (pinfunction "GND_GND") (pintype "bidirectional"))
      (node (ref "IC4") (pin "GND") (pinfunction "GND_GND") (pintype "bidirectional"))
      (node (ref "IC5") (pin "GND") (pinfunction "GND_GND") (pintype "bidirectional"))
      (node (ref "IC6") (pin "GND") (pinfunction "GND_GND") (pintype "bidirectional"))
      (node (ref "J1") (pin "GND") (pinfunction "GND_GND") (pintype "bidirectional"))
      (node (ref "J2") (pin "GND") (pinfunction "GND_GND") (pintype "bidirectional"))
      (node (ref "J3") (pin "GND") (pinfunction "GND_GND") (pintype "bidirectional"))
      (node (ref "J4") (pin "GND") (pinfunction "GND_GND") (pintype "bidirectional"))
      (node (ref "J5") (pin "GND") (pinfunction "GND_GND") (pintype "bidirectional"))
      (node (ref "J6") (pin "GND") (pinfunction "GND_GND") (pintype "bidirectional"))
      (node (ref "POWER") (pin "NEG") (pinfunction "NEG_NEG") (pintype "passive"))
      (node (ref "POWER1") (pin "NEG") (pinfunction "NEG_NEG") (pintype "passive"))
      (node (ref "POWER2") (pin "NEG") (pinfunction "NEG_NEG") (pintype "passive"))
      (node (ref "POWER3") (pin "NEG") (pinfunction "NEG_NEG") (pintype "passive"))
      (node (ref "POWER4") (pin "NEG") (pinfunction "NEG_NEG") (pintype "passive"))
      (node (ref "POWER5") (pin "NEG") (pinfunction "NEG_NEG") (pintype "passive"))
      (node (ref "U$100") (pin "P$1") (pinfunction "P_P$1") (pintype "passive"))
      (node (ref "U$123") (pin "P$1") (pinfunction "1_P$1") (pintype "passive"))
      (node (ref "U$124") (pin "P$1") (pinfunction "P_P$1") (pintype "passive"))
      (node (ref "U$125") (pin "P$1") (pinfunction "P_P$1") (pintype "passive"))
      (node (ref "U$128") (pin "P$1") (pinfunction "P_P$1") (pintype "passive"))
      (node (ref "U$129") (pin "P$1") (pinfunction "P_P$1") (pintype "passive"))
      (node (ref "U$130") (pin "P$1") (pinfunction "P_P$1") (pintype "passive"))
      (node (ref "U$131") (pin "P$1") (pinfunction "P_P$1") (pintype "passive"))
      (node (ref "U$132") (pin "P$1") (pinfunction "P_P$1") (pintype "passive"))
      (node (ref "U$133") (pin "P$1") (pinfunction "P_P$1") (pintype "passive"))
      (node (ref "U$214") (pin "P$1") (pinfunction "P_P$1") (pintype "passive"))
      (node (ref "U$264") (pin "P$1") (pinfunction "1_P$1") (pintype "passive"))
      (node (ref "U$267") (pin "P$1") (pinfunction "P_P$1") (pintype "passive"))
      (node (ref "U$268") (pin "P$1") (pinfunction "P_P$1") (pintype "passive"))
      (node (ref "U$269") (pin "P$1") (pinfunction "P_P$1") (pintype "passive"))
      (node (ref "U$270") (pin "P$1") (pinfunction "P_P$1") (pintype "passive"))
      (node (ref "U$271") (pin "P$1") (pinfunction "P_P$1") (pintype "passive"))
      (node (ref "U$272") (pin "P$1") (pinfunction "P_P$1") (pintype "passive"))
      (node (ref "U$273") (pin "P$1") (pinfunction "P_P$1") (pintype "passive"))
      (node (ref "U$274") (pin "P$1") (pinfunction "P_P$1") (pintype "passive"))
      (node (ref "U$275") (pin "P$1") (pinfunction "P_P$1") (pintype "passive"))
      (node (ref "U$276") (pin "P$1") (pinfunction "P_P$1") (pintype "passive"))
      (node (ref "U$357") (pin "P$1") (pinfunction "P_P$1") (pintype "passive"))
      (node (ref "U$407") (pin "P$1") (pinfunction "1_P$1") (pintype "passive"))
      (node (ref "U$410") (pin "P$1") (pinfunction "P_P$1") (pintype "passive"))
      (node (ref "U$411") (pin "P$1") (pinfunction "P_P$1") (pintype "passive"))
      (node (ref "U$412") (pin "P$1") (pinfunction "P_P$1") (pintype "passive"))
      (node (ref "U$413") (pin "P$1") (pinfunction "P_P$1") (pintype "passive"))
      (node (ref "U$414") (pin "P$1") (pinfunction "P_P$1") (pintype "passive"))
      (node (ref "U$415") (pin "P$1") (pinfunction "P_P$1") (pintype "passive"))
      (node (ref "U$416") (pin "P$1") (pinfunction "P_P$1") (pintype "passive"))
      (node (ref "U$417") (pin "P$1") (pinfunction "P_P$1") (pintype "passive"))
      (node (ref "U$418") (pin "P$1") (pinfunction "P_P$1") (pintype "passive"))
      (node (ref "U$419") (pin "P$1") (pinfunction "P_P$1") (pintype "passive"))
      (node (ref "U$500") (pin "P$1") (pinfunction "P_P$1") (pintype "passive"))
      (node (ref "U$550") (pin "P$1") (pinfunction "1_P$1") (pintype "passive"))
      (node (ref "U$553") (pin "P$1") (pinfunction "P_P$1") (pintype "passive"))
      (node (ref "U$554") (pin "P$1") (pinfunction "P_P$1") (pintype "passive"))
      (node (ref "U$555") (pin "P$1") (pinfunction "P_P$1") (pintype "passive"))
      (node (ref "U$556") (pin "P$1") (pinfunction "P_P$1") (pintype "passive"))
      (node (ref "U$557") (pin "P$1") (pinfunction "P_P$1") (pintype "passive"))
      (node (ref "U$558") (pin "P$1") (pinfunction "P_P$1") (pintype "passive"))
      (node (ref "U$559") (pin "P$1") (pinfunction "P_P$1") (pintype "passive"))
      (node (ref "U$560") (pin "P$1") (pinfunction "P_P$1") (pintype "passive"))
      (node (ref "U$561") (pin "P$1") (pinfunction "P_P$1") (pintype "passive"))
      (node (ref "U$562") (pin "P$1") (pinfunction "P_P$1") (pintype "passive"))
      (node (ref "U$643") (pin "P$1") (pinfunction "P_P$1") (pintype "passive"))
      (node (ref "U$693") (pin "P$1") (pinfunction "1_P$1") (pintype "passive"))
      (node (ref "U$696") (pin "P$1") (pinfunction "P_P$1") (pintype "passive"))
      (node (ref "U$697") (pin "P$1") (pinfunction "P_P$1") (pintype "passive"))
      (node (ref "U$698") (pin "P$1") (pinfunction "P_P$1") (pintype "passive"))
      (node (ref "U$699") (pin "P$1") (pinfunction "P_P$1") (pintype "passive"))
      (node (ref "U$700") (pin "P$1") (pinfunction "P_P$1") (pintype "passive"))
      (node (ref "U$701") (pin "P$1") (pinfunction "P_P$1") (pintype "passive"))
      (node (ref "U$702") (pin "P$1") (pinfunction "P_P$1") (pintype "passive"))
      (node (ref "U$703") (pin "P$1") (pinfunction "P_P$1") (pintype "passive"))
      (node (ref "U$704") (pin "P$1") (pinfunction "P_P$1") (pintype "passive"))
      (node (ref "U$705") (pin "P$1") (pinfunction "P_P$1") (pintype "passive"))
      (node (ref "U$71") (pin "P$1") (pinfunction "P_P$1") (pintype "passive"))
      (node (ref "U$786") (pin "P$1") (pinfunction "P_P$1") (pintype "passive"))
      (node (ref "U$836") (pin "P$1") (pinfunction "1_P$1") (pintype "passive"))
      (node (ref "U$839") (pin "P$1") (pinfunction "P_P$1") (pintype "passive"))
      (node (ref "U$840") (pin "P$1") (pinfunction "P_P$1") (pintype "passive"))
      (node (ref "U$841") (pin "P$1") (pinfunction "P_P$1") (pintype "passive"))
      (node (ref "U$842") (pin "P$1") (pinfunction "P_P$1") (pintype "passive"))
      (node (ref "U$843") (pin "P$1") (pinfunction "P_P$1") (pintype "passive"))
      (node (ref "U$844") (pin "P$1") (pinfunction "P_P$1") (pintype "passive"))
      (node (ref "U$845") (pin "P$1") (pinfunction "P_P$1") (pintype "passive"))
      (node (ref "U$846") (pin "P$1") (pinfunction "P_P$1") (pintype "passive"))
      (node (ref "U$847") (pin "P$1") (pinfunction "P_P$1") (pintype "passive"))
      (node (ref "U$848") (pin "P$1") (pinfunction "P_P$1") (pintype "passive"))
      (node (ref "U$99") (pin "P$1") (pinfunction "P_P$1") (pintype "passive"))
    )
    (net (code "2") (name "/PB0") (class "Default")
      (node (ref "IC1") (pin "PB0") (pinfunction "PB0_PB0") (pintype "bidirectional"))
      (node (ref "IC2") (pin "PB0") (pinfunction "PB0_PB0") (pintype "bidirectional"))
      (node (ref "IC3") (pin "PB0") (pinfunction "PB0_PB0") (pintype "bidirectional"))
      (node (ref "IC4") (pin "PB0") (pinfunction "PB0_PB0") (pintype "bidirectional"))
      (node (ref "IC5") (pin "PB0") (pinfunction "PB0_PB0") (pintype "bidirectional"))
      (node (ref "IC6") (pin "PB0") (pinfunction "PB0_PB0") (pintype "bidirectional"))
      (node (ref "J1") (pin "0/MOSI/SDA") (pinfunction "PB0/MOSI/SDA_0/MOSI/SDA") (pintype "bidirectional"))
      (node (ref "J2") (pin "0/MOSI/SDA") (pinfunction "PB0/MOSI/SDA_0/MOSI/SDA") (pintype "bidirectional"))
      (node (ref "J3") (pin "0/MOSI/SDA") (pinfunction "PB0/MOSI/SDA_0/MOSI/SDA") (pintype "bidirectional"))
      (node (ref "J4") (pin "0/MOSI/SDA") (pinfunction "PB0/MOSI/SDA_0/MOSI/SDA") (pintype "bidirectional"))
      (node (ref "J5") (pin "0/MOSI/SDA") (pinfunction "PB0/MOSI/SDA_0/MOSI/SDA") (pintype "bidirectional"))
      (node (ref "J6") (pin "0/MOSI/SDA") (pinfunction "PB0/MOSI/SDA_0/MOSI/SDA") (pintype "bidirectional"))
      (node (ref "U$127") (pin "P$4") (pinfunction "2_P$4") (pintype "passive"))
      (node (ref "U$216") (pin "P$1") (pinfunction "P_P$1") (pintype "passive"))
      (node (ref "U$218") (pin "P$1") (pinfunction "P_P$1") (pintype "passive"))
      (node (ref "U$219") (pin "P$1") (pinfunction "P_P$1") (pintype "passive"))
      (node (ref "U$220") (pin "P$1") (pinfunction "P_P$1") (pintype "passive"))
      (node (ref "U$266") (pin "P$4") (pinfunction "2_P$4") (pintype "passive"))
      (node (ref "U$359") (pin "P$1") (pinfunction "P_P$1") (pintype "passive"))
      (node (ref "U$361") (pin "P$1") (pinfunction "P_P$1") (pintype "passive"))
      (node (ref "U$362") (pin "P$1") (pinfunction "P_P$1") (pintype "passive"))
      (node (ref "U$363") (pin "P$1") (pinfunction "P_P$1") (pintype "passive"))
      (node (ref "U$409") (pin "P$4") (pinfunction "2_P$4") (pintype "passive"))
      (node (ref "U$502") (pin "P$1") (pinfunction "P_P$1") (pintype "passive"))
      (node (ref "U$504") (pin "P$1") (pinfunction "P_P$1") (pintype "passive"))
      (node (ref "U$505") (pin "P$1") (pinfunction "P_P$1") (pintype "passive"))
      (node (ref "U$506") (pin "P$1") (pinfunction "P_P$1") (pintype "passive"))
      (node (ref "U$552") (pin "P$4") (pinfunction "2_P$4") (pintype "passive"))
      (node (ref "U$645") (pin "P$1") (pinfunction "P_P$1") (pintype "passive"))
      (node (ref "U$647") (pin "P$1") (pinfunction "P_P$1") (pintype "passive"))
      (node (ref "U$648") (pin "P$1") (pinfunction "P_P$1") (pintype "passive"))
      (node (ref "U$649") (pin "P$1") (pinfunction "P_P$1") (pintype "passive"))
      (node (ref "U$695") (pin "P$4") (pinfunction "2_P$4") (pintype "passive"))
      (node (ref "U$72") (pin "P$1") (pinfunction "P_P$1") (pintype "passive"))
      (node (ref "U$75") (pin "P$1") (pinfunction "P_P$1") (pintype "passive"))
      (node (ref "U$76") (pin "P$1") (pinfunction "P_P$1") (pintype "passive"))
      (node (ref "U$77") (pin "P$1") (pinfunction "P_P$1") (pintype "passive"))
      (node (ref "U$788") (pin "P$1") (pinfunction "P_P$1") (pintype "passive"))
      (node (ref "U$790") (pin "P$1") (pinfunction "P_P$1") (pintype "passive"))
      (node (ref "U$791") (pin "P$1") (pinfunction "P_P$1") (pintype "passive"))
      (node (ref "U$792") (pin "P$1") (pinfunction "P_P$1") (pintype "passive"))
      (node (ref "U$838") (pin "P$4") (pinfunction "2_P$4") (pintype "passive"))
    )
    (net (code "3") (name "/PB1") (class "Default")
      (node (ref "IC1") (pin "PB1") (pinfunction "PB1_PB1") (pintype "bidirectional"))
      (node (ref "IC2") (pin "PB1") (pinfunction "PB1_PB1") (pintype "bidirectional"))
      (node (ref "IC3") (pin "PB1") (pinfunction "PB1_PB1") (pintype "bidirectional"))
      (node (ref "IC4") (pin "PB1") (pinfunction "PB1_PB1") (pintype "bidirectional"))
      (node (ref "IC5") (pin "PB1") (pinfunction "PB1_PB1") (pintype "bidirectional"))
      (node (ref "IC6") (pin "PB1") (pinfunction "PB1_PB1") (pintype "bidirectional"))
      (node (ref "J1") (pin "1/MISO") (pinfunction "PB1/MISO_1/MISO") (pintype "bidirectional"))
      (node (ref "J2") (pin "1/MISO") (pinfunction "PB1/MISO_1/MISO") (pintype "bidirectional"))
      (node (ref "J3") (pin "1/MISO") (pinfunction "PB1/MISO_1/MISO") (pintype "bidirectional"))
      (node (ref "J4") (pin "1/MISO") (pinfunction "PB1/MISO_1/MISO") (pintype "bidirectional"))
      (node (ref "J5") (pin "1/MISO") (pinfunction "PB1/MISO_1/MISO") (pintype "bidirectional"))
      (node (ref "J6") (pin "1/MISO") (pinfunction "PB1/MISO_1/MISO") (pintype "bidirectional"))
      (node (ref "U$221") (pin "P$1") (pinfunction "P_P$1") (pintype "passive"))
      (node (ref "U$222") (pin "P$1") (pinfunction "P_P$1") (pintype "passive"))
      (node (ref "U$223") (pin "P$1") (pinfunction "P_P$1") (pintype "passive"))
      (node (ref "U$364") (pin "P$1") (pinfunction "P_P$1") (pintype "passive"))
      (node (ref "U$365") (pin "P$1") (pinfunction "P_P$1") (pintype "passive"))
      (node (ref "U$366") (pin "P$1") (pinfunction "P_P$1") (pintype "passive"))
      (node (ref "U$507") (pin "P$1") (pinfunction "P_P$1") (pintype "passive"))
      (node (ref "U$508") (pin "P$1") (pinfunction "P_P$1") (pintype "passive"))
      (node (ref "U$509") (pin "P$1") (pinfunction "P_P$1") (pintype "passive"))
      (node (ref "U$650") (pin "P$1") (pinfunction "P_P$1") (pintype "passive"))
      (node (ref "U$651") (pin "P$1") (pinfunction "P_P$1") (pintype "passive"))
      (node (ref "U$652") (pin "P$1") (pinfunction "P_P$1") (pintype "passive"))
      (node (ref "U$78") (pin "P$1") (pinfunction "P_P$1") (pintype "passive"))
      (node (ref "U$79") (pin "P$1") (pinfunction "P_P$1") (pintype "passive"))
      (node (ref "U$793") (pin "P$1") (pinfunction "P_P$1") (pintype "passive"))
      (node (ref "U$794") (pin "P$1") (pinfunction "P_P$1") (pintype "passive"))
      (node (ref "U$795") (pin "P$1") (pinfunction "P_P$1") (pintype "passive"))
      (node (ref "U$80") (pin "P$1") (pinfunction "P_P$1") (pintype "passive"))
    )
    (net (code "4") (name "/PB2") (class "Default")
      (node (ref "IC1") (pin "PB2") (pinfunction "PB2_PB2") (pintype "bidirectional"))
      (node (ref "IC2") (pin "PB2") (pinfunction "PB2_PB2") (pintype "bidirectional"))
      (node (ref "IC3") (pin "PB2") (pinfunction "PB2_PB2") (pintype "bidirectional"))
      (node (ref "IC4") (pin "PB2") (pinfunction "PB2_PB2") (pintype "bidirectional"))
      (node (ref "IC5") (pin "PB2") (pinfunction "PB2_PB2") (pintype "bidirectional"))
      (node (ref "IC6") (pin "PB2") (pinfunction "PB2_PB2") (pintype "bidirectional"))
      (node (ref "J1") (pin "2/SCK/SCL") (pinfunction "PB2/SCK/SCL_2/SCK/SCL") (pintype "bidirectional"))
      (node (ref "J2") (pin "2/SCK/SCL") (pinfunction "PB2/SCK/SCL_2/SCK/SCL") (pintype "bidirectional"))
      (node (ref "J3") (pin "2/SCK/SCL") (pinfunction "PB2/SCK/SCL_2/SCK/SCL") (pintype "bidirectional"))
      (node (ref "J4") (pin "2/SCK/SCL") (pinfunction "PB2/SCK/SCL_2/SCK/SCL") (pintype "bidirectional"))
      (node (ref "J5") (pin "2/SCK/SCL") (pinfunction "PB2/SCK/SCL_2/SCK/SCL") (pintype "bidirectional"))
      (node (ref "J6") (pin "2/SCK/SCL") (pinfunction "PB2/SCK/SCL_2/SCK/SCL") (pintype "bidirectional"))
      (node (ref "U$217") (pin "P$1") (pinfunction "P_P$1") (pintype "passive"))
      (node (ref "U$224") (pin "P$1") (pinfunction "P_P$1") (pintype "passive"))
      (node (ref "U$225") (pin "P$1") (pinfunction "P_P$1") (pintype "passive"))
      (node (ref "U$226") (pin "P$1") (pinfunction "P_P$1") (pintype "passive"))
      (node (ref "U$360") (pin "P$1") (pinfunction "P_P$1") (pintype "passive"))
      (node (ref "U$367") (pin "P$1") (pinfunction "P_P$1") (pintype "passive"))
      (node (ref "U$368") (pin "P$1") (pinfunction "P_P$1") (pintype "passive"))
      (node (ref "U$369") (pin "P$1") (pinfunction "P_P$1") (pintype "passive"))
      (node (ref "U$503") (pin "P$1") (pinfunction "P_P$1") (pintype "passive"))
      (node (ref "U$510") (pin "P$1") (pinfunction "P_P$1") (pintype "passive"))
      (node (ref "U$511") (pin "P$1") (pinfunction "P_P$1") (pintype "passive"))
      (node (ref "U$512") (pin "P$1") (pinfunction "P_P$1") (pintype "passive"))
      (node (ref "U$646") (pin "P$1") (pinfunction "P_P$1") (pintype "passive"))
      (node (ref "U$653") (pin "P$1") (pinfunction "P_P$1") (pintype "passive"))
      (node (ref "U$654") (pin "P$1") (pinfunction "P_P$1") (pintype "passive"))
      (node (ref "U$655") (pin "P$1") (pinfunction "P_P$1") (pintype "passive"))
      (node (ref "U$73") (pin "P$1") (pinfunction "P_P$1") (pintype "passive"))
      (node (ref "U$789") (pin "P$1") (pinfunction "P_P$1") (pintype "passive"))
      (node (ref "U$796") (pin "P$1") (pinfunction "P_P$1") (pintype "passive"))
      (node (ref "U$797") (pin "P$1") (pinfunction "P_P$1") (pintype "passive"))
      (node (ref "U$798") (pin "P$1") (pinfunction "P_P$1") (pintype "passive"))
      (node (ref "U$81") (pin "P$1") (pinfunction "P_P$1") (pintype "passive"))
      (node (ref "U$82") (pin "P$1") (pinfunction "P_P$1") (pintype "passive"))
      (node (ref "U$83") (pin "P$1") (pinfunction "P_P$1") (pintype "passive"))
    )
    (net (code "5") (name "/PB3") (class "Default")
      (node (ref "IC1") (pin "PB3") (pinfunction "PB3_PB3") (pintype "bidirectional"))
      (node (ref "IC2") (pin "PB3") (pinfunction "PB3_PB3") (pintype "bidirectional"))
      (node (ref "IC3") (pin "PB3") (pinfunction "PB3_PB3") (pintype "bidirectional"))
      (node (ref "IC4") (pin "PB3") (pinfunction "PB3_PB3") (pintype "bidirectional"))
      (node (ref "IC5") (pin "PB3") (pinfunction "PB3_PB3") (pintype "bidirectional"))
      (node (ref "IC6") (pin "PB3") (pinfunction "PB3_PB3") (pintype "bidirectional"))
      (node (ref "U$227") (pin "P$1") (pinfunction "P_P$1") (pintype "passive"))
      (node (ref "U$228") (pin "P$1") (pinfunction "P_P$1") (pintype "passive"))
      (node (ref "U$229") (pin "P$1") (pinfunction "P_P$1") (pintype "passive"))
      (node (ref "U$370") (pin "P$1") (pinfunction "P_P$1") (pintype "passive"))
      (node (ref "U$371") (pin "P$1") (pinfunction "P_P$1") (pintype "passive"))
      (node (ref "U$372") (pin "P$1") (pinfunction "P_P$1") (pintype "passive"))
      (node (ref "U$513") (pin "P$1") (pinfunction "P_P$1") (pintype "passive"))
      (node (ref "U$514") (pin "P$1") (pinfunction "P_P$1") (pintype "passive"))
      (node (ref "U$515") (pin "P$1") (pinfunction "P_P$1") (pintype "passive"))
      (node (ref "U$656") (pin "P$1") (pinfunction "P_P$1") (pintype "passive"))
      (node (ref "U$657") (pin "P$1") (pinfunction "P_P$1") (pintype "passive"))
      (node (ref "U$658") (pin "P$1") (pinfunction "P_P$1") (pintype "passive"))
      (node (ref "U$799") (pin "P$1") (pinfunction "P_P$1") (pintype "passive"))
      (node (ref "U$800") (pin "P$1") (pinfunction "P_P$1") (pintype "passive"))
      (node (ref "U$801") (pin "P$1") (pinfunction "P_P$1") (pintype "passive"))
      (node (ref "U$84") (pin "P$1") (pinfunction "P_P$1") (pintype "passive"))
      (node (ref "U$85") (pin "P$1") (pinfunction "P_P$1") (pintype "passive"))
      (node (ref "U$86") (pin "P$1") (pinfunction "P_P$1") (pintype "passive"))
    )
    (net (code "6") (name "/PB4") (class "Default")
      (node (ref "IC1") (pin "PB4") (pinfunction "PB4_PB4") (pintype "bidirectional"))
      (node (ref "IC2") (pin "PB4") (pinfunction "PB4_PB4") (pintype "bidirectional"))
      (node (ref "IC3") (pin "PB4") (pinfunction "PB4_PB4") (pintype "bidirectional"))
      (node (ref "IC4") (pin "PB4") (pinfunction "PB4_PB4") (pintype "bidirectional"))
      (node (ref "IC5") (pin "PB4") (pinfunction "PB4_PB4") (pintype "bidirectional"))
      (node (ref "IC6") (pin "PB4") (pinfunction "PB4_PB4") (pintype "bidirectional"))
      (node (ref "U$230") (pin "P$1") (pinfunction "P_P$1") (pintype "passive"))
      (node (ref "U$231") (pin "P$1") (pinfunction "P_P$1") (pintype "passive"))
      (node (ref "U$232") (pin "P$1") (pinfunction "P_P$1") (pintype "passive"))
      (node (ref "U$373") (pin "P$1") (pinfunction "P_P$1") (pintype "passive"))
      (node (ref "U$374") (pin "P$1") (pinfunction "P_P$1") (pintype "passive"))
      (node (ref "U$375") (pin "P$1") (pinfunction "P_P$1") (pintype "passive"))
      (node (ref "U$516") (pin "P$1") (pinfunction "P_P$1") (pintype "passive"))
      (node (ref "U$517") (pin "P$1") (pinfunction "P_P$1") (pintype "passive"))
      (node (ref "U$518") (pin "P$1") (pinfunction "P_P$1") (pintype "passive"))
      (node (ref "U$659") (pin "P$1") (pinfunction "P_P$1") (pintype "passive"))
      (node (ref "U$660") (pin "P$1") (pinfunction "P_P$1") (pintype "passive"))
      (node (ref "U$661") (pin "P$1") (pinfunction "P_P$1") (pintype "passive"))
      (node (ref "U$802") (pin "P$1") (pinfunction "P_P$1") (pintype "passive"))
      (node (ref "U$803") (pin "P$1") (pinfunction "P_P$1") (pintype "passive"))
      (node (ref "U$804") (pin "P$1") (pinfunction "P_P$1") (pintype "passive"))
      (node (ref "U$87") (pin "P$1") (pinfunction "P_P$1") (pintype "passive"))
      (node (ref "U$88") (pin "P$1") (pinfunction "P_P$1") (pintype "passive"))
      (node (ref "U$89") (pin "P$1") (pinfunction "P_P$1") (pintype "passive"))
    )
    (net (code "7") (name "/PB5") (class "Default")
      (node (ref "IC1") (pin "PB5") (pinfunction "PB5_PB5") (pintype "bidirectional"))
      (node (ref "IC2") (pin "PB5") (pinfunction "PB5_PB5") (pintype "bidirectional"))
      (node (ref "IC3") (pin "PB5") (pinfunction "PB5_PB5") (pintype "bidirectional"))
      (node (ref "IC4") (pin "PB5") (pinfunction "PB5_PB5") (pintype "bidirectional"))
      (node (ref "IC5") (pin "PB5") (pinfunction "PB5_PB5") (pintype "bidirectional"))
      (node (ref "IC6") (pin "PB5") (pinfunction "PB5_PB5") (pintype "bidirectional"))
      (node (ref "J1") (pin "5/RST") (pinfunction "PB5/RST_5/RST") (pintype "bidirectional"))
      (node (ref "J2") (pin "5/RST") (pinfunction "PB5/RST_5/RST") (pintype "bidirectional"))
      (node (ref "J3") (pin "5/RST") (pinfunction "PB5/RST_5/RST") (pintype "bidirectional"))
      (node (ref "J4") (pin "5/RST") (pinfunction "PB5/RST_5/RST") (pintype "bidirectional"))
      (node (ref "J5") (pin "5/RST") (pinfunction "PB5/RST_5/RST") (pintype "bidirectional"))
      (node (ref "J6") (pin "5/RST") (pinfunction "PB5/RST_5/RST") (pintype "bidirectional"))
      (node (ref "U$233") (pin "P$1") (pinfunction "P_P$1") (pintype "passive"))
      (node (ref "U$234") (pin "P$1") (pinfunction "P_P$1") (pintype "passive"))
      (node (ref "U$235") (pin "P$1") (pinfunction "P_P$1") (pintype "passive"))
      (node (ref "U$376") (pin "P$1") (pinfunction "P_P$1") (pintype "passive"))
      (node (ref "U$377") (pin "P$1") (pinfunction "P_P$1") (pintype "passive"))
      (node (ref "U$378") (pin "P$1") (pinfunction "P_P$1") (pintype "passive"))
      (node (ref "U$519") (pin "P$1") (pinfunction "P_P$1") (pintype "passive"))
      (node (ref "U$520") (pin "P$1") (pinfunction "P_P$1") (pintype "passive"))
      (node (ref "U$521") (pin "P$1") (pinfunction "P_P$1") (pintype "passive"))
      (node (ref "U$662") (pin "P$1") (pinfunction "P_P$1") (pintype "passive"))
      (node (ref "U$663") (pin "P$1") (pinfunction "P_P$1") (pintype "passive"))
      (node (ref "U$664") (pin "P$1") (pinfunction "P_P$1") (pintype "passive"))
      (node (ref "U$805") (pin "P$1") (pinfunction "P_P$1") (pintype "passive"))
      (node (ref "U$806") (pin "P$1") (pinfunction "P_P$1") (pintype "passive"))
      (node (ref "U$807") (pin "P$1") (pinfunction "P_P$1") (pintype "passive"))
      (node (ref "U$90") (pin "P$1") (pinfunction "P_P$1") (pintype "passive"))
      (node (ref "U$91") (pin "P$1") (pinfunction "P_P$1") (pintype "passive"))
      (node (ref "U$92") (pin "P$1") (pinfunction "P_P$1") (pintype "passive"))
    )
    (net (code "8") (name "/VCC") (class "Default")
      (node (ref "IC1") (pin "VCC") (pinfunction "VCC_VCC") (pintype "bidirectional"))
      (node (ref "IC2") (pin "VCC") (pinfunction "VCC_VCC") (pintype "bidirectional"))
      (node (ref "IC3") (pin "VCC") (pinfunction "VCC_VCC") (pintype "bidirectional"))
      (node (ref "IC4") (pin "VCC") (pinfunction "VCC_VCC") (pintype "bidirectional"))
      (node (ref "IC5") (pin "VCC") (pinfunction "VCC_VCC") (pintype "bidirectional"))
      (node (ref "IC6") (pin "VCC") (pinfunction "VCC_VCC") (pintype "bidirectional"))
      (node (ref "J1") (pin "VCC") (pinfunction "VCC_VCC") (pintype "bidirectional"))
      (node (ref "J2") (pin "VCC") (pinfunction "VCC_VCC") (pintype "bidirectional"))
      (node (ref "J3") (pin "VCC") (pinfunction "VCC_VCC") (pintype "bidirectional"))
      (node (ref "J4") (pin "VCC") (pinfunction "VCC_VCC") (pintype "bidirectional"))
      (node (ref "J5") (pin "VCC") (pinfunction "VCC_VCC") (pintype "bidirectional"))
      (node (ref "J6") (pin "VCC") (pinfunction "VCC_VCC") (pintype "bidirectional"))
      (node (ref "U$123") (pin "P$2") (pinfunction "2_P$2") (pintype "passive"))
      (node (ref "U$126") (pin "P$4") (pinfunction "2_P$4") (pintype "passive"))
      (node (ref "U$134") (pin "P$1") (pinfunction "P_P$1") (pintype "passive"))
      (node (ref "U$135") (pin "P$1") (pinfunction "P_P$1") (pintype "passive"))
      (node (ref "U$136") (pin "P$1") (pinfunction "P_P$1") (pintype "passive"))
      (node (ref "U$137") (pin "P$1") (pinfunction "P_P$1") (pintype "passive"))
      (node (ref "U$138") (pin "P$1") (pinfunction "P_P$1") (pintype "passive"))
      (node (ref "U$139") (pin "P$1") (pinfunction "P_P$1") (pintype "passive"))
      (node (ref "U$140") (pin "P$1") (pinfunction "P_P$1") (pintype "passive"))
      (node (ref "U$141") (pin "P$1") (pinfunction "P_P$1") (pintype "passive"))
      (node (ref "U$142") (pin "P$1") (pinfunction "P_P$1") (pintype "passive"))
      (node (ref "U$143") (pin "P$1") (pinfunction "P_P$1") (pintype "passive"))
      (node (ref "U$215") (pin "P$1") (pinfunction "P_P$1") (pintype "passive"))
      (node (ref "U$264") (pin "P$2") (pinfunction "2_P$2") (pintype "passive"))
      (node (ref "U$265") (pin "P$4") (pinfunction "2_P$4") (pintype "passive"))
      (node (ref "U$277") (pin "P$1") (pinfunction "P_P$1") (pintype "passive"))
      (node (ref "U$278") (pin "P$1") (pinfunction "P_P$1") (pintype "passive"))
      (node (ref "U$279") (pin "P$1") (pinfunction "P_P$1") (pintype "passive"))
      (node (ref "U$280") (pin "P$1") (pinfunction "P_P$1") (pintype "passive"))
      (node (ref "U$281") (pin "P$1") (pinfunction "P_P$1") (pintype "passive"))
      (node (ref "U$282") (pin "P$1") (pinfunction "P_P$1") (pintype "passive"))
      (node (ref "U$283") (pin "P$1") (pinfunction "P_P$1") (pintype "passive"))
      (node (ref "U$284") (pin "P$1") (pinfunction "P_P$1") (pintype "passive"))
      (node (ref "U$285") (pin "P$1") (pinfunction "P_P$1") (pintype "passive"))
      (node (ref "U$286") (pin "P$1") (pinfunction "P_P$1") (pintype "passive"))
      (node (ref "U$358") (pin "P$1") (pinfunction "P_P$1") (pintype "passive"))
      (node (ref "U$407") (pin "P$2") (pinfunction "2_P$2") (pintype "passive"))
      (node (ref "U$408") (pin "P$4") (pinfunction "2_P$4") (pintype "passive"))
      (node (ref "U$420") (pin "P$1") (pinfunction "P_P$1") (pintype "passive"))
      (node (ref "U$421") (pin "P$1") (pinfunction "P_P$1") (pintype "passive"))
      (node (ref "U$422") (pin "P$1") (pinfunction "P_P$1") (pintype "passive"))
      (node (ref "U$423") (pin "P$1") (pinfunction "P_P$1") (pintype "passive"))
      (node (ref "U$424") (pin "P$1") (pinfunction "P_P$1") (pintype "passive"))
      (node (ref "U$425") (pin "P$1") (pinfunction "P_P$1") (pintype "passive"))
      (node (ref "U$426") (pin "P$1") (pinfunction "P_P$1") (pintype "passive"))
      (node (ref "U$427") (pin "P$1") (pinfunction "P_P$1") (pintype "passive"))
      (node (ref "U$428") (pin "P$1") (pinfunction "P_P$1") (pintype "passive"))
      (node (ref "U$429") (pin "P$1") (pinfunction "P_P$1") (pintype "passive"))
      (node (ref "U$501") (pin "P$1") (pinfunction "P_P$1") (pintype "passive"))
      (node (ref "U$550") (pin "P$2") (pinfunction "2_P$2") (pintype "passive"))
      (node (ref "U$551") (pin "P$4") (pinfunction "2_P$4") (pintype "passive"))
      (node (ref "U$563") (pin "P$1") (pinfunction "P_P$1") (pintype "passive"))
      (node (ref "U$564") (pin "P$1") (pinfunction "P_P$1") (pintype "passive"))
      (node (ref "U$565") (pin "P$1") (pinfunction "P_P$1") (pintype "passive"))
      (node (ref "U$566") (pin "P$1") (pinfunction "P_P$1") (pintype "passive"))
      (node (ref "U$567") (pin "P$1") (pinfunction "P_P$1") (pintype "passive"))
      (node (ref "U$568") (pin "P$1") (pinfunction "P_P$1") (pintype "passive"))
      (node (ref "U$569") (pin "P$1") (pinfunction "P_P$1") (pintype "passive"))
      (node (ref "U$570") (pin "P$1") (pinfunction "P_P$1") (pintype "passive"))
      (node (ref "U$571") (pin "P$1") (pinfunction "P_P$1") (pintype "passive"))
      (node (ref "U$572") (pin "P$1") (pinfunction "P_P$1") (pintype "passive"))
      (node (ref "U$644") (pin "P$1") (pinfunction "P_P$1") (pintype "passive"))
      (node (ref "U$693") (pin "P$2") (pinfunction "2_P$2") (pintype "passive"))
      (node (ref "U$694") (pin "P$4") (pinfunction "2_P$4") (pintype "passive"))
      (node (ref "U$706") (pin "P$1") (pinfunction "P_P$1") (pintype "passive"))
      (node (ref "U$707") (pin "P$1") (pinfunction "P_P$1") (pintype "passive"))
      (node (ref "U$708") (pin "P$1") (pinfunction "P_P$1") (pintype "passive"))
      (node (ref "U$709") (pin "P$1") (pinfunction "P_P$1") (pintype "passive"))
      (node (ref "U$710") (pin "P$1") (pinfunction "P_P$1") (pintype "passive"))
      (node (ref "U$711") (pin "P$1") (pinfunction "P_P$1") (pintype "passive"))
      (node (ref "U$712") (pin "P$1") (pinfunction "P_P$1") (pintype "passive"))
      (node (ref "U$713") (pin "P$1") (pinfunction "P_P$1") (pintype "passive"))
      (node (ref "U$714") (pin "P$1") (pinfunction "P_P$1") (pintype "passive"))
      (node (ref "U$715") (pin "P$1") (pinfunction "P_P$1") (pintype "passive"))
      (node (ref "U$74") (pin "P$1") (pinfunction "P_P$1") (pintype "passive"))
      (node (ref "U$787") (pin "P$1") (pinfunction "P_P$1") (pintype "passive"))
      (node (ref "U$836") (pin "P$2") (pinfunction "2_P$2") (pintype "passive"))
      (node (ref "U$837") (pin "P$4") (pinfunction "2_P$4") (pintype "passive"))
      (node (ref "U$849") (pin "P$1") (pinfunction "P_P$1") (pintype "passive"))
      (node (ref "U$850") (pin "P$1") (pinfunction "P_P$1") (pintype "passive"))
      (node (ref "U$851") (pin "P$1") (pinfunction "P_P$1") (pintype "passive"))
      (node (ref "U$852") (pin "P$1") (pinfunction "P_P$1") (pintype "passive"))
      (node (ref "U$853") (pin "P$1") (pinfunction "P_P$1") (pintype "passive"))
      (node (ref "U$854") (pin "P$1") (pinfunction "P_P$1") (pintype "passive"))
      (node (ref "U$855") (pin "P$1") (pinfunction "P_P$1") (pintype "passive"))
      (node (ref "U$856") (pin "P$1") (pinfunction "P_P$1") (pintype "passive"))
      (node (ref "U$857") (pin "P$1") (pinfunction "P_P$1") (pintype "passive"))
      (node (ref "U$858") (pin "P$1") (pinfunction "P_P$1") (pintype "passive"))
    )
    (net (code "9") (name "Net-(U$126-1)") (class "Default")
      (node (ref "POWER") (pin "POS") (pinfunction "POS_POS") (pintype "passive"))
      (node (ref "U$126") (pin "P$3") (pinfunction "1_P$3") (pintype "passive"))
    )
    (net (code "10") (name "Net-(U$127-1)") (class "Default")
      (node (ref "HELLO") (pin "POS") (pinfunction "POS_POS") (pintype "passive"))
      (node (ref "U$127") (pin "P$3") (pinfunction "1_P$3") (pintype "passive"))
    )
    (net (code "11") (name "Net-(U$265-1)") (class "Default")
      (node (ref "POWER1") (pin "POS") (pinfunction "POS_POS") (pintype "passive"))
      (node (ref "U$265") (pin "P$3") (pinfunction "1_P$3") (pintype "passive"))
    )
    (net (code "12") (name "Net-(U$266-1)") (class "Default")
      (node (ref "HELLO1") (pin "POS") (pinfunction "POS_POS") (pintype "passive"))
      (node (ref "U$266") (pin "P$3") (pinfunction "1_P$3") (pintype "passive"))
    )
    (net (code "13") (name "Net-(U$408-1)") (class "Default")
      (node (ref "POWER2") (pin "POS") (pinfunction "POS_POS") (pintype "passive"))
      (node (ref "U$408") (pin "P$3") (pinfunction "1_P$3") (pintype "passive"))
    )
    (net (code "14") (name "Net-(U$409-1)") (class "Default")
      (node (ref "HELLO2") (pin "POS") (pinfunction "POS_POS") (pintype "passive"))
      (node (ref "U$409") (pin "P$3") (pinfunction "1_P$3") (pintype "passive"))
    )
    (net (code "15") (name "Net-(U$551-1)") (class "Default")
      (node (ref "POWER3") (pin "POS") (pinfunction "POS_POS") (pintype "passive"))
      (node (ref "U$551") (pin "P$3") (pinfunction "1_P$3") (pintype "passive"))
    )
    (net (code "16") (name "Net-(U$552-1)") (class "Default")
      (node (ref "HELLO3") (pin "POS") (pinfunction "POS_POS") (pintype "passive"))
      (node (ref "U$552") (pin "P$3") (pinfunction "1_P$3") (pintype "passive"))
    )
    (net (code "17") (name "Net-(U$694-1)") (class "Default")
      (node (ref "POWER4") (pin "POS") (pinfunction "POS_POS") (pintype "passive"))
      (node (ref "U$694") (pin "P$3") (pinfunction "1_P$3") (pintype "passive"))
    )
    (net (code "18") (name "Net-(U$695-1)") (class "Default")
      (node (ref "HELLO4") (pin "POS") (pinfunction "POS_POS") (pintype "passive"))
      (node (ref "U$695") (pin "P$3") (pinfunction "1_P$3") (pintype "passive"))
    )
    (net (code "19") (name "Net-(U$837-1)") (class "Default")
      (node (ref "POWER5") (pin "POS") (pinfunction "POS_POS") (pintype "passive"))
      (node (ref "U$837") (pin "P$3") (pinfunction "1_P$3") (pintype "passive"))
    )
    (net (code "20") (name "Net-(U$838-1)") (class "Default")
      (node (ref "HELLO5") (pin "POS") (pinfunction "POS_POS") (pintype "passive"))
      (node (ref "U$838") (pin "P$3") (pinfunction "1_P$3") (pintype "passive"))
    )
    (net (code "21") (name "unconnected-(U$1-P-PadP$1)") (class "Default")
      (node (ref "U$1") (pin "P$1") (pinfunction "P_P$1") (pintype "passive"))
    )
    (net (code "22") (name "unconnected-(U$2-P-PadP$1)") (class "Default")
      (node (ref "U$2") (pin "P$1") (pinfunction "P_P$1") (pintype "passive"))
    )
    (net (code "23") (name "unconnected-(U$3-P-PadP$1)") (class "Default")
      (node (ref "U$3") (pin "P$1") (pinfunction "P_P$1") (pintype "passive"))
    )
    (net (code "24") (name "unconnected-(U$4-P-PadP$1)") (class "Default")
      (node (ref "U$4") (pin "P$1") (pinfunction "P_P$1") (pintype "passive"))
    )
    (net (code "25") (name "unconnected-(U$5-P-PadP$1)") (class "Default")
      (node (ref "U$5") (pin "P$1") (pinfunction "P_P$1") (pintype "passive"))
    )
    (net (code "26") (name "unconnected-(U$6-P-PadP$1)") (class "Default")
      (node (ref "U$6") (pin "P$1") (pinfunction "P_P$1") (pintype "passive"))
    )
    (net (code "27") (name "unconnected-(U$7-P-PadP$1)") (class "Default")
      (node (ref "U$7") (pin "P$1") (pinfunction "P_P$1") (pintype "passive"))
    )
    (net (code "28") (name "unconnected-(U$8-P-PadP$1)") (class "Default")
      (node (ref "U$8") (pin "P$1") (pinfunction "P_P$1") (pintype "passive"))
    )
    (net (code "29") (name "unconnected-(U$9-P-PadP$1)") (class "Default")
      (node (ref "U$9") (pin "P$1") (pinfunction "P_P$1") (pintype "passive"))
    )
    (net (code "30") (name "unconnected-(U$10-P-PadP$1)") (class "Default")
      (node (ref "U$10") (pin "P$1") (pinfunction "P_P$1") (pintype "passive"))
    )
    (net (code "31") (name "unconnected-(U$11-P-PadP$1)") (class "Default")
      (node (ref "U$11") (pin "P$1") (pinfunction "P_P$1") (pintype "passive"))
    )
    (net (code "32") (name "unconnected-(U$12-P-PadP$1)") (class "Default")
      (node (ref "U$12") (pin "P$1") (pinfunction "P_P$1") (pintype "passive"))
    )
    (net (code "33") (name "unconnected-(U$13-P-PadP$1)") (class "Default")
      (node (ref "U$13") (pin "P$1") (pinfunction "P_P$1") (pintype "passive"))
    )
    (net (code "34") (name "unconnected-(U$14-P-PadP$1)") (class "Default")
      (node (ref "U$14") (pin "P$1") (pinfunction "P_P$1") (pintype "passive"))
    )
    (net (code "35") (name "unconnected-(U$15-P-PadP$1)") (class "Default")
      (node (ref "U$15") (pin "P$1") (pinfunction "P_P$1") (pintype "passive"))
    )
    (net (code "36") (name "unconnected-(U$16-P-PadP$1)") (class "Default")
      (node (ref "U$16") (pin "P$1") (pinfunction "P_P$1") (pintype "passive"))
    )
    (net (code "37") (name "unconnected-(U$17-P-PadP$1)") (class "Default")
      (node (ref "U$17") (pin "P$1") (pinfunction "P_P$1") (pintype "passive"))
    )
    (net (code "38") (name "unconnected-(U$18-P-PadP$1)") (class "Default")
      (node (ref "U$18") (pin "P$1") (pinfunction "P_P$1") (pintype "passive"))
    )
    (net (code "39") (name "unconnected-(U$19-P-PadP$1)") (class "Default")
      (node (ref "U$19") (pin "P$1") (pinfunction "P_P$1") (pintype "passive"))
    )
    (net (code "40") (name "unconnected-(U$20-P-PadP$1)") (class "Default")
      (node (ref "U$20") (pin "P$1") (pinfunction "P_P$1") (pintype "passive"))
    )
    (net (code "41") (name "unconnected-(U$21-P-PadP$1)") (class "Default")
      (node (ref "U$21") (pin "P$1") (pinfunction "P_P$1") (pintype "passive"))
    )
    (net (code "42") (name "unconnected-(U$22-P-PadP$1)") (class "Default")
      (node (ref "U$22") (pin "P$1") (pinfunction "P_P$1") (pintype "passive"))
    )
    (net (code "43") (name "unconnected-(U$23-P-PadP$1)") (class "Default")
      (node (ref "U$23") (pin "P$1") (pinfunction "P_P$1") (pintype "passive"))
    )
    (net (code "44") (name "unconnected-(U$24-P-PadP$1)") (class "Default")
      (node (ref "U$24") (pin "P$1") (pinfunction "P_P$1") (pintype "passive"))
    )
    (net (code "45") (name "unconnected-(U$25-P-PadP$1)") (class "Default")
      (node (ref "U$25") (pin "P$1") (pinfunction "P_P$1") (pintype "passive"))
    )
    (net (code "46") (name "unconnected-(U$26-P-PadP$1)") (class "Default")
      (node (ref "U$26") (pin "P$1") (pinfunction "P_P$1") (pintype "passive"))
    )
    (net (code "47") (name "unconnected-(U$27-P-PadP$1)") (class "Default")
      (node (ref "U$27") (pin "P$1") (pinfunction "P_P$1") (pintype "passive"))
    )
    (net (code "48") (name "unconnected-(U$28-P-PadP$1)") (class "Default")
      (node (ref "U$28") (pin "P$1") (pinfunction "P_P$1") (pintype "passive"))
    )
    (net (code "49") (name "unconnected-(U$29-P-PadP$1)") (class "Default")
      (node (ref "U$29") (pin "P$1") (pinfunction "P_P$1") (pintype "passive"))
    )
    (net (code "50") (name "unconnected-(U$30-P-PadP$1)") (class "Default")
      (node (ref "U$30") (pin "P$1") (pinfunction "P_P$1") (pintype "passive"))
    )
    (net (code "51") (name "unconnected-(U$31-P-PadP$1)") (class "Default")
      (node (ref "U$31") (pin "P$1") (pinfunction "P_P$1") (pintype "passive"))
    )
    (net (code "52") (name "unconnected-(U$32-P-PadP$1)") (class "Default")
      (node (ref "U$32") (pin "P$1") (pinfunction "P_P$1") (pintype "passive"))
    )
    (net (code "53") (name "unconnected-(U$33-P-PadP$1)") (class "Default")
      (node (ref "U$33") (pin "P$1") (pinfunction "P_P$1") (pintype "passive"))
    )
    (net (code "54") (name "unconnected-(U$34-P-PadP$1)") (class "Default")
      (node (ref "U$34") (pin "P$1") (pinfunction "P_P$1") (pintype "passive"))
    )
    (net (code "55") (name "unconnected-(U$35-P-PadP$1)") (class "Default")
      (node (ref "U$35") (pin "P$1") (pinfunction "P_P$1") (pintype "passive"))
    )
    (net (code "56") (name "unconnected-(U$36-P-PadP$1)") (class "Default")
      (node (ref "U$36") (pin "P$1") (pinfunction "P_P$1") (pintype "passive"))
    )
    (net (code "57") (name "unconnected-(U$37-P-PadP$1)") (class "Default")
      (node (ref "U$37") (pin "P$1") (pinfunction "P_P$1") (pintype "passive"))
    )
    (net (code "58") (name "unconnected-(U$38-P-PadP$1)") (class "Default")
      (node (ref "U$38") (pin "P$1") (pinfunction "P_P$1") (pintype "passive"))
    )
    (net (code "59") (name "unconnected-(U$39-P-PadP$1)") (class "Default")
      (node (ref "U$39") (pin "P$1") (pinfunction "P_P$1") (pintype "passive"))
    )
    (net (code "60") (name "unconnected-(U$40-P-PadP$1)") (class "Default")
      (node (ref "U$40") (pin "P$1") (pinfunction "P_P$1") (pintype "passive"))
    )
    (net (code "61") (name "unconnected-(U$41-P-PadP$1)") (class "Default")
      (node (ref "U$41") (pin "P$1") (pinfunction "P_P$1") (pintype "passive"))
    )
    (net (code "62") (name "unconnected-(U$42-P-PadP$1)") (class "Default")
      (node (ref "U$42") (pin "P$1") (pinfunction "P_P$1") (pintype "passive"))
    )
    (net (code "63") (name "unconnected-(U$43-P-PadP$1)") (class "Default")
      (node (ref "U$43") (pin "P$1") (pinfunction "P_P$1") (pintype "passive"))
    )
    (net (code "64") (name "unconnected-(U$44-P-PadP$1)") (class "Default")
      (node (ref "U$44") (pin "P$1") (pinfunction "P_P$1") (pintype "passive"))
    )
    (net (code "65") (name "unconnected-(U$45-P-PadP$1)") (class "Default")
      (node (ref "U$45") (pin "P$1") (pinfunction "P_P$1") (pintype "passive"))
    )
    (net (code "66") (name "unconnected-(U$46-P-PadP$1)") (class "Default")
      (node (ref "U$46") (pin "P$1") (pinfunction "P_P$1") (pintype "passive"))
    )
    (net (code "67") (name "unconnected-(U$47-P-PadP$1)") (class "Default")
      (node (ref "U$47") (pin "P$1") (pinfunction "P_P$1") (pintype "passive"))
    )
    (net (code "68") (name "unconnected-(U$48-P-PadP$1)") (class "Default")
      (node (ref "U$48") (pin "P$1") (pinfunction "P_P$1") (pintype "passive"))
    )
    (net (code "69") (name "unconnected-(U$49-P-PadP$1)") (class "Default")
      (node (ref "U$49") (pin "P$1") (pinfunction "P_P$1") (pintype "passive"))
    )
    (net (code "70") (name "unconnected-(U$50-P-PadP$1)") (class "Default")
      (node (ref "U$50") (pin "P$1") (pinfunction "P_P$1") (pintype "passive"))
    )
    (net (code "71") (name "unconnected-(U$51-P-PadP$1)") (class "Default")
      (node (ref "U$51") (pin "P$1") (pinfunction "P_P$1") (pintype "passive"))
    )
    (net (code "72") (name "unconnected-(U$52-P-PadP$1)") (class "Default")
      (node (ref "U$52") (pin "P$1") (pinfunction "P_P$1") (pintype "passive"))
    )
    (net (code "73") (name "unconnected-(U$53-P-PadP$1)") (class "Default")
      (node (ref "U$53") (pin "P$1") (pinfunction "P_P$1") (pintype "passive"))
    )
    (net (code "74") (name "unconnected-(U$54-P-PadP$1)") (class "Default")
      (node (ref "U$54") (pin "P$1") (pinfunction "P_P$1") (pintype "passive"))
    )
    (net (code "75") (name "unconnected-(U$55-P-PadP$1)") (class "Default")
      (node (ref "U$55") (pin "P$1") (pinfunction "P_P$1") (pintype "passive"))
    )
    (net (code "76") (name "unconnected-(U$56-P-PadP$1)") (class "Default")
      (node (ref "U$56") (pin "P$1") (pinfunction "P_P$1") (pintype "passive"))
    )
    (net (code "77") (name "unconnected-(U$57-P-PadP$1)") (class "Default")
      (node (ref "U$57") (pin "P$1") (pinfunction "P_P$1") (pintype "passive"))
    )
    (net (code "78") (name "unconnected-(U$58-P-PadP$1)") (class "Default")
      (node (ref "U$58") (pin "P$1") (pinfunction "P_P$1") (pintype "passive"))
    )
    (net (code "79") (name "unconnected-(U$59-P-PadP$1)") (class "Default")
      (node (ref "U$59") (pin "P$1") (pinfunction "P_P$1") (pintype "passive"))
    )
    (net (code "80") (name "unconnected-(U$60-P-PadP$1)") (class "Default")
      (node (ref "U$60") (pin "P$1") (pinfunction "P_P$1") (pintype "passive"))
    )
    (net (code "81") (name "unconnected-(U$61-P-PadP$1)") (class "Default")
      (node (ref "U$61") (pin "P$1") (pinfunction "P_P$1") (pintype "passive"))
    )
    (net (code "82") (name "unconnected-(U$62-P-PadP$1)") (class "Default")
      (node (ref "U$62") (pin "P$1") (pinfunction "P_P$1") (pintype "passive"))
    )
    (net (code "83") (name "unconnected-(U$63-P-PadP$1)") (class "Default")
      (node (ref "U$63") (pin "P$1") (pinfunction "P_P$1") (pintype "passive"))
    )
    (net (code "84") (name "unconnected-(U$64-P-PadP$1)") (class "Default")
      (node (ref "U$64") (pin "P$1") (pinfunction "P_P$1") (pintype "passive"))
    )
    (net (code "85") (name "unconnected-(U$65-P-PadP$1)") (class "Default")
      (node (ref "U$65") (pin "P$1") (pinfunction "P_P$1") (pintype "passive"))
    )
    (net (code "86") (name "unconnected-(U$66-P-PadP$1)") (class "Default")
      (node (ref "U$66") (pin "P$1") (pinfunction "P_P$1") (pintype "passive"))
    )
    (net (code "87") (name "unconnected-(U$67-P-PadP$1)") (class "Default")
      (node (ref "U$67") (pin "P$1") (pinfunction "P_P$1") (pintype "passive"))
    )
    (net (code "88") (name "unconnected-(U$68-P-PadP$1)") (class "Default")
      (node (ref "U$68") (pin "P$1") (pinfunction "P_P$1") (pintype "passive"))
    )
    (net (code "89") (name "unconnected-(U$69-P-PadP$1)") (class "Default")
      (node (ref "U$69") (pin "P$1") (pinfunction "P_P$1") (pintype "passive"))
    )
    (net (code "90") (name "unconnected-(U$70-P-PadP$1)") (class "Default")
      (node (ref "U$70") (pin "P$1") (pinfunction "P_P$1") (pintype "passive"))
    )
    (net (code "91") (name "unconnected-(U$93-P-PadP$1)") (class "Default")
      (node (ref "U$93") (pin "P$1") (pinfunction "P_P$1") (pintype "passive"))
    )
    (net (code "92") (name "unconnected-(U$94-P-PadP$1)") (class "Default")
      (node (ref "U$94") (pin "P$1") (pinfunction "P_P$1") (pintype "passive"))
    )
    (net (code "93") (name "unconnected-(U$95-P-PadP$1)") (class "Default")
      (node (ref "U$95") (pin "P$1") (pinfunction "P_P$1") (pintype "passive"))
    )
    (net (code "94") (name "unconnected-(U$96-P-PadP$1)") (class "Default")
      (node (ref "U$96") (pin "P$1") (pinfunction "P_P$1") (pintype "passive"))
    )
    (net (code "95") (name "unconnected-(U$97-P-PadP$1)") (class "Default")
      (node (ref "U$97") (pin "P$1") (pinfunction "P_P$1") (pintype "passive"))
    )
    (net (code "96") (name "unconnected-(U$98-P-PadP$1)") (class "Default")
      (node (ref "U$98") (pin "P$1") (pinfunction "P_P$1") (pintype "passive"))
    )
    (net (code "97") (name "unconnected-(U$101-P-PadP$1)") (class "Default")
      (node (ref "U$101") (pin "P$1") (pinfunction "P_P$1") (pintype "passive"))
    )
    (net (code "98") (name "unconnected-(U$102-P-PadP$1)") (class "Default")
      (node (ref "U$102") (pin "P$1") (pinfunction "P_P$1") (pintype "passive"))
    )
    (net (code "99") (name "unconnected-(U$103-P-PadP$1)") (class "Default")
      (node (ref "U$103") (pin "P$1") (pinfunction "P_P$1") (pintype "passive"))
    )
    (net (code "100") (name "unconnected-(U$104-P-PadP$1)") (class "Default")
      (node (ref "U$104") (pin "P$1") (pinfunction "P_P$1") (pintype "passive"))
    )
    (net (code "101") (name "unconnected-(U$105-P-PadP$1)") (class "Default")
      (node (ref "U$105") (pin "P$1") (pinfunction "P_P$1") (pintype "passive"))
    )
    (net (code "102") (name "unconnected-(U$106-P-PadP$1)") (class "Default")
      (node (ref "U$106") (pin "P$1") (pinfunction "P_P$1") (pintype "passive"))
    )
    (net (code "103") (name "unconnected-(U$107-P-PadP$1)") (class "Default")
      (node (ref "U$107") (pin "P$1") (pinfunction "P_P$1") (pintype "passive"))
    )
    (net (code "104") (name "unconnected-(U$108-P-PadP$1)") (class "Default")
      (node (ref "U$108") (pin "P$1") (pinfunction "P_P$1") (pintype "passive"))
    )
    (net (code "105") (name "unconnected-(U$109-P-PadP$1)") (class "Default")
      (node (ref "U$109") (pin "P$1") (pinfunction "P_P$1") (pintype "passive"))
    )
    (net (code "106") (name "unconnected-(U$110-P-PadP$1)") (class "Default")
      (node (ref "U$110") (pin "P$1") (pinfunction "P_P$1") (pintype "passive"))
    )
    (net (code "107") (name "unconnected-(U$111-P-PadP$1)") (class "Default")
      (node (ref "U$111") (pin "P$1") (pinfunction "P_P$1") (pintype "passive"))
    )
    (net (code "108") (name "unconnected-(U$112-P-PadP$1)") (class "Default")
      (node (ref "U$112") (pin "P$1") (pinfunction "P_P$1") (pintype "passive"))
    )
    (net (code "109") (name "unconnected-(U$113-P-PadP$1)") (class "Default")
      (node (ref "U$113") (pin "P$1") (pinfunction "P_P$1") (pintype "passive"))
    )
    (net (code "110") (name "unconnected-(U$114-P-PadP$1)") (class "Default")
      (node (ref "U$114") (pin "P$1") (pinfunction "P_P$1") (pintype "passive"))
    )
    (net (code "111") (name "unconnected-(U$115-P-PadP$1)") (class "Default")
      (node (ref "U$115") (pin "P$1") (pinfunction "P_P$1") (pintype "passive"))
    )
    (net (code "112") (name "unconnected-(U$116-P-PadP$1)") (class "Default")
      (node (ref "U$116") (pin "P$1") (pinfunction "P_P$1") (pintype "passive"))
    )
    (net (code "113") (name "unconnected-(U$117-P-PadP$1)") (class "Default")
      (node (ref "U$117") (pin "P$1") (pinfunction "P_P$1") (pintype "passive"))
    )
    (net (code "114") (name "unconnected-(U$118-P-PadP$1)") (class "Default")
      (node (ref "U$118") (pin "P$1") (pinfunction "P_P$1") (pintype "passive"))
    )
    (net (code "115") (name "unconnected-(U$119-P-PadP$1)") (class "Default")
      (node (ref "U$119") (pin "P$1") (pinfunction "P_P$1") (pintype "passive"))
    )
    (net (code "116") (name "unconnected-(U$120-P-PadP$1)") (class "Default")
      (node (ref "U$120") (pin "P$1") (pinfunction "P_P$1") (pintype "passive"))
    )
    (net (code "117") (name "unconnected-(U$121-P-PadP$1)") (class "Default")
      (node (ref "U$121") (pin "P$1") (pinfunction "P_P$1") (pintype "passive"))
    )
    (net (code "118") (name "unconnected-(U$122-P-PadP$1)") (class "Default")
      (node (ref "U$122") (pin "P$1") (pinfunction "P_P$1") (pintype "passive"))
    )
    (net (code "119") (name "unconnected-(U$144-P-PadP$1)") (class "Default")
      (node (ref "U$144") (pin "P$1") (pinfunction "P_P$1") (pintype "passive"))
    )
    (net (code "120") (name "unconnected-(U$145-P-PadP$1)") (class "Default")
      (node (ref "U$145") (pin "P$1") (pinfunction "P_P$1") (pintype "passive"))
    )
    (net (code "121") (name "unconnected-(U$146-P-PadP$1)") (class "Default")
      (node (ref "U$146") (pin "P$1") (pinfunction "P_P$1") (pintype "passive"))
    )
    (net (code "122") (name "unconnected-(U$147-P-PadP$1)") (class "Default")
      (node (ref "U$147") (pin "P$1") (pinfunction "P_P$1") (pintype "passive"))
    )
    (net (code "123") (name "unconnected-(U$148-P-PadP$1)") (class "Default")
      (node (ref "U$148") (pin "P$1") (pinfunction "P_P$1") (pintype "passive"))
    )
    (net (code "124") (name "unconnected-(U$149-P-PadP$1)") (class "Default")
      (node (ref "U$149") (pin "P$1") (pinfunction "P_P$1") (pintype "passive"))
    )
    (net (code "125") (name "unconnected-(U$150-P-PadP$1)") (class "Default")
      (node (ref "U$150") (pin "P$1") (pinfunction "P_P$1") (pintype "passive"))
    )
    (net (code "126") (name "unconnected-(U$151-P-PadP$1)") (class "Default")
      (node (ref "U$151") (pin "P$1") (pinfunction "P_P$1") (pintype "passive"))
    )
    (net (code "127") (name "unconnected-(U$152-P-PadP$1)") (class "Default")
      (node (ref "U$152") (pin "P$1") (pinfunction "P_P$1") (pintype "passive"))
    )
    (net (code "128") (name "unconnected-(U$153-P-PadP$1)") (class "Default")
      (node (ref "U$153") (pin "P$1") (pinfunction "P_P$1") (pintype "passive"))
    )
    (net (code "129") (name "unconnected-(U$154-P-PadP$1)") (class "Default")
      (node (ref "U$154") (pin "P$1") (pinfunction "P_P$1") (pintype "passive"))
    )
    (net (code "130") (name "unconnected-(U$155-P-PadP$1)") (class "Default")
      (node (ref "U$155") (pin "P$1") (pinfunction "P_P$1") (pintype "passive"))
    )
    (net (code "131") (name "unconnected-(U$156-P-PadP$1)") (class "Default")
      (node (ref "U$156") (pin "P$1") (pinfunction "P_P$1") (pintype "passive"))
    )
    (net (code "132") (name "unconnected-(U$157-P-PadP$1)") (class "Default")
      (node (ref "U$157") (pin "P$1") (pinfunction "P_P$1") (pintype "passive"))
    )
    (net (code "133") (name "unconnected-(U$158-P-PadP$1)") (class "Default")
      (node (ref "U$158") (pin "P$1") (pinfunction "P_P$1") (pintype "passive"))
    )
    (net (code "134") (name "unconnected-(U$159-P-PadP$1)") (class "Default")
      (node (ref "U$159") (pin "P$1") (pinfunction "P_P$1") (pintype "passive"))
    )
    (net (code "135") (name "unconnected-(U$160-P-PadP$1)") (class "Default")
      (node (ref "U$160") (pin "P$1") (pinfunction "P_P$1") (pintype "passive"))
    )
    (net (code "136") (name "unconnected-(U$161-P-PadP$1)") (class "Default")
      (node (ref "U$161") (pin "P$1") (pinfunction "P_P$1") (pintype "passive"))
    )
    (net (code "137") (name "unconnected-(U$162-P-PadP$1)") (class "Default")
      (node (ref "U$162") (pin "P$1") (pinfunction "P_P$1") (pintype "passive"))
    )
    (net (code "138") (name "unconnected-(U$163-P-PadP$1)") (class "Default")
      (node (ref "U$163") (pin "P$1") (pinfunction "P_P$1") (pintype "passive"))
    )
    (net (code "139") (name "unconnected-(U$164-P-PadP$1)") (class "Default")
      (node (ref "U$164") (pin "P$1") (pinfunction "P_P$1") (pintype "passive"))
    )
    (net (code "140") (name "unconnected-(U$165-P-PadP$1)") (class "Default")
      (node (ref "U$165") (pin "P$1") (pinfunction "P_P$1") (pintype "passive"))
    )
    (net (code "141") (name "unconnected-(U$166-P-PadP$1)") (class "Default")
      (node (ref "U$166") (pin "P$1") (pinfunction "P_P$1") (pintype "passive"))
    )
    (net (code "142") (name "unconnected-(U$167-P-PadP$1)") (class "Default")
      (node (ref "U$167") (pin "P$1") (pinfunction "P_P$1") (pintype "passive"))
    )
    (net (code "143") (name "unconnected-(U$168-P-PadP$1)") (class "Default")
      (node (ref "U$168") (pin "P$1") (pinfunction "P_P$1") (pintype "passive"))
    )
    (net (code "144") (name "unconnected-(U$169-P-PadP$1)") (class "Default")
      (node (ref "U$169") (pin "P$1") (pinfunction "P_P$1") (pintype "passive"))
    )
    (net (code "145") (name "unconnected-(U$170-P-PadP$1)") (class "Default")
      (node (ref "U$170") (pin "P$1") (pinfunction "P_P$1") (pintype "passive"))
    )
    (net (code "146") (name "unconnected-(U$171-P-PadP$1)") (class "Default")
      (node (ref "U$171") (pin "P$1") (pinfunction "P_P$1") (pintype "passive"))
    )
    (net (code "147") (name "unconnected-(U$172-P-PadP$1)") (class "Default")
      (node (ref "U$172") (pin "P$1") (pinfunction "P_P$1") (pintype "passive"))
    )
    (net (code "148") (name "unconnected-(U$173-P-PadP$1)") (class "Default")
      (node (ref "U$173") (pin "P$1") (pinfunction "P_P$1") (pintype "passive"))
    )
    (net (code "149") (name "unconnected-(U$174-P-PadP$1)") (class "Default")
      (node (ref "U$174") (pin "P$1") (pinfunction "P_P$1") (pintype "passive"))
    )
    (net (code "150") (name "unconnected-(U$175-P-PadP$1)") (class "Default")
      (node (ref "U$175") (pin "P$1") (pinfunction "P_P$1") (pintype "passive"))
    )
    (net (code "151") (name "unconnected-(U$176-P-PadP$1)") (class "Default")
      (node (ref "U$176") (pin "P$1") (pinfunction "P_P$1") (pintype "passive"))
    )
    (net (code "152") (name "unconnected-(U$177-P-PadP$1)") (class "Default")
      (node (ref "U$177") (pin "P$1") (pinfunction "P_P$1") (pintype "passive"))
    )
    (net (code "153") (name "unconnected-(U$178-P-PadP$1)") (class "Default")
      (node (ref "U$178") (pin "P$1") (pinfunction "P_P$1") (pintype "passive"))
    )
    (net (code "154") (name "unconnected-(U$179-P-PadP$1)") (class "Default")
      (node (ref "U$179") (pin "P$1") (pinfunction "P_P$1") (pintype "passive"))
    )
    (net (code "155") (name "unconnected-(U$180-P-PadP$1)") (class "Default")
      (node (ref "U$180") (pin "P$1") (pinfunction "P_P$1") (pintype "passive"))
    )
    (net (code "156") (name "unconnected-(U$181-P-PadP$1)") (class "Default")
      (node (ref "U$181") (pin "P$1") (pinfunction "P_P$1") (pintype "passive"))
    )
    (net (code "157") (name "unconnected-(U$182-P-PadP$1)") (class "Default")
      (node (ref "U$182") (pin "P$1") (pinfunction "P_P$1") (pintype "passive"))
    )
    (net (code "158") (name "unconnected-(U$183-P-PadP$1)") (class "Default")
      (node (ref "U$183") (pin "P$1") (pinfunction "P_P$1") (pintype "passive"))
    )
    (net (code "159") (name "unconnected-(U$184-P-PadP$1)") (class "Default")
      (node (ref "U$184") (pin "P$1") (pinfunction "P_P$1") (pintype "passive"))
    )
    (net (code "160") (name "unconnected-(U$185-P-PadP$1)") (class "Default")
      (node (ref "U$185") (pin "P$1") (pinfunction "P_P$1") (pintype "passive"))
    )
    (net (code "161") (name "unconnected-(U$186-P-PadP$1)") (class "Default")
      (node (ref "U$186") (pin "P$1") (pinfunction "P_P$1") (pintype "passive"))
    )
    (net (code "162") (name "unconnected-(U$187-P-PadP$1)") (class "Default")
      (node (ref "U$187") (pin "P$1") (pinfunction "P_P$1") (pintype "passive"))
    )
    (net (code "163") (name "unconnected-(U$188-P-PadP$1)") (class "Default")
      (node (ref "U$188") (pin "P$1") (pinfunction "P_P$1") (pintype "passive"))
    )
    (net (code "164") (name "unconnected-(U$189-P-PadP$1)") (class "Default")
      (node (ref "U$189") (pin "P$1") (pinfunction "P_P$1") (pintype "passive"))
    )
    (net (code "165") (name "unconnected-(U$190-P-PadP$1)") (class "Default")
      (node (ref "U$190") (pin "P$1") (pinfunction "P_P$1") (pintype "passive"))
    )
    (net (code "166") (name "unconnected-(U$191-P-PadP$1)") (class "Default")
      (node (ref "U$191") (pin "P$1") (pinfunction "P_P$1") (pintype "passive"))
    )
    (net (code "167") (name "unconnected-(U$192-P-PadP$1)") (class "Default")
      (node (ref "U$192") (pin "P$1") (pinfunction "P_P$1") (pintype "passive"))
    )
    (net (code "168") (name "unconnected-(U$193-P-PadP$1)") (class "Default")
      (node (ref "U$193") (pin "P$1") (pinfunction "P_P$1") (pintype "passive"))
    )
    (net (code "169") (name "unconnected-(U$194-P-PadP$1)") (class "Default")
      (node (ref "U$194") (pin "P$1") (pinfunction "P_P$1") (pintype "passive"))
    )
    (net (code "170") (name "unconnected-(U$195-P-PadP$1)") (class "Default")
      (node (ref "U$195") (pin "P$1") (pinfunction "P_P$1") (pintype "passive"))
    )
    (net (code "171") (name "unconnected-(U$196-P-PadP$1)") (class "Default")
      (node (ref "U$196") (pin "P$1") (pinfunction "P_P$1") (pintype "passive"))
    )
    (net (code "172") (name "unconnected-(U$197-P-PadP$1)") (class "Default")
      (node (ref "U$197") (pin "P$1") (pinfunction "P_P$1") (pintype "passive"))
    )
    (net (code "173") (name "unconnected-(U$198-P-PadP$1)") (class "Default")
      (node (ref "U$198") (pin "P$1") (pinfunction "P_P$1") (pintype "passive"))
    )
    (net (code "174") (name "unconnected-(U$199-P-PadP$1)") (class "Default")
      (node (ref "U$199") (pin "P$1") (pinfunction "P_P$1") (pintype "passive"))
    )
    (net (code "175") (name "unconnected-(U$200-P-PadP$1)") (class "Default")
      (node (ref "U$200") (pin "P$1") (pinfunction "P_P$1") (pintype "passive"))
    )
    (net (code "176") (name "unconnected-(U$201-P-PadP$1)") (class "Default")
      (node (ref "U$201") (pin "P$1") (pinfunction "P_P$1") (pintype "passive"))
    )
    (net (code "177") (name "unconnected-(U$202-P-PadP$1)") (class "Default")
      (node (ref "U$202") (pin "P$1") (pinfunction "P_P$1") (pintype "passive"))
    )
    (net (code "178") (name "unconnected-(U$203-P-PadP$1)") (class "Default")
      (node (ref "U$203") (pin "P$1") (pinfunction "P_P$1") (pintype "passive"))
    )
    (net (code "179") (name "unconnected-(U$204-P-PadP$1)") (class "Default")
      (node (ref "U$204") (pin "P$1") (pinfunction "P_P$1") (pintype "passive"))
    )
    (net (code "180") (name "unconnected-(U$205-P-PadP$1)") (class "Default")
      (node (ref "U$205") (pin "P$1") (pinfunction "P_P$1") (pintype "passive"))
    )
    (net (code "181") (name "unconnected-(U$206-P-PadP$1)") (class "Default")
      (node (ref "U$206") (pin "P$1") (pinfunction "P_P$1") (pintype "passive"))
    )
    (net (code "182") (name "unconnected-(U$207-P-PadP$1)") (class "Default")
      (node (ref "U$207") (pin "P$1") (pinfunction "P_P$1") (pintype "passive"))
    )
    (net (code "183") (name "unconnected-(U$208-P-PadP$1)") (class "Default")
      (node (ref "U$208") (pin "P$1") (pinfunction "P_P$1") (pintype "passive"))
    )
    (net (code "184") (name "unconnected-(U$209-P-PadP$1)") (class "Default")
      (node (ref "U$209") (pin "P$1") (pinfunction "P_P$1") (pintype "passive"))
    )
    (net (code "185") (name "unconnected-(U$210-P-PadP$1)") (class "Default")
      (node (ref "U$210") (pin "P$1") (pinfunction "P_P$1") (pintype "passive"))
    )
    (net (code "186") (name "unconnected-(U$211-P-PadP$1)") (class "Default")
      (node (ref "U$211") (pin "P$1") (pinfunction "P_P$1") (pintype "passive"))
    )
    (net (code "187") (name "unconnected-(U$212-P-PadP$1)") (class "Default")
      (node (ref "U$212") (pin "P$1") (pinfunction "P_P$1") (pintype "passive"))
    )
    (net (code "188") (name "unconnected-(U$213-P-PadP$1)") (class "Default")
      (node (ref "U$213") (pin "P$1") (pinfunction "P_P$1") (pintype "passive"))
    )
    (net (code "189") (name "unconnected-(U$236-P-PadP$1)") (class "Default")
      (node (ref "U$236") (pin "P$1") (pinfunction "P_P$1") (pintype "passive"))
    )
    (net (code "190") (name "unconnected-(U$237-P-PadP$1)") (class "Default")
      (node (ref "U$237") (pin "P$1") (pinfunction "P_P$1") (pintype "passive"))
    )
    (net (code "191") (name "unconnected-(U$238-P-PadP$1)") (class "Default")
      (node (ref "U$238") (pin "P$1") (pinfunction "P_P$1") (pintype "passive"))
    )
    (net (code "192") (name "unconnected-(U$239-P-PadP$1)") (class "Default")
      (node (ref "U$239") (pin "P$1") (pinfunction "P_P$1") (pintype "passive"))
    )
    (net (code "193") (name "unconnected-(U$240-P-PadP$1)") (class "Default")
      (node (ref "U$240") (pin "P$1") (pinfunction "P_P$1") (pintype "passive"))
    )
    (net (code "194") (name "unconnected-(U$241-P-PadP$1)") (class "Default")
      (node (ref "U$241") (pin "P$1") (pinfunction "P_P$1") (pintype "passive"))
    )
    (net (code "195") (name "unconnected-(U$242-P-PadP$1)") (class "Default")
      (node (ref "U$242") (pin "P$1") (pinfunction "P_P$1") (pintype "passive"))
    )
    (net (code "196") (name "unconnected-(U$243-P-PadP$1)") (class "Default")
      (node (ref "U$243") (pin "P$1") (pinfunction "P_P$1") (pintype "passive"))
    )
    (net (code "197") (name "unconnected-(U$244-P-PadP$1)") (class "Default")
      (node (ref "U$244") (pin "P$1") (pinfunction "P_P$1") (pintype "passive"))
    )
    (net (code "198") (name "unconnected-(U$245-P-PadP$1)") (class "Default")
      (node (ref "U$245") (pin "P$1") (pinfunction "P_P$1") (pintype "passive"))
    )
    (net (code "199") (name "unconnected-(U$246-P-PadP$1)") (class "Default")
      (node (ref "U$246") (pin "P$1") (pinfunction "P_P$1") (pintype "passive"))
    )
    (net (code "200") (name "unconnected-(U$247-P-PadP$1)") (class "Default")
      (node (ref "U$247") (pin "P$1") (pinfunction "P_P$1") (pintype "passive"))
    )
    (net (code "201") (name "unconnected-(U$248-P-PadP$1)") (class "Default")
      (node (ref "U$248") (pin "P$1") (pinfunction "P_P$1") (pintype "passive"))
    )
    (net (code "202") (name "unconnected-(U$249-P-PadP$1)") (class "Default")
      (node (ref "U$249") (pin "P$1") (pinfunction "P_P$1") (pintype "passive"))
    )
    (net (code "203") (name "unconnected-(U$250-P-PadP$1)") (class "Default")
      (node (ref "U$250") (pin "P$1") (pinfunction "P_P$1") (pintype "passive"))
    )
    (net (code "204") (name "unconnected-(U$251-P-PadP$1)") (class "Default")
      (node (ref "U$251") (pin "P$1") (pinfunction "P_P$1") (pintype "passive"))
    )
    (net (code "205") (name "unconnected-(U$252-P-PadP$1)") (class "Default")
      (node (ref "U$252") (pin "P$1") (pinfunction "P_P$1") (pintype "passive"))
    )
    (net (code "206") (name "unconnected-(U$253-P-PadP$1)") (class "Default")
      (node (ref "U$253") (pin "P$1") (pinfunction "P_P$1") (pintype "passive"))
    )
    (net (code "207") (name "unconnected-(U$254-P-PadP$1)") (class "Default")
      (node (ref "U$254") (pin "P$1") (pinfunction "P_P$1") (pintype "passive"))
    )
    (net (code "208") (name "unconnected-(U$255-P-PadP$1)") (class "Default")
      (node (ref "U$255") (pin "P$1") (pinfunction "P_P$1") (pintype "passive"))
    )
    (net (code "209") (name "unconnected-(U$256-P-PadP$1)") (class "Default")
      (node (ref "U$256") (pin "P$1") (pinfunction "P_P$1") (pintype "passive"))
    )
    (net (code "210") (name "unconnected-(U$257-P-PadP$1)") (class "Default")
      (node (ref "U$257") (pin "P$1") (pinfunction "P_P$1") (pintype "passive"))
    )
    (net (code "211") (name "unconnected-(U$258-P-PadP$1)") (class "Default")
      (node (ref "U$258") (pin "P$1") (pinfunction "P_P$1") (pintype "passive"))
    )
    (net (code "212") (name "unconnected-(U$259-P-PadP$1)") (class "Default")
      (node (ref "U$259") (pin "P$1") (pinfunction "P_P$1") (pintype "passive"))
    )
    (net (code "213") (name "unconnected-(U$260-P-PadP$1)") (class "Default")
      (node (ref "U$260") (pin "P$1") (pinfunction "P_P$1") (pintype "passive"))
    )
    (net (code "214") (name "unconnected-(U$261-P-PadP$1)") (class "Default")
      (node (ref "U$261") (pin "P$1") (pinfunction "P_P$1") (pintype "passive"))
    )
    (net (code "215") (name "unconnected-(U$262-P-PadP$1)") (class "Default")
      (node (ref "U$262") (pin "P$1") (pinfunction "P_P$1") (pintype "passive"))
    )
    (net (code "216") (name "unconnected-(U$263-P-PadP$1)") (class "Default")
      (node (ref "U$263") (pin "P$1") (pinfunction "P_P$1") (pintype "passive"))
    )
    (net (code "217") (name "unconnected-(U$287-P-PadP$1)") (class "Default")
      (node (ref "U$287") (pin "P$1") (pinfunction "P_P$1") (pintype "passive"))
    )
    (net (code "218") (name "unconnected-(U$288-P-PadP$1)") (class "Default")
      (node (ref "U$288") (pin "P$1") (pinfunction "P_P$1") (pintype "passive"))
    )
    (net (code "219") (name "unconnected-(U$289-P-PadP$1)") (class "Default")
      (node (ref "U$289") (pin "P$1") (pinfunction "P_P$1") (pintype "passive"))
    )
    (net (code "220") (name "unconnected-(U$290-P-PadP$1)") (class "Default")
      (node (ref "U$290") (pin "P$1") (pinfunction "P_P$1") (pintype "passive"))
    )
    (net (code "221") (name "unconnected-(U$291-P-PadP$1)") (class "Default")
      (node (ref "U$291") (pin "P$1") (pinfunction "P_P$1") (pintype "passive"))
    )
    (net (code "222") (name "unconnected-(U$292-P-PadP$1)") (class "Default")
      (node (ref "U$292") (pin "P$1") (pinfunction "P_P$1") (pintype "passive"))
    )
    (net (code "223") (name "unconnected-(U$293-P-PadP$1)") (class "Default")
      (node (ref "U$293") (pin "P$1") (pinfunction "P_P$1") (pintype "passive"))
    )
    (net (code "224") (name "unconnected-(U$294-P-PadP$1)") (class "Default")
      (node (ref "U$294") (pin "P$1") (pinfunction "P_P$1") (pintype "passive"))
    )
    (net (code "225") (name "unconnected-(U$295-P-PadP$1)") (class "Default")
      (node (ref "U$295") (pin "P$1") (pinfunction "P_P$1") (pintype "passive"))
    )
    (net (code "226") (name "unconnected-(U$296-P-PadP$1)") (class "Default")
      (node (ref "U$296") (pin "P$1") (pinfunction "P_P$1") (pintype "passive"))
    )
    (net (code "227") (name "unconnected-(U$297-P-PadP$1)") (class "Default")
      (node (ref "U$297") (pin "P$1") (pinfunction "P_P$1") (pintype "passive"))
    )
    (net (code "228") (name "unconnected-(U$298-P-PadP$1)") (class "Default")
      (node (ref "U$298") (pin "P$1") (pinfunction "P_P$1") (pintype "passive"))
    )
    (net (code "229") (name "unconnected-(U$299-P-PadP$1)") (class "Default")
      (node (ref "U$299") (pin "P$1") (pinfunction "P_P$1") (pintype "passive"))
    )
    (net (code "230") (name "unconnected-(U$300-P-PadP$1)") (class "Default")
      (node (ref "U$300") (pin "P$1") (pinfunction "P_P$1") (pintype "passive"))
    )
    (net (code "231") (name "unconnected-(U$301-P-PadP$1)") (class "Default")
      (node (ref "U$301") (pin "P$1") (pinfunction "P_P$1") (pintype "passive"))
    )
    (net (code "232") (name "unconnected-(U$302-P-PadP$1)") (class "Default")
      (node (ref "U$302") (pin "P$1") (pinfunction "P_P$1") (pintype "passive"))
    )
    (net (code "233") (name "unconnected-(U$303-P-PadP$1)") (class "Default")
      (node (ref "U$303") (pin "P$1") (pinfunction "P_P$1") (pintype "passive"))
    )
    (net (code "234") (name "unconnected-(U$304-P-PadP$1)") (class "Default")
      (node (ref "U$304") (pin "P$1") (pinfunction "P_P$1") (pintype "passive"))
    )
    (net (code "235") (name "unconnected-(U$305-P-PadP$1)") (class "Default")
      (node (ref "U$305") (pin "P$1") (pinfunction "P_P$1") (pintype "passive"))
    )
    (net (code "236") (name "unconnected-(U$306-P-PadP$1)") (class "Default")
      (node (ref "U$306") (pin "P$1") (pinfunction "P_P$1") (pintype "passive"))
    )
    (net (code "237") (name "unconnected-(U$307-P-PadP$1)") (class "Default")
      (node (ref "U$307") (pin "P$1") (pinfunction "P_P$1") (pintype "passive"))
    )
    (net (code "238") (name "unconnected-(U$308-P-PadP$1)") (class "Default")
      (node (ref "U$308") (pin "P$1") (pinfunction "P_P$1") (pintype "passive"))
    )
    (net (code "239") (name "unconnected-(U$309-P-PadP$1)") (class "Default")
      (node (ref "U$309") (pin "P$1") (pinfunction "P_P$1") (pintype "passive"))
    )
    (net (code "240") (name "unconnected-(U$310-P-PadP$1)") (class "Default")
      (node (ref "U$310") (pin "P$1") (pinfunction "P_P$1") (pintype "passive"))
    )
    (net (code "241") (name "unconnected-(U$311-P-PadP$1)") (class "Default")
      (node (ref "U$311") (pin "P$1") (pinfunction "P_P$1") (pintype "passive"))
    )
    (net (code "242") (name "unconnected-(U$312-P-PadP$1)") (class "Default")
      (node (ref "U$312") (pin "P$1") (pinfunction "P_P$1") (pintype "passive"))
    )
    (net (code "243") (name "unconnected-(U$313-P-PadP$1)") (class "Default")
      (node (ref "U$313") (pin "P$1") (pinfunction "P_P$1") (pintype "passive"))
    )
    (net (code "244") (name "unconnected-(U$314-P-PadP$1)") (class "Default")
      (node (ref "U$314") (pin "P$1") (pinfunction "P_P$1") (pintype "passive"))
    )
    (net (code "245") (name "unconnected-(U$315-P-PadP$1)") (class "Default")
      (node (ref "U$315") (pin "P$1") (pinfunction "P_P$1") (pintype "passive"))
    )
    (net (code "246") (name "unconnected-(U$316-P-PadP$1)") (class "Default")
      (node (ref "U$316") (pin "P$1") (pinfunction "P_P$1") (pintype "passive"))
    )
    (net (code "247") (name "unconnected-(U$317-P-PadP$1)") (class "Default")
      (node (ref "U$317") (pin "P$1") (pinfunction "P_P$1") (pintype "passive"))
    )
    (net (code "248") (name "unconnected-(U$318-P-PadP$1)") (class "Default")
      (node (ref "U$318") (pin "P$1") (pinfunction "P_P$1") (pintype "passive"))
    )
    (net (code "249") (name "unconnected-(U$319-P-PadP$1)") (class "Default")
      (node (ref "U$319") (pin "P$1") (pinfunction "P_P$1") (pintype "passive"))
    )
    (net (code "250") (name "unconnected-(U$320-P-PadP$1)") (class "Default")
      (node (ref "U$320") (pin "P$1") (pinfunction "P_P$1") (pintype "passive"))
    )
    (net (code "251") (name "unconnected-(U$321-P-PadP$1)") (class "Default")
      (node (ref "U$321") (pin "P$1") (pinfunction "P_P$1") (pintype "passive"))
    )
    (net (code "252") (name "unconnected-(U$322-P-PadP$1)") (class "Default")
      (node (ref "U$322") (pin "P$1") (pinfunction "P_P$1") (pintype "passive"))
    )
    (net (code "253") (name "unconnected-(U$323-P-PadP$1)") (class "Default")
      (node (ref "U$323") (pin "P$1") (pinfunction "P_P$1") (pintype "passive"))
    )
    (net (code "254") (name "unconnected-(U$324-P-PadP$1)") (class "Default")
      (node (ref "U$324") (pin "P$1") (pinfunction "P_P$1") (pintype "passive"))
    )
    (net (code "255") (name "unconnected-(U$325-P-PadP$1)") (class "Default")
      (node (ref "U$325") (pin "P$1") (pinfunction "P_P$1") (pintype "passive"))
    )
    (net (code "256") (name "unconnected-(U$326-P-PadP$1)") (class "Default")
      (node (ref "U$326") (pin "P$1") (pinfunction "P_P$1") (pintype "passive"))
    )
    (net (code "257") (name "unconnected-(U$327-P-PadP$1)") (class "Default")
      (node (ref "U$327") (pin "P$1") (pinfunction "P_P$1") (pintype "passive"))
    )
    (net (code "258") (name "unconnected-(U$328-P-PadP$1)") (class "Default")
      (node (ref "U$328") (pin "P$1") (pinfunction "P_P$1") (pintype "passive"))
    )
    (net (code "259") (name "unconnected-(U$329-P-PadP$1)") (class "Default")
      (node (ref "U$329") (pin "P$1") (pinfunction "P_P$1") (pintype "passive"))
    )
    (net (code "260") (name "unconnected-(U$330-P-PadP$1)") (class "Default")
      (node (ref "U$330") (pin "P$1") (pinfunction "P_P$1") (pintype "passive"))
    )
    (net (code "261") (name "unconnected-(U$331-P-PadP$1)") (class "Default")
      (node (ref "U$331") (pin "P$1") (pinfunction "P_P$1") (pintype "passive"))
    )
    (net (code "262") (name "unconnected-(U$332-P-PadP$1)") (class "Default")
      (node (ref "U$332") (pin "P$1") (pinfunction "P_P$1") (pintype "passive"))
    )
    (net (code "263") (name "unconnected-(U$333-P-PadP$1)") (class "Default")
      (node (ref "U$333") (pin "P$1") (pinfunction "P_P$1") (pintype "passive"))
    )
    (net (code "264") (name "unconnected-(U$334-P-PadP$1)") (class "Default")
      (node (ref "U$334") (pin "P$1") (pinfunction "P_P$1") (pintype "passive"))
    )
    (net (code "265") (name "unconnected-(U$335-P-PadP$1)") (class "Default")
      (node (ref "U$335") (pin "P$1") (pinfunction "P_P$1") (pintype "passive"))
    )
    (net (code "266") (name "unconnected-(U$336-P-PadP$1)") (class "Default")
      (node (ref "U$336") (pin "P$1") (pinfunction "P_P$1") (pintype "passive"))
    )
    (net (code "267") (name "unconnected-(U$337-P-PadP$1)") (class "Default")
      (node (ref "U$337") (pin "P$1") (pinfunction "P_P$1") (pintype "passive"))
    )
    (net (code "268") (name "unconnected-(U$338-P-PadP$1)") (class "Default")
      (node (ref "U$338") (pin "P$1") (pinfunction "P_P$1") (pintype "passive"))
    )
    (net (code "269") (name "unconnected-(U$339-P-PadP$1)") (class "Default")
      (node (ref "U$339") (pin "P$1") (pinfunction "P_P$1") (pintype "passive"))
    )
    (net (code "270") (name "unconnected-(U$340-P-PadP$1)") (class "Default")
      (node (ref "U$340") (pin "P$1") (pinfunction "P_P$1") (pintype "passive"))
    )
    (net (code "271") (name "unconnected-(U$341-P-PadP$1)") (class "Default")
      (node (ref "U$341") (pin "P$1") (pinfunction "P_P$1") (pintype "passive"))
    )
    (net (code "272") (name "unconnected-(U$342-P-PadP$1)") (class "Default")
      (node (ref "U$342") (pin "P$1") (pinfunction "P_P$1") (pintype "passive"))
    )
    (net (code "273") (name "unconnected-(U$343-P-PadP$1)") (class "Default")
      (node (ref "U$343") (pin "P$1") (pinfunction "P_P$1") (pintype "passive"))
    )
    (net (code "274") (name "unconnected-(U$344-P-PadP$1)") (class "Default")
      (node (ref "U$344") (pin "P$1") (pinfunction "P_P$1") (pintype "passive"))
    )
    (net (code "275") (name "unconnected-(U$345-P-PadP$1)") (class "Default")
      (node (ref "U$345") (pin "P$1") (pinfunction "P_P$1") (pintype "passive"))
    )
    (net (code "276") (name "unconnected-(U$346-P-PadP$1)") (class "Default")
      (node (ref "U$346") (pin "P$1") (pinfunction "P_P$1") (pintype "passive"))
    )
    (net (code "277") (name "unconnected-(U$347-P-PadP$1)") (class "Default")
      (node (ref "U$347") (pin "P$1") (pinfunction "P_P$1") (pintype "passive"))
    )
    (net (code "278") (name "unconnected-(U$348-P-PadP$1)") (class "Default")
      (node (ref "U$348") (pin "P$1") (pinfunction "P_P$1") (pintype "passive"))
    )
    (net (code "279") (name "unconnected-(U$349-P-PadP$1)") (class "Default")
      (node (ref "U$349") (pin "P$1") (pinfunction "P_P$1") (pintype "passive"))
    )
    (net (code "280") (name "unconnected-(U$350-P-PadP$1)") (class "Default")
      (node (ref "U$350") (pin "P$1") (pinfunction "P_P$1") (pintype "passive"))
    )
    (net (code "281") (name "unconnected-(U$351-P-PadP$1)") (class "Default")
      (node (ref "U$351") (pin "P$1") (pinfunction "P_P$1") (pintype "passive"))
    )
    (net (code "282") (name "unconnected-(U$352-P-PadP$1)") (class "Default")
      (node (ref "U$352") (pin "P$1") (pinfunction "P_P$1") (pintype "passive"))
    )
    (net (code "283") (name "unconnected-(U$353-P-PadP$1)") (class "Default")
      (node (ref "U$353") (pin "P$1") (pinfunction "P_P$1") (pintype "passive"))
    )
    (net (code "284") (name "unconnected-(U$354-P-PadP$1)") (class "Default")
      (node (ref "U$354") (pin "P$1") (pinfunction "P_P$1") (pintype "passive"))
    )
    (net (code "285") (name "unconnected-(U$355-P-PadP$1)") (class "Default")
      (node (ref "U$355") (pin "P$1") (pinfunction "P_P$1") (pintype "passive"))
    )
    (net (code "286") (name "unconnected-(U$356-P-PadP$1)") (class "Default")
      (node (ref "U$356") (pin "P$1") (pinfunction "P_P$1") (pintype "passive"))
    )
    (net (code "287") (name "unconnected-(U$379-P-PadP$1)") (class "Default")
      (node (ref "U$379") (pin "P$1") (pinfunction "P_P$1") (pintype "passive"))
    )
    (net (code "288") (name "unconnected-(U$380-P-PadP$1)") (class "Default")
      (node (ref "U$380") (pin "P$1") (pinfunction "P_P$1") (pintype "passive"))
    )
    (net (code "289") (name "unconnected-(U$381-P-PadP$1)") (class "Default")
      (node (ref "U$381") (pin "P$1") (pinfunction "P_P$1") (pintype "passive"))
    )
    (net (code "290") (name "unconnected-(U$382-P-PadP$1)") (class "Default")
      (node (ref "U$382") (pin "P$1") (pinfunction "P_P$1") (pintype "passive"))
    )
    (net (code "291") (name "unconnected-(U$383-P-PadP$1)") (class "Default")
      (node (ref "U$383") (pin "P$1") (pinfunction "P_P$1") (pintype "passive"))
    )
    (net (code "292") (name "unconnected-(U$384-P-PadP$1)") (class "Default")
      (node (ref "U$384") (pin "P$1") (pinfunction "P_P$1") (pintype "passive"))
    )
    (net (code "293") (name "unconnected-(U$385-P-PadP$1)") (class "Default")
      (node (ref "U$385") (pin "P$1") (pinfunction "P_P$1") (pintype "passive"))
    )
    (net (code "294") (name "unconnected-(U$386-P-PadP$1)") (class "Default")
      (node (ref "U$386") (pin "P$1") (pinfunction "P_P$1") (pintype "passive"))
    )
    (net (code "295") (name "unconnected-(U$387-P-PadP$1)") (class "Default")
      (node (ref "U$387") (pin "P$1") (pinfunction "P_P$1") (pintype "passive"))
    )
    (net (code "296") (name "unconnected-(U$388-P-PadP$1)") (class "Default")
      (node (ref "U$388") (pin "P$1") (pinfunction "P_P$1") (pintype "passive"))
    )
    (net (code "297") (name "unconnected-(U$389-P-PadP$1)") (class "Default")
      (node (ref "U$389") (pin "P$1") (pinfunction "P_P$1") (pintype "passive"))
    )
    (net (code "298") (name "unconnected-(U$390-P-PadP$1)") (class "Default")
      (node (ref "U$390") (pin "P$1") (pinfunction "P_P$1") (pintype "passive"))
    )
    (net (code "299") (name "unconnected-(U$391-P-PadP$1)") (class "Default")
      (node (ref "U$391") (pin "P$1") (pinfunction "P_P$1") (pintype "passive"))
    )
    (net (code "300") (name "unconnected-(U$392-P-PadP$1)") (class "Default")
      (node (ref "U$392") (pin "P$1") (pinfunction "P_P$1") (pintype "passive"))
    )
    (net (code "301") (name "unconnected-(U$393-P-PadP$1)") (class "Default")
      (node (ref "U$393") (pin "P$1") (pinfunction "P_P$1") (pintype "passive"))
    )
    (net (code "302") (name "unconnected-(U$394-P-PadP$1)") (class "Default")
      (node (ref "U$394") (pin "P$1") (pinfunction "P_P$1") (pintype "passive"))
    )
    (net (code "303") (name "unconnected-(U$395-P-PadP$1)") (class "Default")
      (node (ref "U$395") (pin "P$1") (pinfunction "P_P$1") (pintype "passive"))
    )
    (net (code "304") (name "unconnected-(U$396-P-PadP$1)") (class "Default")
      (node (ref "U$396") (pin "P$1") (pinfunction "P_P$1") (pintype "passive"))
    )
    (net (code "305") (name "unconnected-(U$397-P-PadP$1)") (class "Default")
      (node (ref "U$397") (pin "P$1") (pinfunction "P_P$1") (pintype "passive"))
    )
    (net (code "306") (name "unconnected-(U$398-P-PadP$1)") (class "Default")
      (node (ref "U$398") (pin "P$1") (pinfunction "P_P$1") (pintype "passive"))
    )
    (net (code "307") (name "unconnected-(U$399-P-PadP$1)") (class "Default")
      (node (ref "U$399") (pin "P$1") (pinfunction "P_P$1") (pintype "passive"))
    )
    (net (code "308") (name "unconnected-(U$400-P-PadP$1)") (class "Default")
      (node (ref "U$400") (pin "P$1") (pinfunction "P_P$1") (pintype "passive"))
    )
    (net (code "309") (name "unconnected-(U$401-P-PadP$1)") (class "Default")
      (node (ref "U$401") (pin "P$1") (pinfunction "P_P$1") (pintype "passive"))
    )
    (net (code "310") (name "unconnected-(U$402-P-PadP$1)") (class "Default")
      (node (ref "U$402") (pin "P$1") (pinfunction "P_P$1") (pintype "passive"))
    )
    (net (code "311") (name "unconnected-(U$403-P-PadP$1)") (class "Default")
      (node (ref "U$403") (pin "P$1") (pinfunction "P_P$1") (pintype "passive"))
    )
    (net (code "312") (name "unconnected-(U$404-P-PadP$1)") (class "Default")
      (node (ref "U$404") (pin "P$1") (pinfunction "P_P$1") (pintype "passive"))
    )
    (net (code "313") (name "unconnected-(U$405-P-PadP$1)") (class "Default")
      (node (ref "U$405") (pin "P$1") (pinfunction "P_P$1") (pintype "passive"))
    )
    (net (code "314") (name "unconnected-(U$406-P-PadP$1)") (class "Default")
      (node (ref "U$406") (pin "P$1") (pinfunction "P_P$1") (pintype "passive"))
    )
    (net (code "315") (name "unconnected-(U$430-P-PadP$1)") (class "Default")
      (node (ref "U$430") (pin "P$1") (pinfunction "P_P$1") (pintype "passive"))
    )
    (net (code "316") (name "unconnected-(U$431-P-PadP$1)") (class "Default")
      (node (ref "U$431") (pin "P$1") (pinfunction "P_P$1") (pintype "passive"))
    )
    (net (code "317") (name "unconnected-(U$432-P-PadP$1)") (class "Default")
      (node (ref "U$432") (pin "P$1") (pinfunction "P_P$1") (pintype "passive"))
    )
    (net (code "318") (name "unconnected-(U$433-P-PadP$1)") (class "Default")
      (node (ref "U$433") (pin "P$1") (pinfunction "P_P$1") (pintype "passive"))
    )
    (net (code "319") (name "unconnected-(U$434-P-PadP$1)") (class "Default")
      (node (ref "U$434") (pin "P$1") (pinfunction "P_P$1") (pintype "passive"))
    )
    (net (code "320") (name "unconnected-(U$435-P-PadP$1)") (class "Default")
      (node (ref "U$435") (pin "P$1") (pinfunction "P_P$1") (pintype "passive"))
    )
    (net (code "321") (name "unconnected-(U$436-P-PadP$1)") (class "Default")
      (node (ref "U$436") (pin "P$1") (pinfunction "P_P$1") (pintype "passive"))
    )
    (net (code "322") (name "unconnected-(U$437-P-PadP$1)") (class "Default")
      (node (ref "U$437") (pin "P$1") (pinfunction "P_P$1") (pintype "passive"))
    )
    (net (code "323") (name "unconnected-(U$438-P-PadP$1)") (class "Default")
      (node (ref "U$438") (pin "P$1") (pinfunction "P_P$1") (pintype "passive"))
    )
    (net (code "324") (name "unconnected-(U$439-P-PadP$1)") (class "Default")
      (node (ref "U$439") (pin "P$1") (pinfunction "P_P$1") (pintype "passive"))
    )
    (net (code "325") (name "unconnected-(U$440-P-PadP$1)") (class "Default")
      (node (ref "U$440") (pin "P$1") (pinfunction "P_P$1") (pintype "passive"))
    )
    (net (code "326") (name "unconnected-(U$441-P-PadP$1)") (class "Default")
      (node (ref "U$441") (pin "P$1") (pinfunction "P_P$1") (pintype "passive"))
    )
    (net (code "327") (name "unconnected-(U$442-P-PadP$1)") (class "Default")
      (node (ref "U$442") (pin "P$1") (pinfunction "P_P$1") (pintype "passive"))
    )
    (net (code "328") (name "unconnected-(U$443-P-PadP$1)") (class "Default")
      (node (ref "U$443") (pin "P$1") (pinfunction "P_P$1") (pintype "passive"))
    )
    (net (code "329") (name "unconnected-(U$444-P-PadP$1)") (class "Default")
      (node (ref "U$444") (pin "P$1") (pinfunction "P_P$1") (pintype "passive"))
    )
    (net (code "330") (name "unconnected-(U$445-P-PadP$1)") (class "Default")
      (node (ref "U$445") (pin "P$1") (pinfunction "P_P$1") (pintype "passive"))
    )
    (net (code "331") (name "unconnected-(U$446-P-PadP$1)") (class "Default")
      (node (ref "U$446") (pin "P$1") (pinfunction "P_P$1") (pintype "passive"))
    )
    (net (code "332") (name "unconnected-(U$447-P-PadP$1)") (class "Default")
      (node (ref "U$447") (pin "P$1") (pinfunction "P_P$1") (pintype "passive"))
    )
    (net (code "333") (name "unconnected-(U$448-P-PadP$1)") (class "Default")
      (node (ref "U$448") (pin "P$1") (pinfunction "P_P$1") (pintype "passive"))
    )
    (net (code "334") (name "unconnected-(U$449-P-PadP$1)") (class "Default")
      (node (ref "U$449") (pin "P$1") (pinfunction "P_P$1") (pintype "passive"))
    )
    (net (code "335") (name "unconnected-(U$450-P-PadP$1)") (class "Default")
      (node (ref "U$450") (pin "P$1") (pinfunction "P_P$1") (pintype "passive"))
    )
    (net (code "336") (name "unconnected-(U$451-P-PadP$1)") (class "Default")
      (node (ref "U$451") (pin "P$1") (pinfunction "P_P$1") (pintype "passive"))
    )
    (net (code "337") (name "unconnected-(U$452-P-PadP$1)") (class "Default")
      (node (ref "U$452") (pin "P$1") (pinfunction "P_P$1") (pintype "passive"))
    )
    (net (code "338") (name "unconnected-(U$453-P-PadP$1)") (class "Default")
      (node (ref "U$453") (pin "P$1") (pinfunction "P_P$1") (pintype "passive"))
    )
    (net (code "339") (name "unconnected-(U$454-P-PadP$1)") (class "Default")
      (node (ref "U$454") (pin "P$1") (pinfunction "P_P$1") (pintype "passive"))
    )
    (net (code "340") (name "unconnected-(U$455-P-PadP$1)") (class "Default")
      (node (ref "U$455") (pin "P$1") (pinfunction "P_P$1") (pintype "passive"))
    )
    (net (code "341") (name "unconnected-(U$456-P-PadP$1)") (class "Default")
      (node (ref "U$456") (pin "P$1") (pinfunction "P_P$1") (pintype "passive"))
    )
    (net (code "342") (name "unconnected-(U$457-P-PadP$1)") (class "Default")
      (node (ref "U$457") (pin "P$1") (pinfunction "P_P$1") (pintype "passive"))
    )
    (net (code "343") (name "unconnected-(U$458-P-PadP$1)") (class "Default")
      (node (ref "U$458") (pin "P$1") (pinfunction "P_P$1") (pintype "passive"))
    )
    (net (code "344") (name "unconnected-(U$459-P-PadP$1)") (class "Default")
      (node (ref "U$459") (pin "P$1") (pinfunction "P_P$1") (pintype "passive"))
    )
    (net (code "345") (name "unconnected-(U$460-P-PadP$1)") (class "Default")
      (node (ref "U$460") (pin "P$1") (pinfunction "P_P$1") (pintype "passive"))
    )
    (net (code "346") (name "unconnected-(U$461-P-PadP$1)") (class "Default")
      (node (ref "U$461") (pin "P$1") (pinfunction "P_P$1") (pintype "passive"))
    )
    (net (code "347") (name "unconnected-(U$462-P-PadP$1)") (class "Default")
      (node (ref "U$462") (pin "P$1") (pinfunction "P_P$1") (pintype "passive"))
    )
    (net (code "348") (name "unconnected-(U$463-P-PadP$1)") (class "Default")
      (node (ref "U$463") (pin "P$1") (pinfunction "P_P$1") (pintype "passive"))
    )
    (net (code "349") (name "unconnected-(U$464-P-PadP$1)") (class "Default")
      (node (ref "U$464") (pin "P$1") (pinfunction "P_P$1") (pintype "passive"))
    )
    (net (code "350") (name "unconnected-(U$465-P-PadP$1)") (class "Default")
      (node (ref "U$465") (pin "P$1") (pinfunction "P_P$1") (pintype "passive"))
    )
    (net (code "351") (name "unconnected-(U$466-P-PadP$1)") (class "Default")
      (node (ref "U$466") (pin "P$1") (pinfunction "P_P$1") (pintype "passive"))
    )
    (net (code "352") (name "unconnected-(U$467-P-PadP$1)") (class "Default")
      (node (ref "U$467") (pin "P$1") (pinfunction "P_P$1") (pintype "passive"))
    )
    (net (code "353") (name "unconnected-(U$468-P-PadP$1)") (class "Default")
      (node (ref "U$468") (pin "P$1") (pinfunction "P_P$1") (pintype "passive"))
    )
    (net (code "354") (name "unconnected-(U$469-P-PadP$1)") (class "Default")
      (node (ref "U$469") (pin "P$1") (pinfunction "P_P$1") (pintype "passive"))
    )
    (net (code "355") (name "unconnected-(U$470-P-PadP$1)") (class "Default")
      (node (ref "U$470") (pin "P$1") (pinfunction "P_P$1") (pintype "passive"))
    )
    (net (code "356") (name "unconnected-(U$471-P-PadP$1)") (class "Default")
      (node (ref "U$471") (pin "P$1") (pinfunction "P_P$1") (pintype "passive"))
    )
    (net (code "357") (name "unconnected-(U$472-P-PadP$1)") (class "Default")
      (node (ref "U$472") (pin "P$1") (pinfunction "P_P$1") (pintype "passive"))
    )
    (net (code "358") (name "unconnected-(U$473-P-PadP$1)") (class "Default")
      (node (ref "U$473") (pin "P$1") (pinfunction "P_P$1") (pintype "passive"))
    )
    (net (code "359") (name "unconnected-(U$474-P-PadP$1)") (class "Default")
      (node (ref "U$474") (pin "P$1") (pinfunction "P_P$1") (pintype "passive"))
    )
    (net (code "360") (name "unconnected-(U$475-P-PadP$1)") (class "Default")
      (node (ref "U$475") (pin "P$1") (pinfunction "P_P$1") (pintype "passive"))
    )
    (net (code "361") (name "unconnected-(U$476-P-PadP$1)") (class "Default")
      (node (ref "U$476") (pin "P$1") (pinfunction "P_P$1") (pintype "passive"))
    )
    (net (code "362") (name "unconnected-(U$477-P-PadP$1)") (class "Default")
      (node (ref "U$477") (pin "P$1") (pinfunction "P_P$1") (pintype "passive"))
    )
    (net (code "363") (name "unconnected-(U$478-P-PadP$1)") (class "Default")
      (node (ref "U$478") (pin "P$1") (pinfunction "P_P$1") (pintype "passive"))
    )
    (net (code "364") (name "unconnected-(U$479-P-PadP$1)") (class "Default")
      (node (ref "U$479") (pin "P$1") (pinfunction "P_P$1") (pintype "passive"))
    )
    (net (code "365") (name "unconnected-(U$480-P-PadP$1)") (class "Default")
      (node (ref "U$480") (pin "P$1") (pinfunction "P_P$1") (pintype "passive"))
    )
    (net (code "366") (name "unconnected-(U$481-P-PadP$1)") (class "Default")
      (node (ref "U$481") (pin "P$1") (pinfunction "P_P$1") (pintype "passive"))
    )
    (net (code "367") (name "unconnected-(U$482-P-PadP$1)") (class "Default")
      (node (ref "U$482") (pin "P$1") (pinfunction "P_P$1") (pintype "passive"))
    )
    (net (code "368") (name "unconnected-(U$483-P-PadP$1)") (class "Default")
      (node (ref "U$483") (pin "P$1") (pinfunction "P_P$1") (pintype "passive"))
    )
    (net (code "369") (name "unconnected-(U$484-P-PadP$1)") (class "Default")
      (node (ref "U$484") (pin "P$1") (pinfunction "P_P$1") (pintype "passive"))
    )
    (net (code "370") (name "unconnected-(U$485-P-PadP$1)") (class "Default")
      (node (ref "U$485") (pin "P$1") (pinfunction "P_P$1") (pintype "passive"))
    )
    (net (code "371") (name "unconnected-(U$486-P-PadP$1)") (class "Default")
      (node (ref "U$486") (pin "P$1") (pinfunction "P_P$1") (pintype "passive"))
    )
    (net (code "372") (name "unconnected-(U$487-P-PadP$1)") (class "Default")
      (node (ref "U$487") (pin "P$1") (pinfunction "P_P$1") (pintype "passive"))
    )
    (net (code "373") (name "unconnected-(U$488-P-PadP$1)") (class "Default")
      (node (ref "U$488") (pin "P$1") (pinfunction "P_P$1") (pintype "passive"))
    )
    (net (code "374") (name "unconnected-(U$489-P-PadP$1)") (class "Default")
      (node (ref "U$489") (pin "P$1") (pinfunction "P_P$1") (pintype "passive"))
    )
    (net (code "375") (name "unconnected-(U$490-P-PadP$1)") (class "Default")
      (node (ref "U$490") (pin "P$1") (pinfunction "P_P$1") (pintype "passive"))
    )
    (net (code "376") (name "unconnected-(U$491-P-PadP$1)") (class "Default")
      (node (ref "U$491") (pin "P$1") (pinfunction "P_P$1") (pintype "passive"))
    )
    (net (code "377") (name "unconnected-(U$492-P-PadP$1)") (class "Default")
      (node (ref "U$492") (pin "P$1") (pinfunction "P_P$1") (pintype "passive"))
    )
    (net (code "378") (name "unconnected-(U$493-P-PadP$1)") (class "Default")
      (node (ref "U$493") (pin "P$1") (pinfunction "P_P$1") (pintype "passive"))
    )
    (net (code "379") (name "unconnected-(U$494-P-PadP$1)") (class "Default")
      (node (ref "U$494") (pin "P$1") (pinfunction "P_P$1") (pintype "passive"))
    )
    (net (code "380") (name "unconnected-(U$495-P-PadP$1)") (class "Default")
      (node (ref "U$495") (pin "P$1") (pinfunction "P_P$1") (pintype "passive"))
    )
    (net (code "381") (name "unconnected-(U$496-P-PadP$1)") (class "Default")
      (node (ref "U$496") (pin "P$1") (pinfunction "P_P$1") (pintype "passive"))
    )
    (net (code "382") (name "unconnected-(U$497-P-PadP$1)") (class "Default")
      (node (ref "U$497") (pin "P$1") (pinfunction "P_P$1") (pintype "passive"))
    )
    (net (code "383") (name "unconnected-(U$498-P-PadP$1)") (class "Default")
      (node (ref "U$498") (pin "P$1") (pinfunction "P_P$1") (pintype "passive"))
    )
    (net (code "384") (name "unconnected-(U$499-P-PadP$1)") (class "Default")
      (node (ref "U$499") (pin "P$1") (pinfunction "P_P$1") (pintype "passive"))
    )
    (net (code "385") (name "unconnected-(U$522-P-PadP$1)") (class "Default")
      (node (ref "U$522") (pin "P$1") (pinfunction "P_P$1") (pintype "passive"))
    )
    (net (code "386") (name "unconnected-(U$523-P-PadP$1)") (class "Default")
      (node (ref "U$523") (pin "P$1") (pinfunction "P_P$1") (pintype "passive"))
    )
    (net (code "387") (name "unconnected-(U$524-P-PadP$1)") (class "Default")
      (node (ref "U$524") (pin "P$1") (pinfunction "P_P$1") (pintype "passive"))
    )
    (net (code "388") (name "unconnected-(U$525-P-PadP$1)") (class "Default")
      (node (ref "U$525") (pin "P$1") (pinfunction "P_P$1") (pintype "passive"))
    )
    (net (code "389") (name "unconnected-(U$526-P-PadP$1)") (class "Default")
      (node (ref "U$526") (pin "P$1") (pinfunction "P_P$1") (pintype "passive"))
    )
    (net (code "390") (name "unconnected-(U$527-P-PadP$1)") (class "Default")
      (node (ref "U$527") (pin "P$1") (pinfunction "P_P$1") (pintype "passive"))
    )
    (net (code "391") (name "unconnected-(U$528-P-PadP$1)") (class "Default")
      (node (ref "U$528") (pin "P$1") (pinfunction "P_P$1") (pintype "passive"))
    )
    (net (code "392") (name "unconnected-(U$529-P-PadP$1)") (class "Default")
      (node (ref "U$529") (pin "P$1") (pinfunction "P_P$1") (pintype "passive"))
    )
    (net (code "393") (name "unconnected-(U$530-P-PadP$1)") (class "Default")
      (node (ref "U$530") (pin "P$1") (pinfunction "P_P$1") (pintype "passive"))
    )
    (net (code "394") (name "unconnected-(U$531-P-PadP$1)") (class "Default")
      (node (ref "U$531") (pin "P$1") (pinfunction "P_P$1") (pintype "passive"))
    )
    (net (code "395") (name "unconnected-(U$532-P-PadP$1)") (class "Default")
      (node (ref "U$532") (pin "P$1") (pinfunction "P_P$1") (pintype "passive"))
    )
    (net (code "396") (name "unconnected-(U$533-P-PadP$1)") (class "Default")
      (node (ref "U$533") (pin "P$1") (pinfunction "P_P$1") (pintype "passive"))
    )
    (net (code "397") (name "unconnected-(U$534-P-PadP$1)") (class "Default")
      (node (ref "U$534") (pin "P$1") (pinfunction "P_P$1") (pintype "passive"))
    )
    (net (code "398") (name "unconnected-(U$535-P-PadP$1)") (class "Default")
      (node (ref "U$535") (pin "P$1") (pinfunction "P_P$1") (pintype "passive"))
    )
    (net (code "399") (name "unconnected-(U$536-P-PadP$1)") (class "Default")
      (node (ref "U$536") (pin "P$1") (pinfunction "P_P$1") (pintype "passive"))
    )
    (net (code "400") (name "unconnected-(U$537-P-PadP$1)") (class "Default")
      (node (ref "U$537") (pin "P$1") (pinfunction "P_P$1") (pintype "passive"))
    )
    (net (code "401") (name "unconnected-(U$538-P-PadP$1)") (class "Default")
      (node (ref "U$538") (pin "P$1") (pinfunction "P_P$1") (pintype "passive"))
    )
    (net (code "402") (name "unconnected-(U$539-P-PadP$1)") (class "Default")
      (node (ref "U$539") (pin "P$1") (pinfunction "P_P$1") (pintype "passive"))
    )
    (net (code "403") (name "unconnected-(U$540-P-PadP$1)") (class "Default")
      (node (ref "U$540") (pin "P$1") (pinfunction "P_P$1") (pintype "passive"))
    )
    (net (code "404") (name "unconnected-(U$541-P-PadP$1)") (class "Default")
      (node (ref "U$541") (pin "P$1") (pinfunction "P_P$1") (pintype "passive"))
    )
    (net (code "405") (name "unconnected-(U$542-P-PadP$1)") (class "Default")
      (node (ref "U$542") (pin "P$1") (pinfunction "P_P$1") (pintype "passive"))
    )
    (net (code "406") (name "unconnected-(U$543-P-PadP$1)") (class "Default")
      (node (ref "U$543") (pin "P$1") (pinfunction "P_P$1") (pintype "passive"))
    )
    (net (code "407") (name "unconnected-(U$544-P-PadP$1)") (class "Default")
      (node (ref "U$544") (pin "P$1") (pinfunction "P_P$1") (pintype "passive"))
    )
    (net (code "408") (name "unconnected-(U$545-P-PadP$1)") (class "Default")
      (node (ref "U$545") (pin "P$1") (pinfunction "P_P$1") (pintype "passive"))
    )
    (net (code "409") (name "unconnected-(U$546-P-PadP$1)") (class "Default")
      (node (ref "U$546") (pin "P$1") (pinfunction "P_P$1") (pintype "passive"))
    )
    (net (code "410") (name "unconnected-(U$547-P-PadP$1)") (class "Default")
      (node (ref "U$547") (pin "P$1") (pinfunction "P_P$1") (pintype "passive"))
    )
    (net (code "411") (name "unconnected-(U$548-P-PadP$1)") (class "Default")
      (node (ref "U$548") (pin "P$1") (pinfunction "P_P$1") (pintype "passive"))
    )
    (net (code "412") (name "unconnected-(U$549-P-PadP$1)") (class "Default")
      (node (ref "U$549") (pin "P$1") (pinfunction "P_P$1") (pintype "passive"))
    )
    (net (code "413") (name "unconnected-(U$573-P-PadP$1)") (class "Default")
      (node (ref "U$573") (pin "P$1") (pinfunction "P_P$1") (pintype "passive"))
    )
    (net (code "414") (name "unconnected-(U$574-P-PadP$1)") (class "Default")
      (node (ref "U$574") (pin "P$1") (pinfunction "P_P$1") (pintype "passive"))
    )
    (net (code "415") (name "unconnected-(U$575-P-PadP$1)") (class "Default")
      (node (ref "U$575") (pin "P$1") (pinfunction "P_P$1") (pintype "passive"))
    )
    (net (code "416") (name "unconnected-(U$576-P-PadP$1)") (class "Default")
      (node (ref "U$576") (pin "P$1") (pinfunction "P_P$1") (pintype "passive"))
    )
    (net (code "417") (name "unconnected-(U$577-P-PadP$1)") (class "Default")
      (node (ref "U$577") (pin "P$1") (pinfunction "P_P$1") (pintype "passive"))
    )
    (net (code "418") (name "unconnected-(U$578-P-PadP$1)") (class "Default")
      (node (ref "U$578") (pin "P$1") (pinfunction "P_P$1") (pintype "passive"))
    )
    (net (code "419") (name "unconnected-(U$579-P-PadP$1)") (class "Default")
      (node (ref "U$579") (pin "P$1") (pinfunction "P_P$1") (pintype "passive"))
    )
    (net (code "420") (name "unconnected-(U$580-P-PadP$1)") (class "Default")
      (node (ref "U$580") (pin "P$1") (pinfunction "P_P$1") (pintype "passive"))
    )
    (net (code "421") (name "unconnected-(U$581-P-PadP$1)") (class "Default")
      (node (ref "U$581") (pin "P$1") (pinfunction "P_P$1") (pintype "passive"))
    )
    (net (code "422") (name "unconnected-(U$582-P-PadP$1)") (class "Default")
      (node (ref "U$582") (pin "P$1") (pinfunction "P_P$1") (pintype "passive"))
    )
    (net (code "423") (name "unconnected-(U$583-P-PadP$1)") (class "Default")
      (node (ref "U$583") (pin "P$1") (pinfunction "P_P$1") (pintype "passive"))
    )
    (net (code "424") (name "unconnected-(U$584-P-PadP$1)") (class "Default")
      (node (ref "U$584") (pin "P$1") (pinfunction "P_P$1") (pintype "passive"))
    )
    (net (code "425") (name "unconnected-(U$585-P-PadP$1)") (class "Default")
      (node (ref "U$585") (pin "P$1") (pinfunction "P_P$1") (pintype "passive"))
    )
    (net (code "426") (name "unconnected-(U$586-P-PadP$1)") (class "Default")
      (node (ref "U$586") (pin "P$1") (pinfunction "P_P$1") (pintype "passive"))
    )
    (net (code "427") (name "unconnected-(U$587-P-PadP$1)") (class "Default")
      (node (ref "U$587") (pin "P$1") (pinfunction "P_P$1") (pintype "passive"))
    )
    (net (code "428") (name "unconnected-(U$588-P-PadP$1)") (class "Default")
      (node (ref "U$588") (pin "P$1") (pinfunction "P_P$1") (pintype "passive"))
    )
    (net (code "429") (name "unconnected-(U$589-P-PadP$1)") (class "Default")
      (node (ref "U$589") (pin "P$1") (pinfunction "P_P$1") (pintype "passive"))
    )
    (net (code "430") (name "unconnected-(U$590-P-PadP$1)") (class "Default")
      (node (ref "U$590") (pin "P$1") (pinfunction "P_P$1") (pintype "passive"))
    )
    (net (code "431") (name "unconnected-(U$591-P-PadP$1)") (class "Default")
      (node (ref "U$591") (pin "P$1") (pinfunction "P_P$1") (pintype "passive"))
    )
    (net (code "432") (name "unconnected-(U$592-P-PadP$1)") (class "Default")
      (node (ref "U$592") (pin "P$1") (pinfunction "P_P$1") (pintype "passive"))
    )
    (net (code "433") (name "unconnected-(U$593-P-PadP$1)") (class "Default")
      (node (ref "U$593") (pin "P$1") (pinfunction "P_P$1") (pintype "passive"))
    )
    (net (code "434") (name "unconnected-(U$594-P-PadP$1)") (class "Default")
      (node (ref "U$594") (pin "P$1") (pinfunction "P_P$1") (pintype "passive"))
    )
    (net (code "435") (name "unconnected-(U$595-P-PadP$1)") (class "Default")
      (node (ref "U$595") (pin "P$1") (pinfunction "P_P$1") (pintype "passive"))
    )
    (net (code "436") (name "unconnected-(U$596-P-PadP$1)") (class "Default")
      (node (ref "U$596") (pin "P$1") (pinfunction "P_P$1") (pintype "passive"))
    )
    (net (code "437") (name "unconnected-(U$597-P-PadP$1)") (class "Default")
      (node (ref "U$597") (pin "P$1") (pinfunction "P_P$1") (pintype "passive"))
    )
    (net (code "438") (name "unconnected-(U$598-P-PadP$1)") (class "Default")
      (node (ref "U$598") (pin "P$1") (pinfunction "P_P$1") (pintype "passive"))
    )
    (net (code "439") (name "unconnected-(U$599-P-PadP$1)") (class "Default")
      (node (ref "U$599") (pin "P$1") (pinfunction "P_P$1") (pintype "passive"))
    )
    (net (code "440") (name "unconnected-(U$600-P-PadP$1)") (class "Default")
      (node (ref "U$600") (pin "P$1") (pinfunction "P_P$1") (pintype "passive"))
    )
    (net (code "441") (name "unconnected-(U$601-P-PadP$1)") (class "Default")
      (node (ref "U$601") (pin "P$1") (pinfunction "P_P$1") (pintype "passive"))
    )
    (net (code "442") (name "unconnected-(U$602-P-PadP$1)") (class "Default")
      (node (ref "U$602") (pin "P$1") (pinfunction "P_P$1") (pintype "passive"))
    )
    (net (code "443") (name "unconnected-(U$603-P-PadP$1)") (class "Default")
      (node (ref "U$603") (pin "P$1") (pinfunction "P_P$1") (pintype "passive"))
    )
    (net (code "444") (name "unconnected-(U$604-P-PadP$1)") (class "Default")
      (node (ref "U$604") (pin "P$1") (pinfunction "P_P$1") (pintype "passive"))
    )
    (net (code "445") (name "unconnected-(U$605-P-PadP$1)") (class "Default")
      (node (ref "U$605") (pin "P$1") (pinfunction "P_P$1") (pintype "passive"))
    )
    (net (code "446") (name "unconnected-(U$606-P-PadP$1)") (class "Default")
      (node (ref "U$606") (pin "P$1") (pinfunction "P_P$1") (pintype "passive"))
    )
    (net (code "447") (name "unconnected-(U$607-P-PadP$1)") (class "Default")
      (node (ref "U$607") (pin "P$1") (pinfunction "P_P$1") (pintype "passive"))
    )
    (net (code "448") (name "unconnected-(U$608-P-PadP$1)") (class "Default")
      (node (ref "U$608") (pin "P$1") (pinfunction "P_P$1") (pintype "passive"))
    )
    (net (code "449") (name "unconnected-(U$609-P-PadP$1)") (class "Default")
      (node (ref "U$609") (pin "P$1") (pinfunction "P_P$1") (pintype "passive"))
    )
    (net (code "450") (name "unconnected-(U$610-P-PadP$1)") (class "Default")
      (node (ref "U$610") (pin "P$1") (pinfunction "P_P$1") (pintype "passive"))
    )
    (net (code "451") (name "unconnected-(U$611-P-PadP$1)") (class "Default")
      (node (ref "U$611") (pin "P$1") (pinfunction "P_P$1") (pintype "passive"))
    )
    (net (code "452") (name "unconnected-(U$612-P-PadP$1)") (class "Default")
      (node (ref "U$612") (pin "P$1") (pinfunction "P_P$1") (pintype "passive"))
    )
    (net (code "453") (name "unconnected-(U$613-P-PadP$1)") (class "Default")
      (node (ref "U$613") (pin "P$1") (pinfunction "P_P$1") (pintype "passive"))
    )
    (net (code "454") (name "unconnected-(U$614-P-PadP$1)") (class "Default")
      (node (ref "U$614") (pin "P$1") (pinfunction "P_P$1") (pintype "passive"))
    )
    (net (code "455") (name "unconnected-(U$615-P-PadP$1)") (class "Default")
      (node (ref "U$615") (pin "P$1") (pinfunction "P_P$1") (pintype "passive"))
    )
    (net (code "456") (name "unconnected-(U$616-P-PadP$1)") (class "Default")
      (node (ref "U$616") (pin "P$1") (pinfunction "P_P$1") (pintype "passive"))
    )
    (net (code "457") (name "unconnected-(U$617-P-PadP$1)") (class "Default")
      (node (ref "U$617") (pin "P$1") (pinfunction "P_P$1") (pintype "passive"))
    )
    (net (code "458") (name "unconnected-(U$618-P-PadP$1)") (class "Default")
      (node (ref "U$618") (pin "P$1") (pinfunction "P_P$1") (pintype "passive"))
    )
    (net (code "459") (name "unconnected-(U$619-P-PadP$1)") (class "Default")
      (node (ref "U$619") (pin "P$1") (pinfunction "P_P$1") (pintype "passive"))
    )
    (net (code "460") (name "unconnected-(U$620-P-PadP$1)") (class "Default")
      (node (ref "U$620") (pin "P$1") (pinfunction "P_P$1") (pintype "passive"))
    )
    (net (code "461") (name "unconnected-(U$621-P-PadP$1)") (class "Default")
      (node (ref "U$621") (pin "P$1") (pinfunction "P_P$1") (pintype "passive"))
    )
    (net (code "462") (name "unconnected-(U$622-P-PadP$1)") (class "Default")
      (node (ref "U$622") (pin "P$1") (pinfunction "P_P$1") (pintype "passive"))
    )
    (net (code "463") (name "unconnected-(U$623-P-PadP$1)") (class "Default")
      (node (ref "U$623") (pin "P$1") (pinfunction "P_P$1") (pintype "passive"))
    )
    (net (code "464") (name "unconnected-(U$624-P-PadP$1)") (class "Default")
      (node (ref "U$624") (pin "P$1") (pinfunction "P_P$1") (pintype "passive"))
    )
    (net (code "465") (name "unconnected-(U$625-P-PadP$1)") (class "Default")
      (node (ref "U$625") (pin "P$1") (pinfunction "P_P$1") (pintype "passive"))
    )
    (net (code "466") (name "unconnected-(U$626-P-PadP$1)") (class "Default")
      (node (ref "U$626") (pin "P$1") (pinfunction "P_P$1") (pintype "passive"))
    )
    (net (code "467") (name "unconnected-(U$627-P-PadP$1)") (class "Default")
      (node (ref "U$627") (pin "P$1") (pinfunction "P_P$1") (pintype "passive"))
    )
    (net (code "468") (name "unconnected-(U$628-P-PadP$1)") (class "Default")
      (node (ref "U$628") (pin "P$1") (pinfunction "P_P$1") (pintype "passive"))
    )
    (net (code "469") (name "unconnected-(U$629-P-PadP$1)") (class "Default")
      (node (ref "U$629") (pin "P$1") (pinfunction "P_P$1") (pintype "passive"))
    )
    (net (code "470") (name "unconnected-(U$630-P-PadP$1)") (class "Default")
      (node (ref "U$630") (pin "P$1") (pinfunction "P_P$1") (pintype "passive"))
    )
    (net (code "471") (name "unconnected-(U$631-P-PadP$1)") (class "Default")
      (node (ref "U$631") (pin "P$1") (pinfunction "P_P$1") (pintype "passive"))
    )
    (net (code "472") (name "unconnected-(U$632-P-PadP$1)") (class "Default")
      (node (ref "U$632") (pin "P$1") (pinfunction "P_P$1") (pintype "passive"))
    )
    (net (code "473") (name "unconnected-(U$633-P-PadP$1)") (class "Default")
      (node (ref "U$633") (pin "P$1") (pinfunction "P_P$1") (pintype "passive"))
    )
    (net (code "474") (name "unconnected-(U$634-P-PadP$1)") (class "Default")
      (node (ref "U$634") (pin "P$1") (pinfunction "P_P$1") (pintype "passive"))
    )
    (net (code "475") (name "unconnected-(U$635-P-PadP$1)") (class "Default")
      (node (ref "U$635") (pin "P$1") (pinfunction "P_P$1") (pintype "passive"))
    )
    (net (code "476") (name "unconnected-(U$636-P-PadP$1)") (class "Default")
      (node (ref "U$636") (pin "P$1") (pinfunction "P_P$1") (pintype "passive"))
    )
    (net (code "477") (name "unconnected-(U$637-P-PadP$1)") (class "Default")
      (node (ref "U$637") (pin "P$1") (pinfunction "P_P$1") (pintype "passive"))
    )
    (net (code "478") (name "unconnected-(U$638-P-PadP$1)") (class "Default")
      (node (ref "U$638") (pin "P$1") (pinfunction "P_P$1") (pintype "passive"))
    )
    (net (code "479") (name "unconnected-(U$639-P-PadP$1)") (class "Default")
      (node (ref "U$639") (pin "P$1") (pinfunction "P_P$1") (pintype "passive"))
    )
    (net (code "480") (name "unconnected-(U$640-P-PadP$1)") (class "Default")
      (node (ref "U$640") (pin "P$1") (pinfunction "P_P$1") (pintype "passive"))
    )
    (net (code "481") (name "unconnected-(U$641-P-PadP$1)") (class "Default")
      (node (ref "U$641") (pin "P$1") (pinfunction "P_P$1") (pintype "passive"))
    )
    (net (code "482") (name "unconnected-(U$642-P-PadP$1)") (class "Default")
      (node (ref "U$642") (pin "P$1") (pinfunction "P_P$1") (pintype "passive"))
    )
    (net (code "483") (name "unconnected-(U$665-P-PadP$1)") (class "Default")
      (node (ref "U$665") (pin "P$1") (pinfunction "P_P$1") (pintype "passive"))
    )
    (net (code "484") (name "unconnected-(U$666-P-PadP$1)") (class "Default")
      (node (ref "U$666") (pin "P$1") (pinfunction "P_P$1") (pintype "passive"))
    )
    (net (code "485") (name "unconnected-(U$667-P-PadP$1)") (class "Default")
      (node (ref "U$667") (pin "P$1") (pinfunction "P_P$1") (pintype "passive"))
    )
    (net (code "486") (name "unconnected-(U$668-P-PadP$1)") (class "Default")
      (node (ref "U$668") (pin "P$1") (pinfunction "P_P$1") (pintype "passive"))
    )
    (net (code "487") (name "unconnected-(U$669-P-PadP$1)") (class "Default")
      (node (ref "U$669") (pin "P$1") (pinfunction "P_P$1") (pintype "passive"))
    )
    (net (code "488") (name "unconnected-(U$670-P-PadP$1)") (class "Default")
      (node (ref "U$670") (pin "P$1") (pinfunction "P_P$1") (pintype "passive"))
    )
    (net (code "489") (name "unconnected-(U$671-P-PadP$1)") (class "Default")
      (node (ref "U$671") (pin "P$1") (pinfunction "P_P$1") (pintype "passive"))
    )
    (net (code "490") (name "unconnected-(U$672-P-PadP$1)") (class "Default")
      (node (ref "U$672") (pin "P$1") (pinfunction "P_P$1") (pintype "passive"))
    )
    (net (code "491") (name "unconnected-(U$673-P-PadP$1)") (class "Default")
      (node (ref "U$673") (pin "P$1") (pinfunction "P_P$1") (pintype "passive"))
    )
    (net (code "492") (name "unconnected-(U$674-P-PadP$1)") (class "Default")
      (node (ref "U$674") (pin "P$1") (pinfunction "P_P$1") (pintype "passive"))
    )
    (net (code "493") (name "unconnected-(U$675-P-PadP$1)") (class "Default")
      (node (ref "U$675") (pin "P$1") (pinfunction "P_P$1") (pintype "passive"))
    )
    (net (code "494") (name "unconnected-(U$676-P-PadP$1)") (class "Default")
      (node (ref "U$676") (pin "P$1") (pinfunction "P_P$1") (pintype "passive"))
    )
    (net (code "495") (name "unconnected-(U$677-P-PadP$1)") (class "Default")
      (node (ref "U$677") (pin "P$1") (pinfunction "P_P$1") (pintype "passive"))
    )
    (net (code "496") (name "unconnected-(U$678-P-PadP$1)") (class "Default")
      (node (ref "U$678") (pin "P$1") (pinfunction "P_P$1") (pintype "passive"))
    )
    (net (code "497") (name "unconnected-(U$679-P-PadP$1)") (class "Default")
      (node (ref "U$679") (pin "P$1") (pinfunction "P_P$1") (pintype "passive"))
    )
    (net (code "498") (name "unconnected-(U$680-P-PadP$1)") (class "Default")
      (node (ref "U$680") (pin "P$1") (pinfunction "P_P$1") (pintype "passive"))
    )
    (net (code "499") (name "unconnected-(U$681-P-PadP$1)") (class "Default")
      (node (ref "U$681") (pin "P$1") (pinfunction "P_P$1") (pintype "passive"))
    )
    (net (code "500") (name "unconnected-(U$682-P-PadP$1)") (class "Default")
      (node (ref "U$682") (pin "P$1") (pinfunction "P_P$1") (pintype "passive"))
    )
    (net (code "501") (name "unconnected-(U$683-P-PadP$1)") (class "Default")
      (node (ref "U$683") (pin "P$1") (pinfunction "P_P$1") (pintype "passive"))
    )
    (net (code "502") (name "unconnected-(U$684-P-PadP$1)") (class "Default")
      (node (ref "U$684") (pin "P$1") (pinfunction "P_P$1") (pintype "passive"))
    )
    (net (code "503") (name "unconnected-(U$685-P-PadP$1)") (class "Default")
      (node (ref "U$685") (pin "P$1") (pinfunction "P_P$1") (pintype "passive"))
    )
    (net (code "504") (name "unconnected-(U$686-P-PadP$1)") (class "Default")
      (node (ref "U$686") (pin "P$1") (pinfunction "P_P$1") (pintype "passive"))
    )
    (net (code "505") (name "unconnected-(U$687-P-PadP$1)") (class "Default")
      (node (ref "U$687") (pin "P$1") (pinfunction "P_P$1") (pintype "passive"))
    )
    (net (code "506") (name "unconnected-(U$688-P-PadP$1)") (class "Default")
      (node (ref "U$688") (pin "P$1") (pinfunction "P_P$1") (pintype "passive"))
    )
    (net (code "507") (name "unconnected-(U$689-P-PadP$1)") (class "Default")
      (node (ref "U$689") (pin "P$1") (pinfunction "P_P$1") (pintype "passive"))
    )
    (net (code "508") (name "unconnected-(U$690-P-PadP$1)") (class "Default")
      (node (ref "U$690") (pin "P$1") (pinfunction "P_P$1") (pintype "passive"))
    )
    (net (code "509") (name "unconnected-(U$691-P-PadP$1)") (class "Default")
      (node (ref "U$691") (pin "P$1") (pinfunction "P_P$1") (pintype "passive"))
    )
    (net (code "510") (name "unconnected-(U$692-P-PadP$1)") (class "Default")
      (node (ref "U$692") (pin "P$1") (pinfunction "P_P$1") (pintype "passive"))
    )
    (net (code "511") (name "unconnected-(U$716-P-PadP$1)") (class "Default")
      (node (ref "U$716") (pin "P$1") (pinfunction "P_P$1") (pintype "passive"))
    )
    (net (code "512") (name "unconnected-(U$717-P-PadP$1)") (class "Default")
      (node (ref "U$717") (pin "P$1") (pinfunction "P_P$1") (pintype "passive"))
    )
    (net (code "513") (name "unconnected-(U$718-P-PadP$1)") (class "Default")
      (node (ref "U$718") (pin "P$1") (pinfunction "P_P$1") (pintype "passive"))
    )
    (net (code "514") (name "unconnected-(U$719-P-PadP$1)") (class "Default")
      (node (ref "U$719") (pin "P$1") (pinfunction "P_P$1") (pintype "passive"))
    )
    (net (code "515") (name "unconnected-(U$720-P-PadP$1)") (class "Default")
      (node (ref "U$720") (pin "P$1") (pinfunction "P_P$1") (pintype "passive"))
    )
    (net (code "516") (name "unconnected-(U$721-P-PadP$1)") (class "Default")
      (node (ref "U$721") (pin "P$1") (pinfunction "P_P$1") (pintype "passive"))
    )
    (net (code "517") (name "unconnected-(U$722-P-PadP$1)") (class "Default")
      (node (ref "U$722") (pin "P$1") (pinfunction "P_P$1") (pintype "passive"))
    )
    (net (code "518") (name "unconnected-(U$723-P-PadP$1)") (class "Default")
      (node (ref "U$723") (pin "P$1") (pinfunction "P_P$1") (pintype "passive"))
    )
    (net (code "519") (name "unconnected-(U$724-P-PadP$1)") (class "Default")
      (node (ref "U$724") (pin "P$1") (pinfunction "P_P$1") (pintype "passive"))
    )
    (net (code "520") (name "unconnected-(U$725-P-PadP$1)") (class "Default")
      (node (ref "U$725") (pin "P$1") (pinfunction "P_P$1") (pintype "passive"))
    )
    (net (code "521") (name "unconnected-(U$726-P-PadP$1)") (class "Default")
      (node (ref "U$726") (pin "P$1") (pinfunction "P_P$1") (pintype "passive"))
    )
    (net (code "522") (name "unconnected-(U$727-P-PadP$1)") (class "Default")
      (node (ref "U$727") (pin "P$1") (pinfunction "P_P$1") (pintype "passive"))
    )
    (net (code "523") (name "unconnected-(U$728-P-PadP$1)") (class "Default")
      (node (ref "U$728") (pin "P$1") (pinfunction "P_P$1") (pintype "passive"))
    )
    (net (code "524") (name "unconnected-(U$729-P-PadP$1)") (class "Default")
      (node (ref "U$729") (pin "P$1") (pinfunction "P_P$1") (pintype "passive"))
    )
    (net (code "525") (name "unconnected-(U$730-P-PadP$1)") (class "Default")
      (node (ref "U$730") (pin "P$1") (pinfunction "P_P$1") (pintype "passive"))
    )
    (net (code "526") (name "unconnected-(U$731-P-PadP$1)") (class "Default")
      (node (ref "U$731") (pin "P$1") (pinfunction "P_P$1") (pintype "passive"))
    )
    (net (code "527") (name "unconnected-(U$732-P-PadP$1)") (class "Default")
      (node (ref "U$732") (pin "P$1") (pinfunction "P_P$1") (pintype "passive"))
    )
    (net (code "528") (name "unconnected-(U$733-P-PadP$1)") (class "Default")
      (node (ref "U$733") (pin "P$1") (pinfunction "P_P$1") (pintype "passive"))
    )
    (net (code "529") (name "unconnected-(U$734-P-PadP$1)") (class "Default")
      (node (ref "U$734") (pin "P$1") (pinfunction "P_P$1") (pintype "passive"))
    )
    (net (code "530") (name "unconnected-(U$735-P-PadP$1)") (class "Default")
      (node (ref "U$735") (pin "P$1") (pinfunction "P_P$1") (pintype "passive"))
    )
    (net (code "531") (name "unconnected-(U$736-P-PadP$1)") (class "Default")
      (node (ref "U$736") (pin "P$1") (pinfunction "P_P$1") (pintype "passive"))
    )
    (net (code "532") (name "unconnected-(U$737-P-PadP$1)") (class "Default")
      (node (ref "U$737") (pin "P$1") (pinfunction "P_P$1") (pintype "passive"))
    )
    (net (code "533") (name "unconnected-(U$738-P-PadP$1)") (class "Default")
      (node (ref "U$738") (pin "P$1") (pinfunction "P_P$1") (pintype "passive"))
    )
    (net (code "534") (name "unconnected-(U$739-P-PadP$1)") (class "Default")
      (node (ref "U$739") (pin "P$1") (pinfunction "P_P$1") (pintype "passive"))
    )
    (net (code "535") (name "unconnected-(U$740-P-PadP$1)") (class "Default")
      (node (ref "U$740") (pin "P$1") (pinfunction "P_P$1") (pintype "passive"))
    )
    (net (code "536") (name "unconnected-(U$741-P-PadP$1)") (class "Default")
      (node (ref "U$741") (pin "P$1") (pinfunction "P_P$1") (pintype "passive"))
    )
    (net (code "537") (name "unconnected-(U$742-P-PadP$1)") (class "Default")
      (node (ref "U$742") (pin "P$1") (pinfunction "P_P$1") (pintype "passive"))
    )
    (net (code "538") (name "unconnected-(U$743-P-PadP$1)") (class "Default")
      (node (ref "U$743") (pin "P$1") (pinfunction "P_P$1") (pintype "passive"))
    )
    (net (code "539") (name "unconnected-(U$744-P-PadP$1)") (class "Default")
      (node (ref "U$744") (pin "P$1") (pinfunction "P_P$1") (pintype "passive"))
    )
    (net (code "540") (name "unconnected-(U$745-P-PadP$1)") (class "Default")
      (node (ref "U$745") (pin "P$1") (pinfunction "P_P$1") (pintype "passive"))
    )
    (net (code "541") (name "unconnected-(U$746-P-PadP$1)") (class "Default")
      (node (ref "U$746") (pin "P$1") (pinfunction "P_P$1") (pintype "passive"))
    )
    (net (code "542") (name "unconnected-(U$747-P-PadP$1)") (class "Default")
      (node (ref "U$747") (pin "P$1") (pinfunction "P_P$1") (pintype "passive"))
    )
    (net (code "543") (name "unconnected-(U$748-P-PadP$1)") (class "Default")
      (node (ref "U$748") (pin "P$1") (pinfunction "P_P$1") (pintype "passive"))
    )
    (net (code "544") (name "unconnected-(U$749-P-PadP$1)") (class "Default")
      (node (ref "U$749") (pin "P$1") (pinfunction "P_P$1") (pintype "passive"))
    )
    (net (code "545") (name "unconnected-(U$750-P-PadP$1)") (class "Default")
      (node (ref "U$750") (pin "P$1") (pinfunction "P_P$1") (pintype "passive"))
    )
    (net (code "546") (name "unconnected-(U$751-P-PadP$1)") (class "Default")
      (node (ref "U$751") (pin "P$1") (pinfunction "P_P$1") (pintype "passive"))
    )
    (net (code "547") (name "unconnected-(U$752-P-PadP$1)") (class "Default")
      (node (ref "U$752") (pin "P$1") (pinfunction "P_P$1") (pintype "passive"))
    )
    (net (code "548") (name "unconnected-(U$753-P-PadP$1)") (class "Default")
      (node (ref "U$753") (pin "P$1") (pinfunction "P_P$1") (pintype "passive"))
    )
    (net (code "549") (name "unconnected-(U$754-P-PadP$1)") (class "Default")
      (node (ref "U$754") (pin "P$1") (pinfunction "P_P$1") (pintype "passive"))
    )
    (net (code "550") (name "unconnected-(U$755-P-PadP$1)") (class "Default")
      (node (ref "U$755") (pin "P$1") (pinfunction "P_P$1") (pintype "passive"))
    )
    (net (code "551") (name "unconnected-(U$756-P-PadP$1)") (class "Default")
      (node (ref "U$756") (pin "P$1") (pinfunction "P_P$1") (pintype "passive"))
    )
    (net (code "552") (name "unconnected-(U$757-P-PadP$1)") (class "Default")
      (node (ref "U$757") (pin "P$1") (pinfunction "P_P$1") (pintype "passive"))
    )
    (net (code "553") (name "unconnected-(U$758-P-PadP$1)") (class "Default")
      (node (ref "U$758") (pin "P$1") (pinfunction "P_P$1") (pintype "passive"))
    )
    (net (code "554") (name "unconnected-(U$759-P-PadP$1)") (class "Default")
      (node (ref "U$759") (pin "P$1") (pinfunction "P_P$1") (pintype "passive"))
    )
    (net (code "555") (name "unconnected-(U$760-P-PadP$1)") (class "Default")
      (node (ref "U$760") (pin "P$1") (pinfunction "P_P$1") (pintype "passive"))
    )
    (net (code "556") (name "unconnected-(U$761-P-PadP$1)") (class "Default")
      (node (ref "U$761") (pin "P$1") (pinfunction "P_P$1") (pintype "passive"))
    )
    (net (code "557") (name "unconnected-(U$762-P-PadP$1)") (class "Default")
      (node (ref "U$762") (pin "P$1") (pinfunction "P_P$1") (pintype "passive"))
    )
    (net (code "558") (name "unconnected-(U$763-P-PadP$1)") (class "Default")
      (node (ref "U$763") (pin "P$1") (pinfunction "P_P$1") (pintype "passive"))
    )
    (net (code "559") (name "unconnected-(U$764-P-PadP$1)") (class "Default")
      (node (ref "U$764") (pin "P$1") (pinfunction "P_P$1") (pintype "passive"))
    )
    (net (code "560") (name "unconnected-(U$765-P-PadP$1)") (class "Default")
      (node (ref "U$765") (pin "P$1") (pinfunction "P_P$1") (pintype "passive"))
    )
    (net (code "561") (name "unconnected-(U$766-P-PadP$1)") (class "Default")
      (node (ref "U$766") (pin "P$1") (pinfunction "P_P$1") (pintype "passive"))
    )
    (net (code "562") (name "unconnected-(U$767-P-PadP$1)") (class "Default")
      (node (ref "U$767") (pin "P$1") (pinfunction "P_P$1") (pintype "passive"))
    )
    (net (code "563") (name "unconnected-(U$768-P-PadP$1)") (class "Default")
      (node (ref "U$768") (pin "P$1") (pinfunction "P_P$1") (pintype "passive"))
    )
    (net (code "564") (name "unconnected-(U$769-P-PadP$1)") (class "Default")
      (node (ref "U$769") (pin "P$1") (pinfunction "P_P$1") (pintype "passive"))
    )
    (net (code "565") (name "unconnected-(U$770-P-PadP$1)") (class "Default")
      (node (ref "U$770") (pin "P$1") (pinfunction "P_P$1") (pintype "passive"))
    )
    (net (code "566") (name "unconnected-(U$771-P-PadP$1)") (class "Default")
      (node (ref "U$771") (pin "P$1") (pinfunction "P_P$1") (pintype "passive"))
    )
    (net (code "567") (name "unconnected-(U$772-P-PadP$1)") (class "Default")
      (node (ref "U$772") (pin "P$1") (pinfunction "P_P$1") (pintype "passive"))
    )
    (net (code "568") (name "unconnected-(U$773-P-PadP$1)") (class "Default")
      (node (ref "U$773") (pin "P$1") (pinfunction "P_P$1") (pintype "passive"))
    )
    (net (code "569") (name "unconnected-(U$774-P-PadP$1)") (class "Default")
      (node (ref "U$774") (pin "P$1") (pinfunction "P_P$1") (pintype "passive"))
    )
    (net (code "570") (name "unconnected-(U$775-P-PadP$1)") (class "Default")
      (node (ref "U$775") (pin "P$1") (pinfunction "P_P$1") (pintype "passive"))
    )
    (net (code "571") (name "unconnected-(U$776-P-PadP$1)") (class "Default")
      (node (ref "U$776") (pin "P$1") (pinfunction "P_P$1") (pintype "passive"))
    )
    (net (code "572") (name "unconnected-(U$777-P-PadP$1)") (class "Default")
      (node (ref "U$777") (pin "P$1") (pinfunction "P_P$1") (pintype "passive"))
    )
    (net (code "573") (name "unconnected-(U$778-P-PadP$1)") (class "Default")
      (node (ref "U$778") (pin "P$1") (pinfunction "P_P$1") (pintype "passive"))
    )
    (net (code "574") (name "unconnected-(U$779-P-PadP$1)") (class "Default")
      (node (ref "U$779") (pin "P$1") (pinfunction "P_P$1") (pintype "passive"))
    )
    (net (code "575") (name "unconnected-(U$780-P-PadP$1)") (class "Default")
      (node (ref "U$780") (pin "P$1") (pinfunction "P_P$1") (pintype "passive"))
    )
    (net (code "576") (name "unconnected-(U$781-P-PadP$1)") (class "Default")
      (node (ref "U$781") (pin "P$1") (pinfunction "P_P$1") (pintype "passive"))
    )
    (net (code "577") (name "unconnected-(U$782-P-PadP$1)") (class "Default")
      (node (ref "U$782") (pin "P$1") (pinfunction "P_P$1") (pintype "passive"))
    )
    (net (code "578") (name "unconnected-(U$783-P-PadP$1)") (class "Default")
      (node (ref "U$783") (pin "P$1") (pinfunction "P_P$1") (pintype "passive"))
    )
    (net (code "579") (name "unconnected-(U$784-P-PadP$1)") (class "Default")
      (node (ref "U$784") (pin "P$1") (pinfunction "P_P$1") (pintype "passive"))
    )
    (net (code "580") (name "unconnected-(U$785-P-PadP$1)") (class "Default")
      (node (ref "U$785") (pin "P$1") (pinfunction "P_P$1") (pintype "passive"))
    )
    (net (code "581") (name "unconnected-(U$808-P-PadP$1)") (class "Default")
      (node (ref "U$808") (pin "P$1") (pinfunction "P_P$1") (pintype "passive"))
    )
    (net (code "582") (name "unconnected-(U$809-P-PadP$1)") (class "Default")
      (node (ref "U$809") (pin "P$1") (pinfunction "P_P$1") (pintype "passive"))
    )
    (net (code "583") (name "unconnected-(U$810-P-PadP$1)") (class "Default")
      (node (ref "U$810") (pin "P$1") (pinfunction "P_P$1") (pintype "passive"))
    )
    (net (code "584") (name "unconnected-(U$811-P-PadP$1)") (class "Default")
      (node (ref "U$811") (pin "P$1") (pinfunction "P_P$1") (pintype "passive"))
    )
    (net (code "585") (name "unconnected-(U$812-P-PadP$1)") (class "Default")
      (node (ref "U$812") (pin "P$1") (pinfunction "P_P$1") (pintype "passive"))
    )
    (net (code "586") (name "unconnected-(U$813-P-PadP$1)") (class "Default")
      (node (ref "U$813") (pin "P$1") (pinfunction "P_P$1") (pintype "passive"))
    )
    (net (code "587") (name "unconnected-(U$814-P-PadP$1)") (class "Default")
      (node (ref "U$814") (pin "P$1") (pinfunction "P_P$1") (pintype "passive"))
    )
    (net (code "588") (name "unconnected-(U$815-P-PadP$1)") (class "Default")
      (node (ref "U$815") (pin "P$1") (pinfunction "P_P$1") (pintype "passive"))
    )
    (net (code "589") (name "unconnected-(U$816-P-PadP$1)") (class "Default")
      (node (ref "U$816") (pin "P$1") (pinfunction "P_P$1") (pintype "passive"))
    )
    (net (code "590") (name "unconnected-(U$817-P-PadP$1)") (class "Default")
      (node (ref "U$817") (pin "P$1") (pinfunction "P_P$1") (pintype "passive"))
    )
    (net (code "591") (name "unconnected-(U$818-P-PadP$1)") (class "Default")
      (node (ref "U$818") (pin "P$1") (pinfunction "P_P$1") (pintype "passive"))
    )
    (net (code "592") (name "unconnected-(U$819-P-PadP$1)") (class "Default")
      (node (ref "U$819") (pin "P$1") (pinfunction "P_P$1") (pintype "passive"))
    )
    (net (code "593") (name "unconnected-(U$820-P-PadP$1)") (class "Default")
      (node (ref "U$820") (pin "P$1") (pinfunction "P_P$1") (pintype "passive"))
    )
    (net (code "594") (name "unconnected-(U$821-P-PadP$1)") (class "Default")
      (node (ref "U$821") (pin "P$1") (pinfunction "P_P$1") (pintype "passive"))
    )
    (net (code "595") (name "unconnected-(U$822-P-PadP$1)") (class "Default")
      (node (ref "U$822") (pin "P$1") (pinfunction "P_P$1") (pintype "passive"))
    )
    (net (code "596") (name "unconnected-(U$823-P-PadP$1)") (class "Default")
      (node (ref "U$823") (pin "P$1") (pinfunction "P_P$1") (pintype "passive"))
    )
    (net (code "597") (name "unconnected-(U$824-P-PadP$1)") (class "Default")
      (node (ref "U$824") (pin "P$1") (pinfunction "P_P$1") (pintype "passive"))
    )
    (net (code "598") (name "unconnected-(U$825-P-PadP$1)") (class "Default")
      (node (ref "U$825") (pin "P$1") (pinfunction "P_P$1") (pintype "passive"))
    )
    (net (code "599") (name "unconnected-(U$826-P-PadP$1)") (class "Default")
      (node (ref "U$826") (pin "P$1") (pinfunction "P_P$1") (pintype "passive"))
    )
    (net (code "600") (name "unconnected-(U$827-P-PadP$1)") (class "Default")
      (node (ref "U$827") (pin "P$1") (pinfunction "P_P$1") (pintype "passive"))
    )
    (net (code "601") (name "unconnected-(U$828-P-PadP$1)") (class "Default")
      (node (ref "U$828") (pin "P$1") (pinfunction "P_P$1") (pintype "passive"))
    )
    (net (code "602") (name "unconnected-(U$829-P-PadP$1)") (class "Default")
      (node (ref "U$829") (pin "P$1") (pinfunction "P_P$1") (pintype "passive"))
    )
    (net (code "603") (name "unconnected-(U$830-P-PadP$1)") (class "Default")
      (node (ref "U$830") (pin "P$1") (pinfunction "P_P$1") (pintype "passive"))
    )
    (net (code "604") (name "unconnected-(U$831-P-PadP$1)") (class "Default")
      (node (ref "U$831") (pin "P$1") (pinfunction "P_P$1") (pintype "passive"))
    )
    (net (code "605") (name "unconnected-(U$832-P-PadP$1)") (class "Default")
      (node (ref "U$832") (pin "P$1") (pinfunction "P_P$1") (pintype "passive"))
    )
    (net (code "606") (name "unconnected-(U$833-P-PadP$1)") (class "Default")
      (node (ref "U$833") (pin "P$1") (pinfunction "P_P$1") (pintype "passive"))
    )
    (net (code "607") (name "unconnected-(U$834-P-PadP$1)") (class "Default")
      (node (ref "U$834") (pin "P$1") (pinfunction "P_P$1") (pintype "passive"))
    )
    (net (code "608") (name "unconnected-(U$835-P-PadP$1)") (class "Default")
      (node (ref "U$835") (pin "P$1") (pinfunction "P_P$1") (pintype "passive"))
    )
  )
)
